# BMS.net
KiCad netlist of a schematic drawn in EAGLE
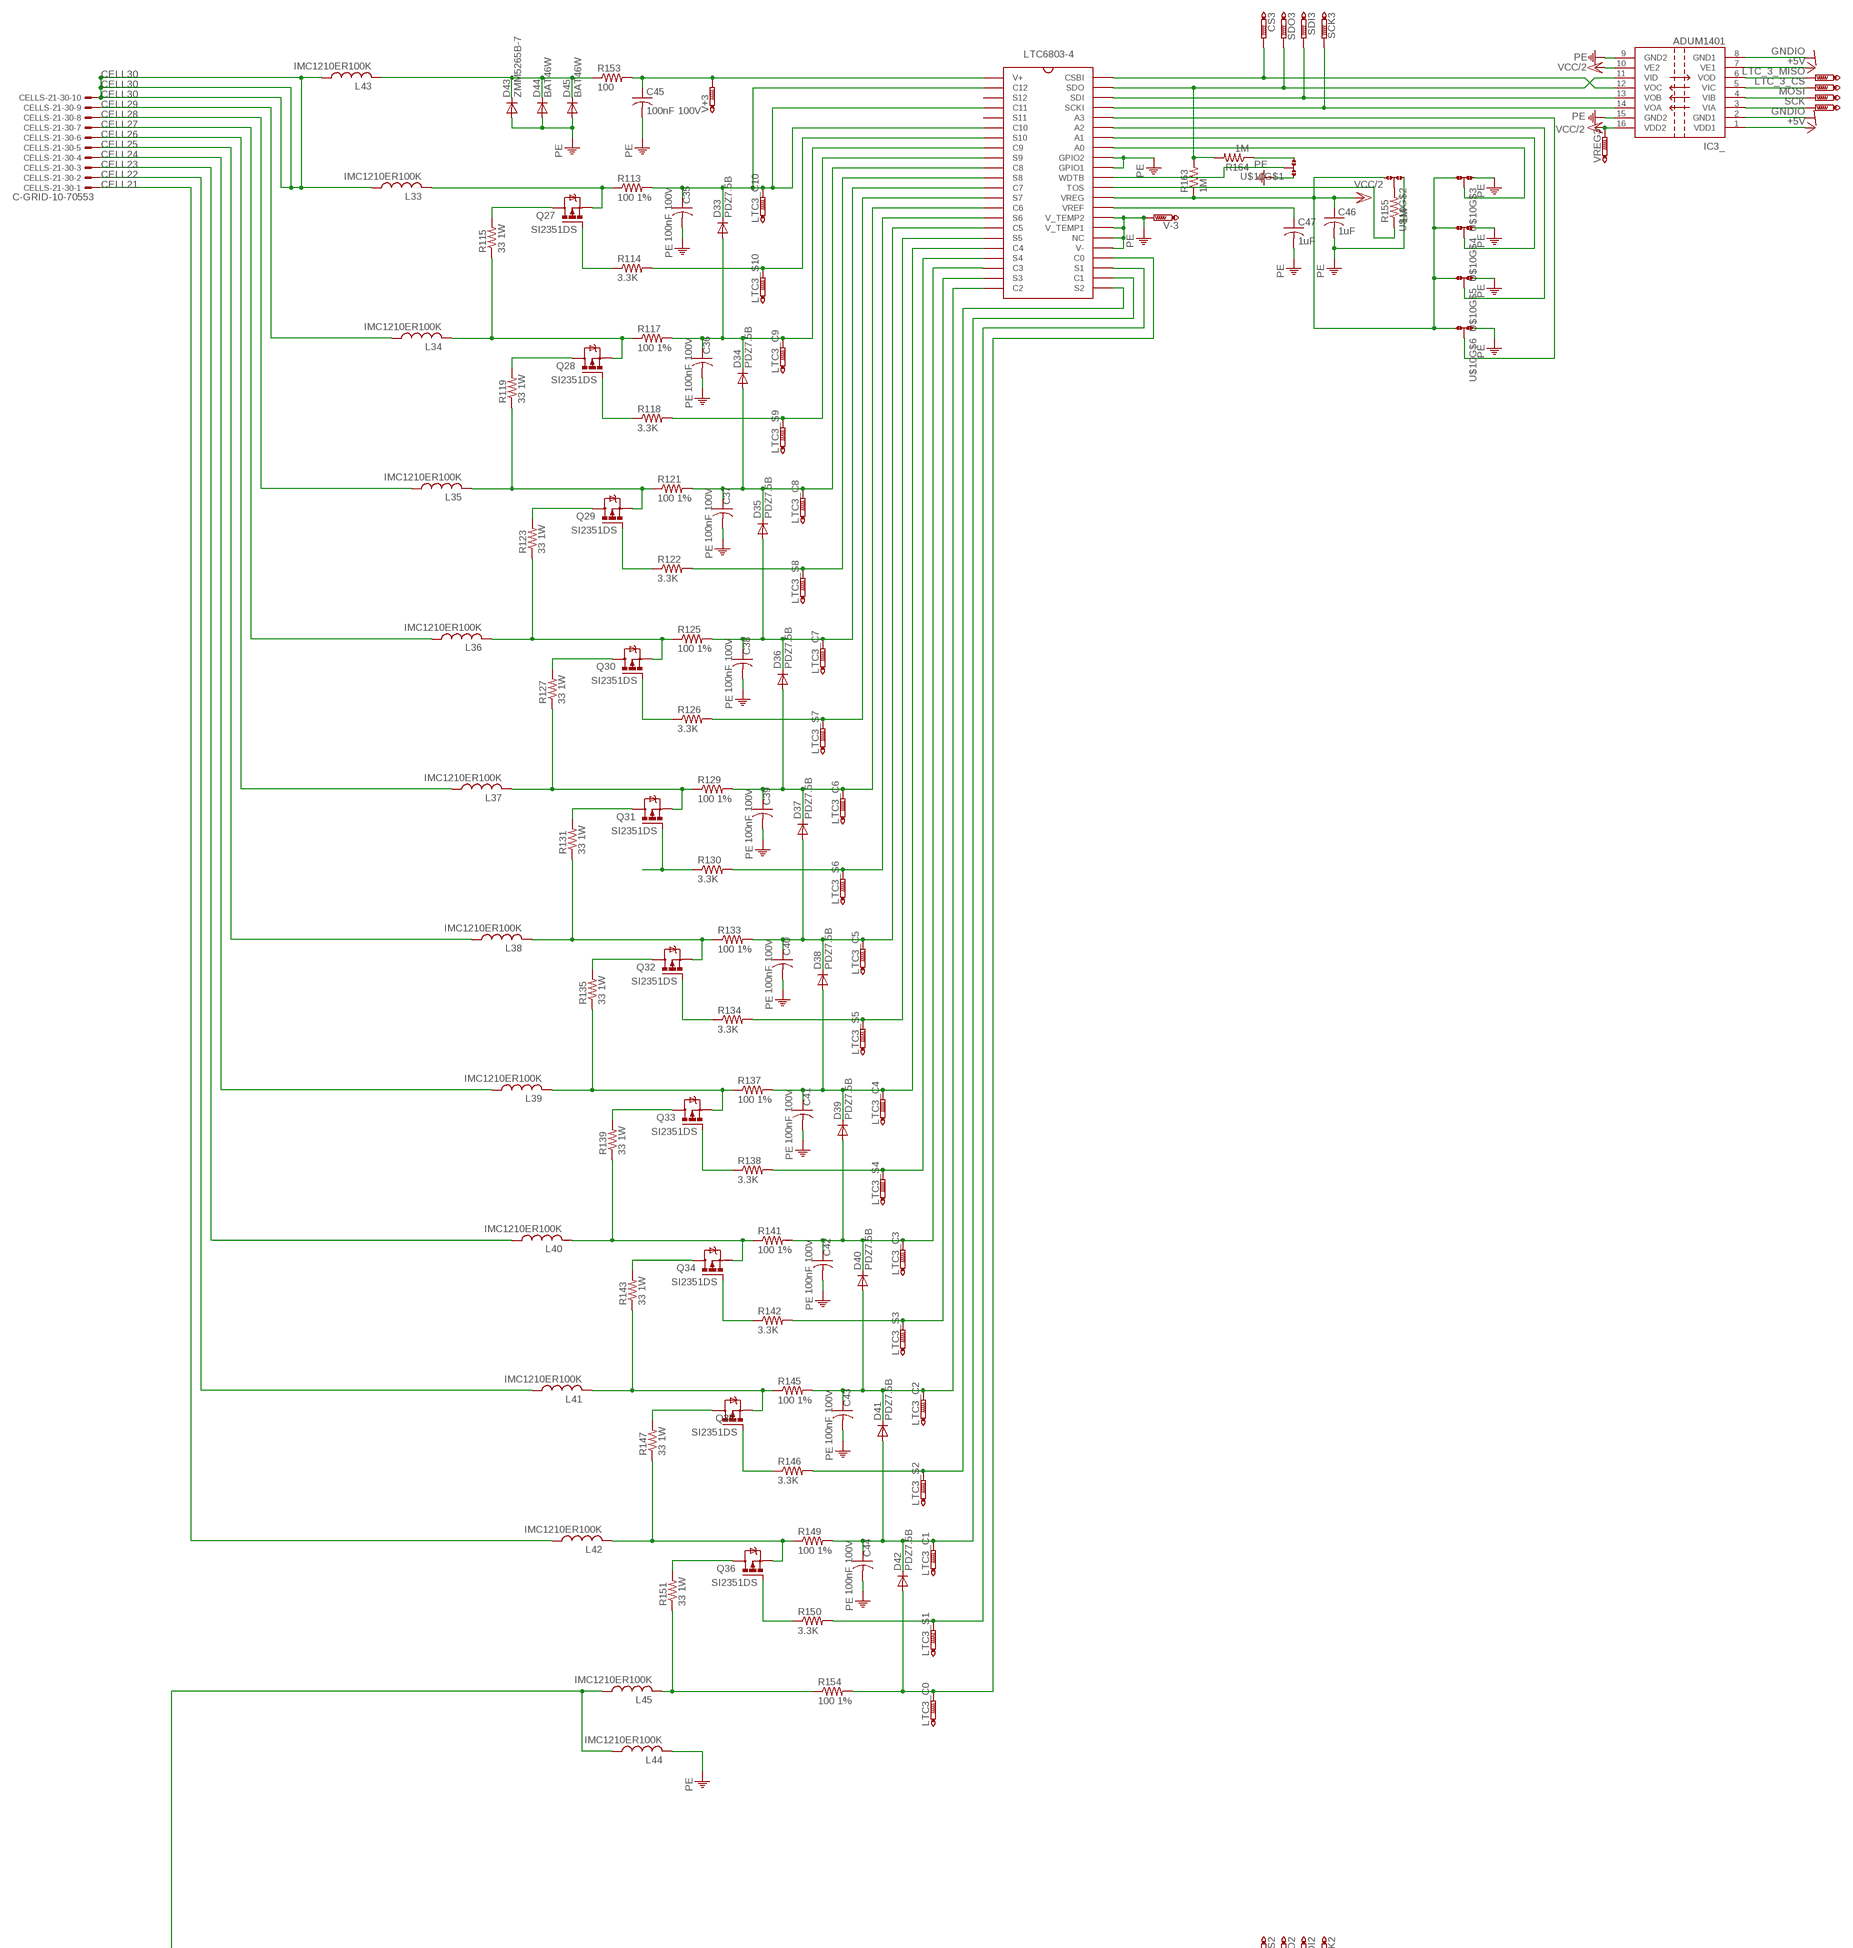
[diagram p0: schematic, sheet 1, part 1 of 3]
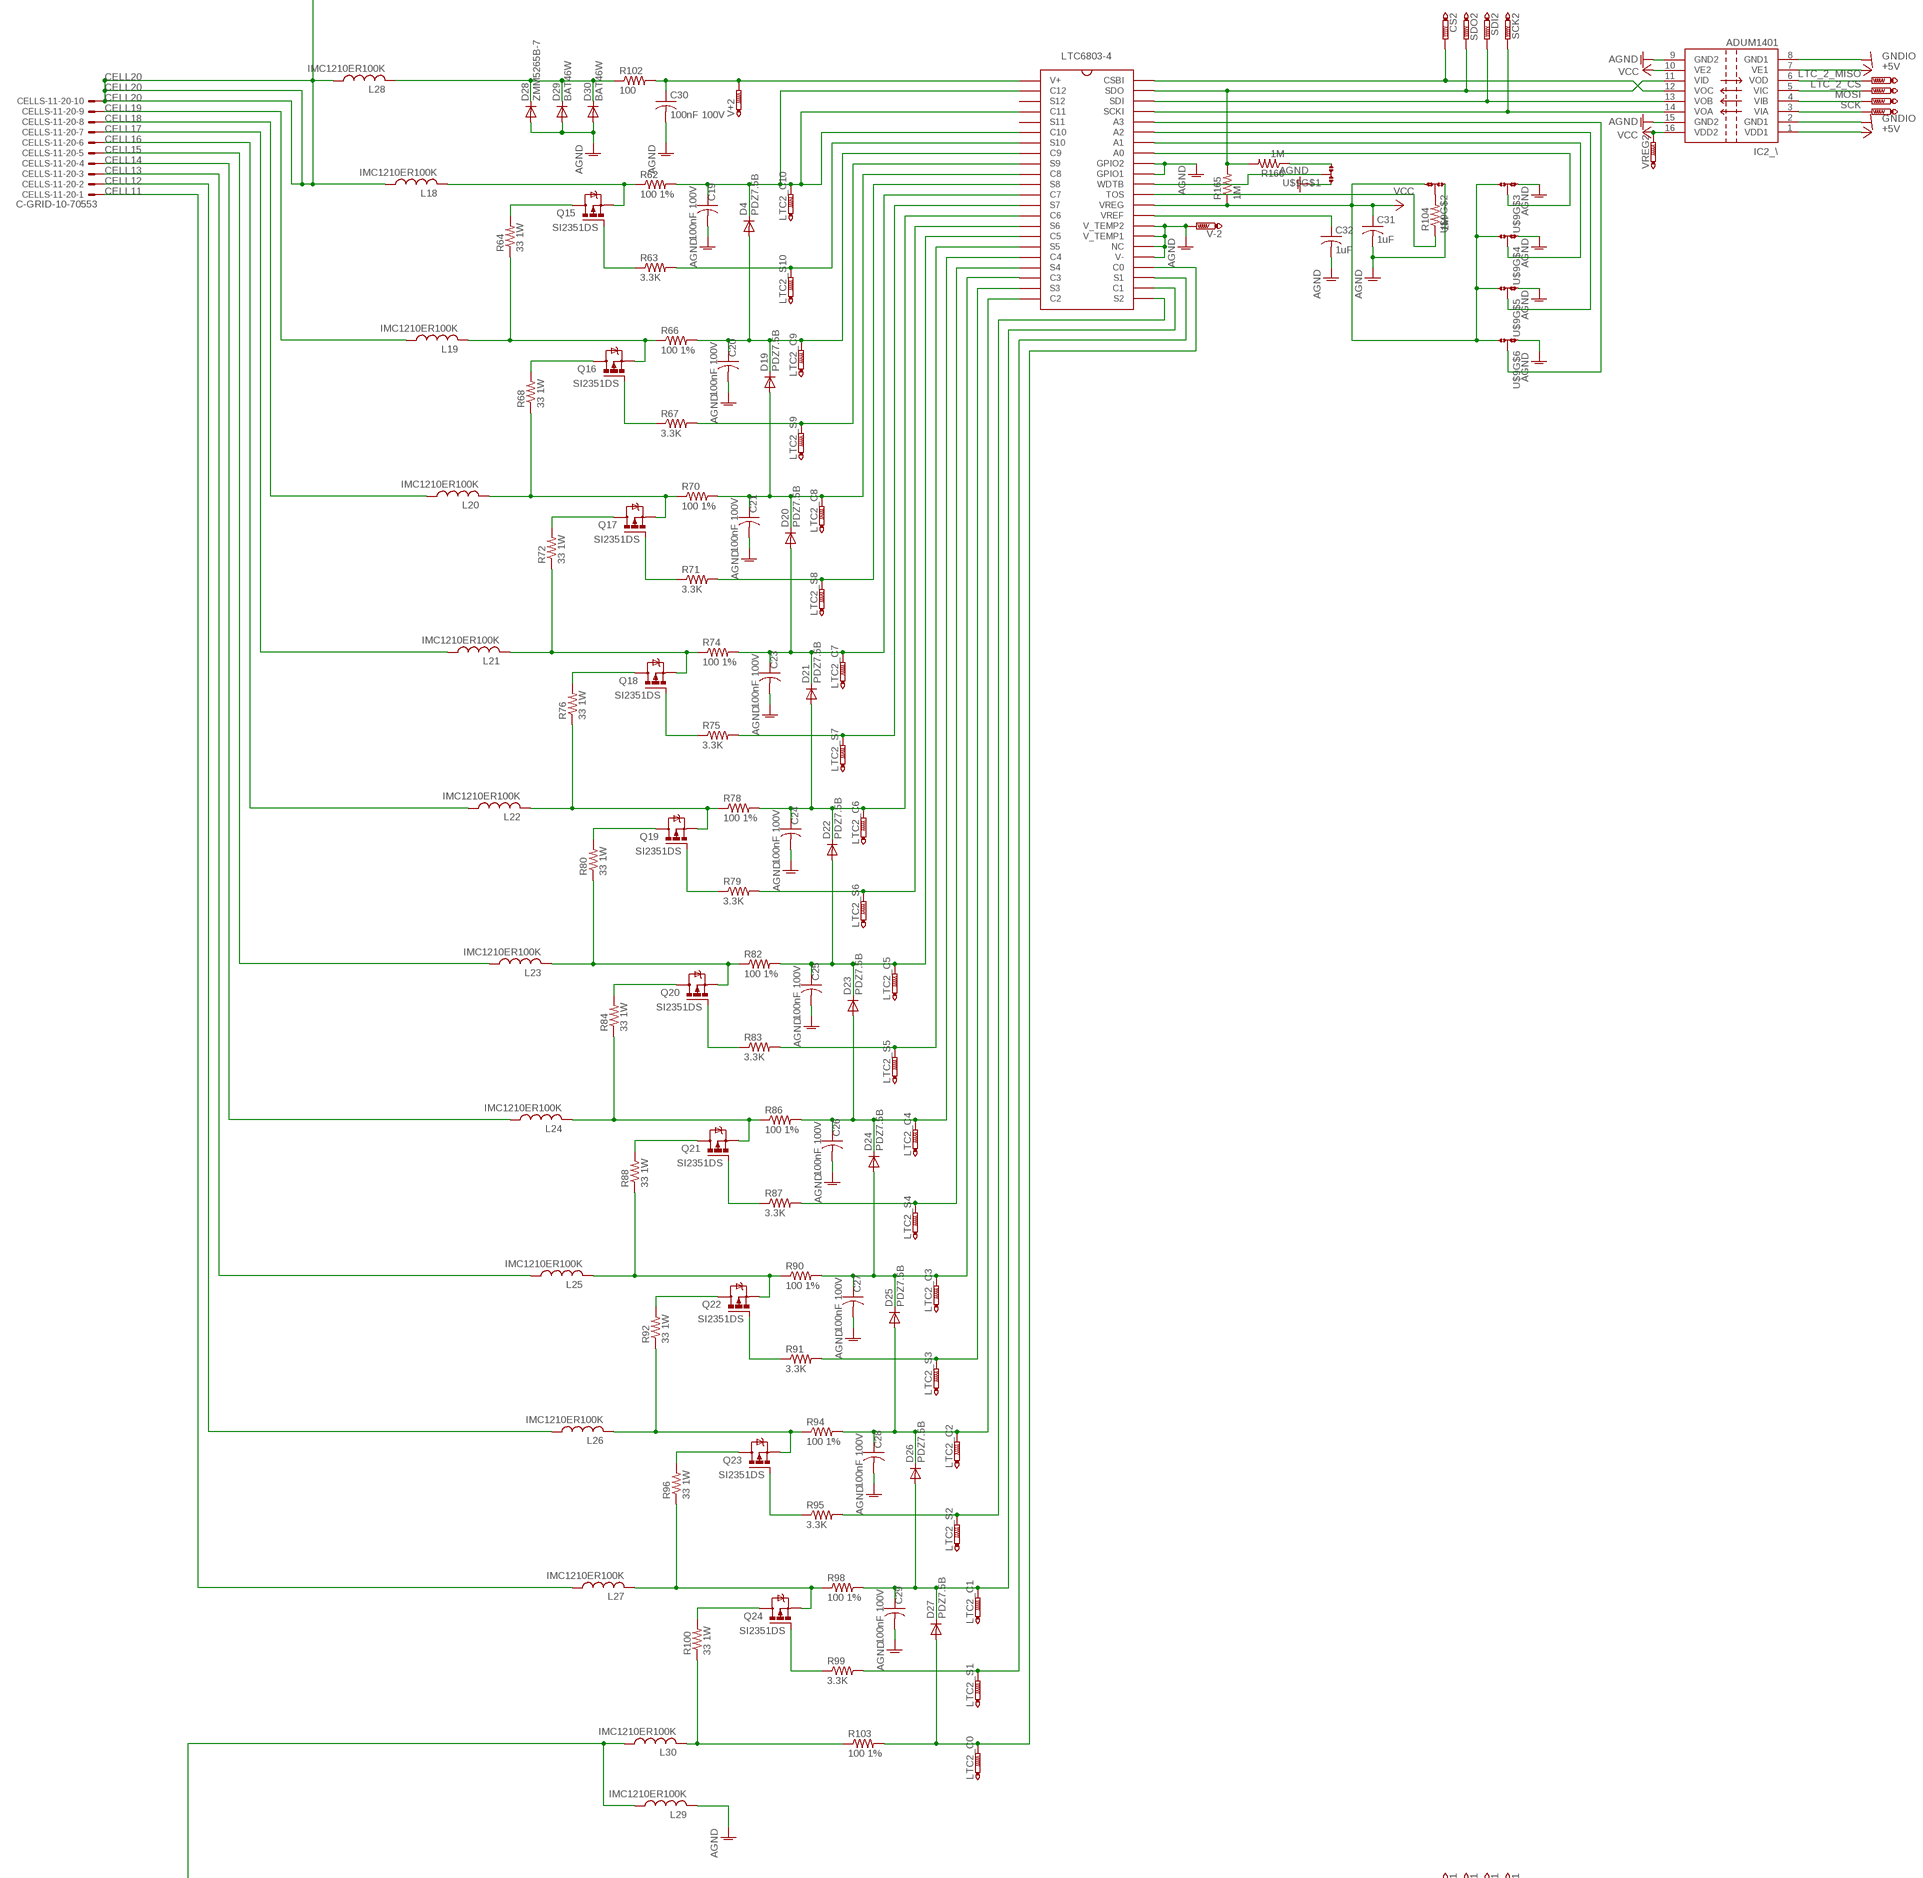
[diagram p1: schematic, sheet 1, part 2 of 3]
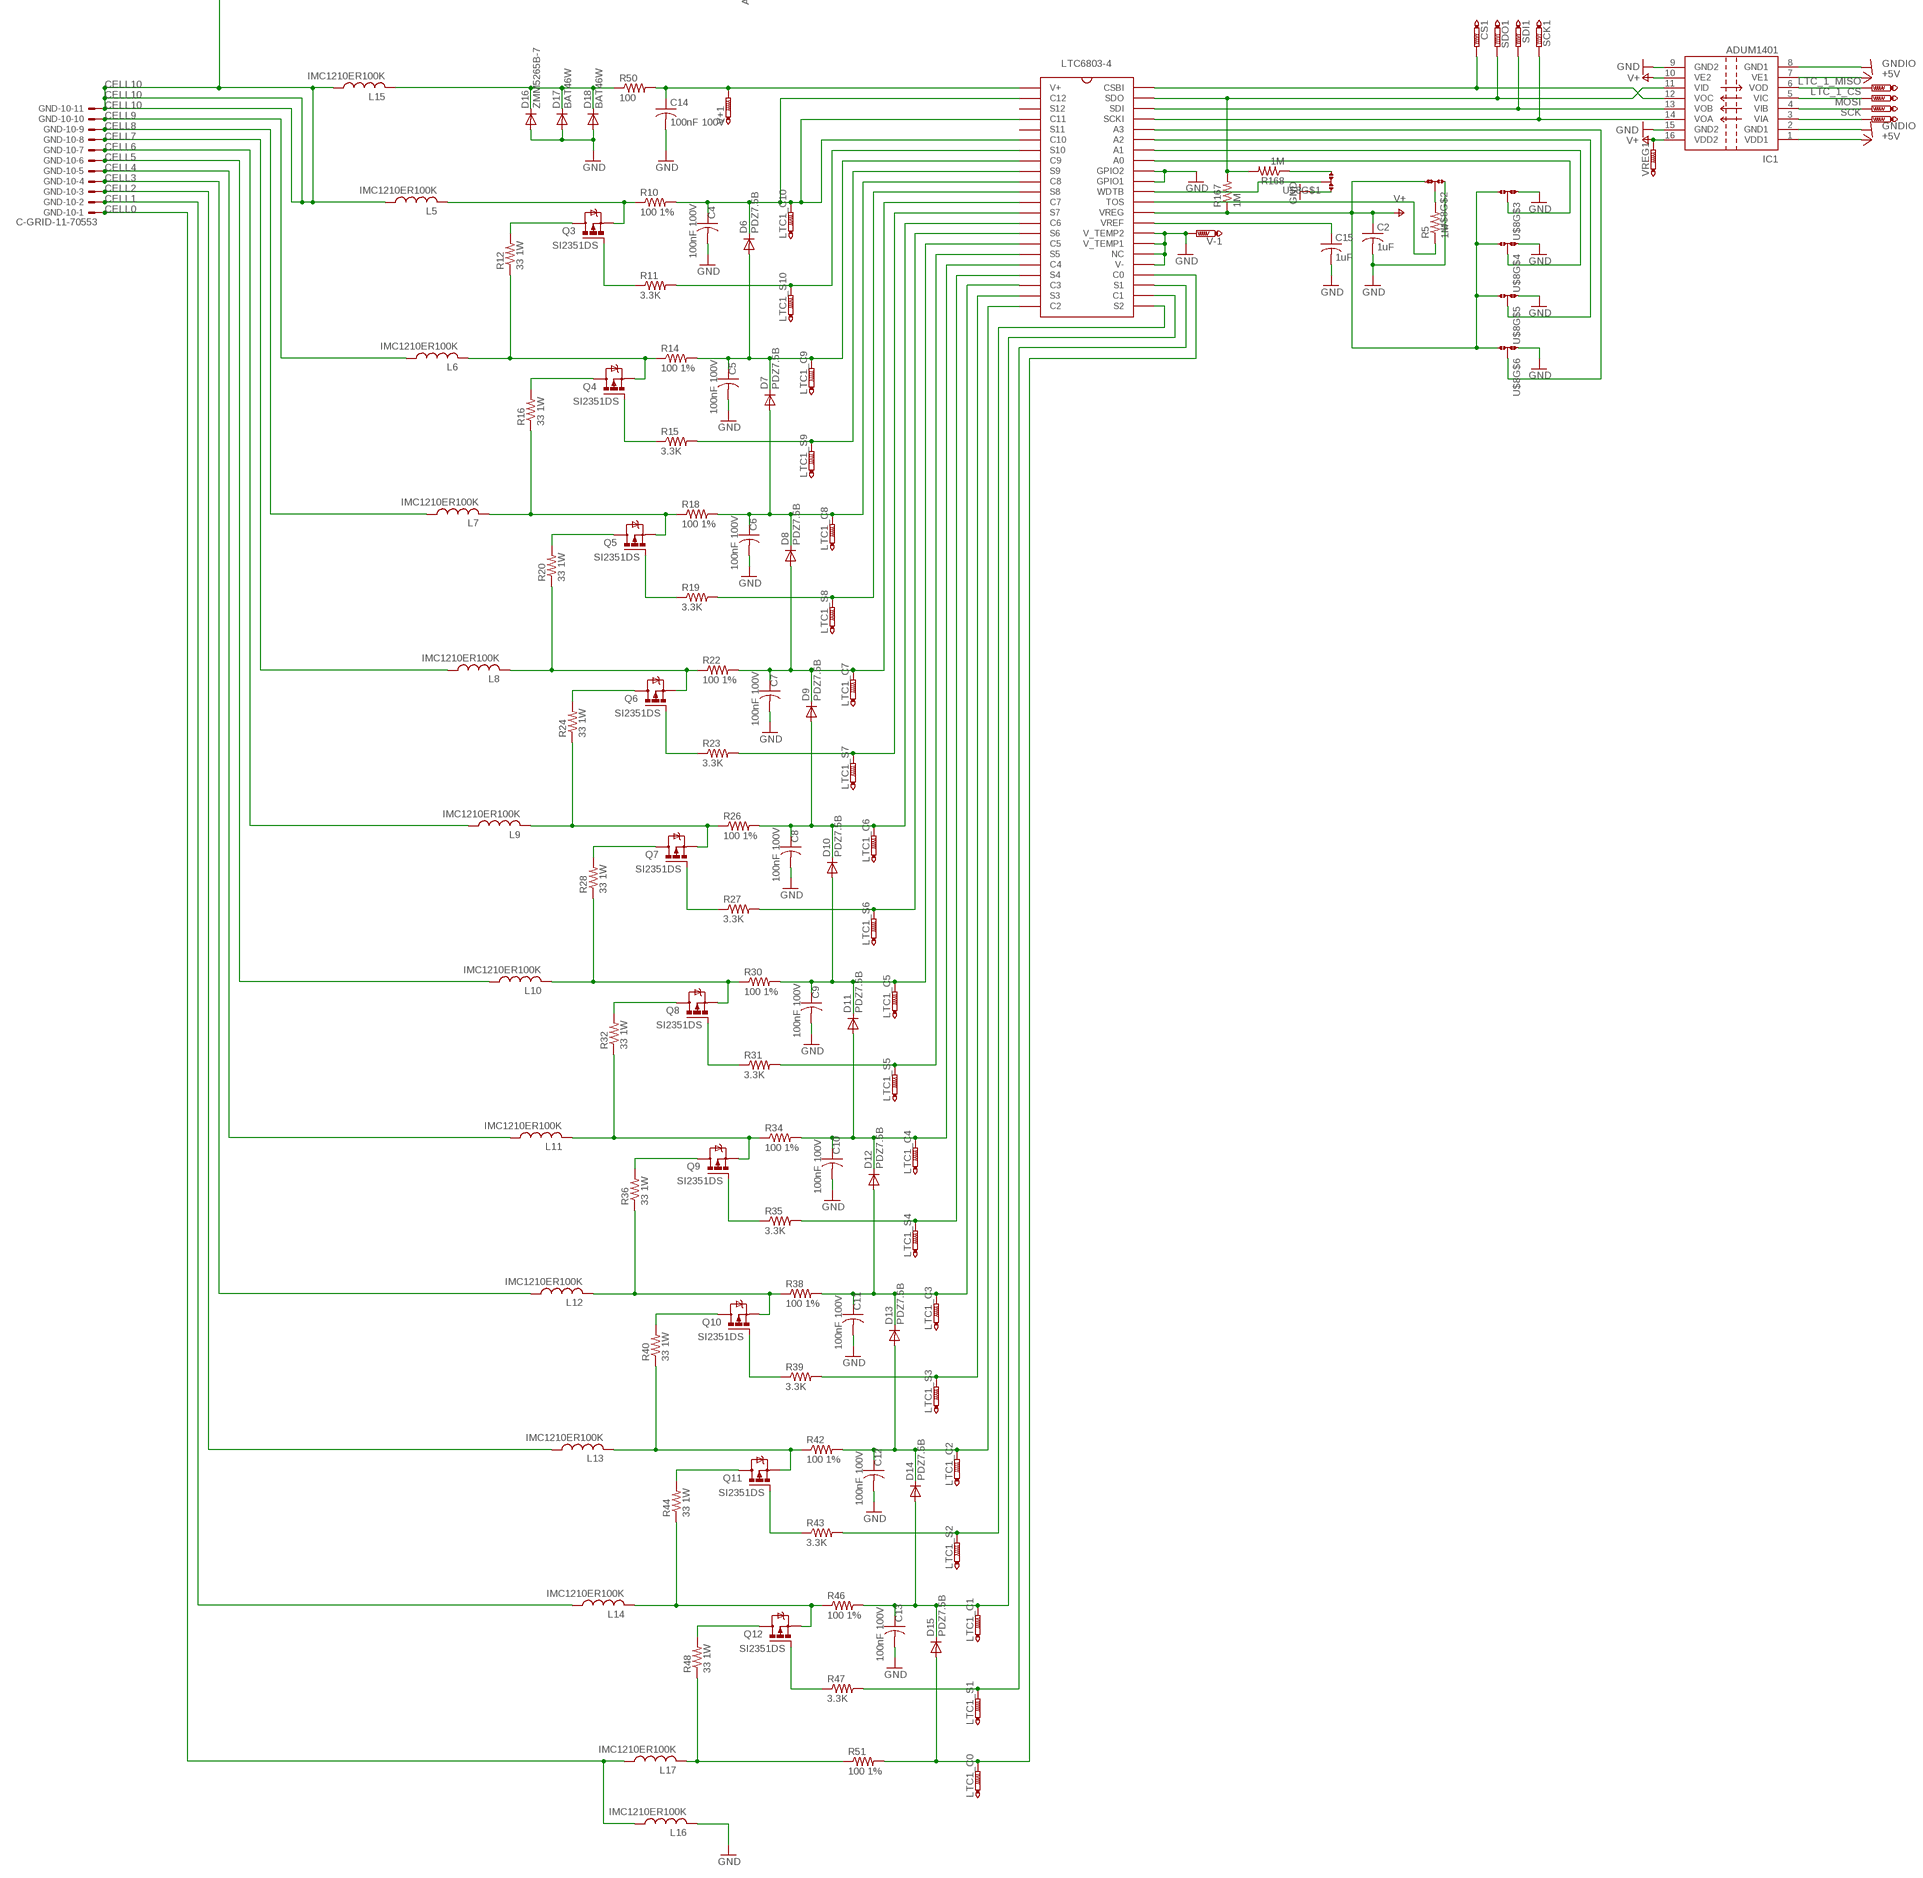
[diagram p2: schematic, sheet 1, part 3 of 3]
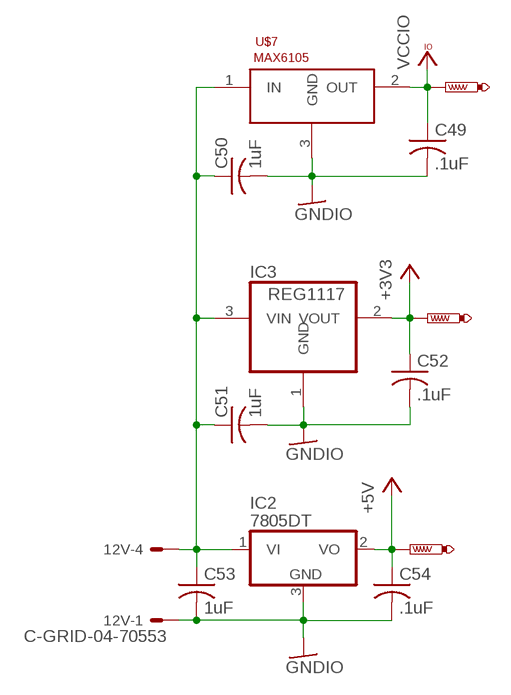
[diagram p3: schematic, sheet 2]
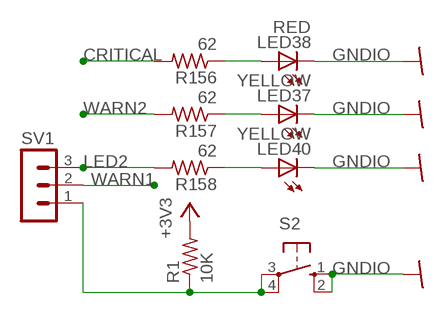
[diagram p4: schematic, sheet 3]
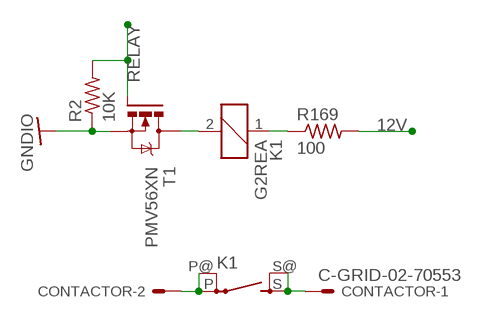
[diagram p5: schematic, sheet 4]
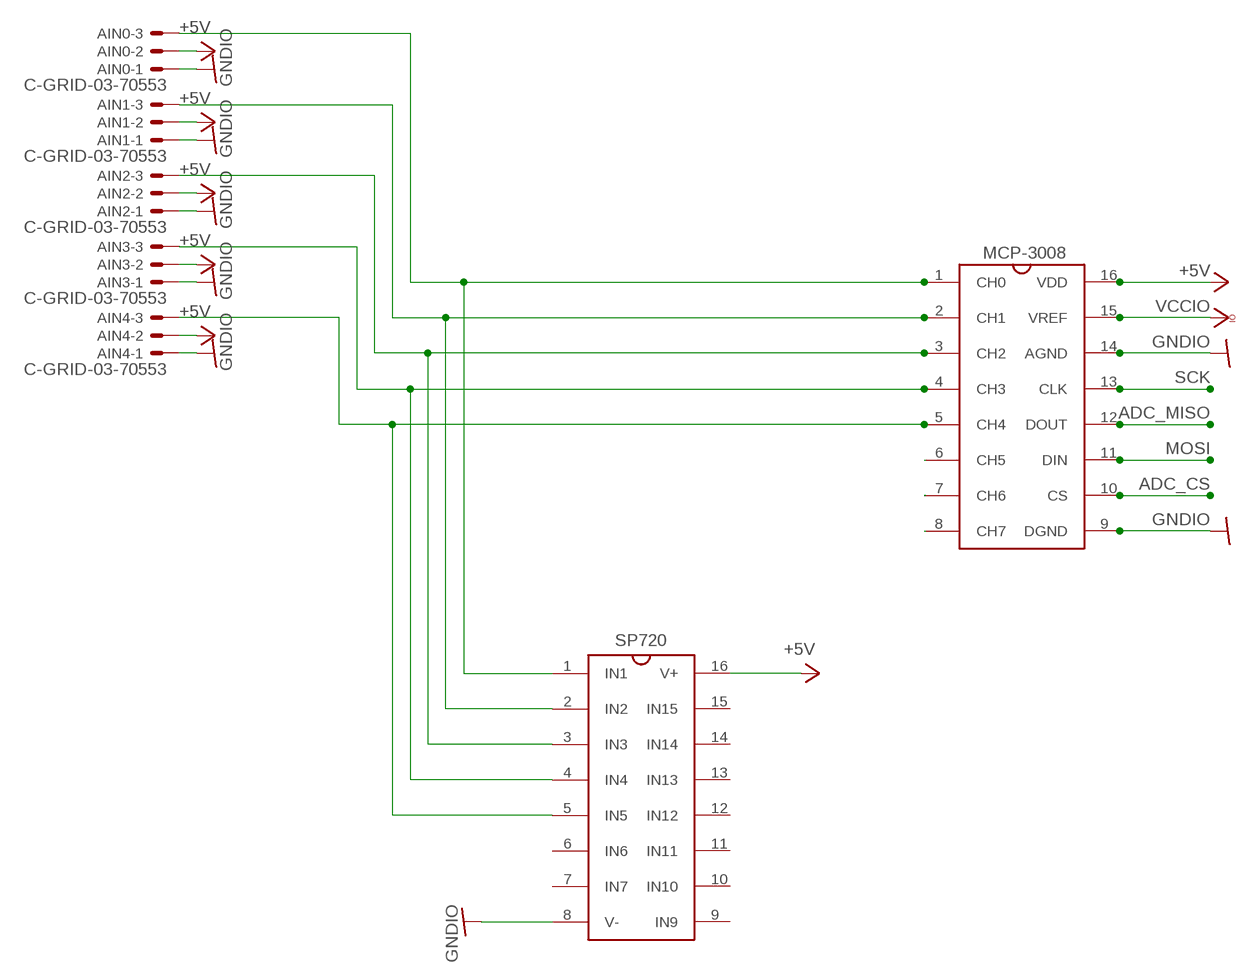
[diagram p6: schematic, sheet 5]
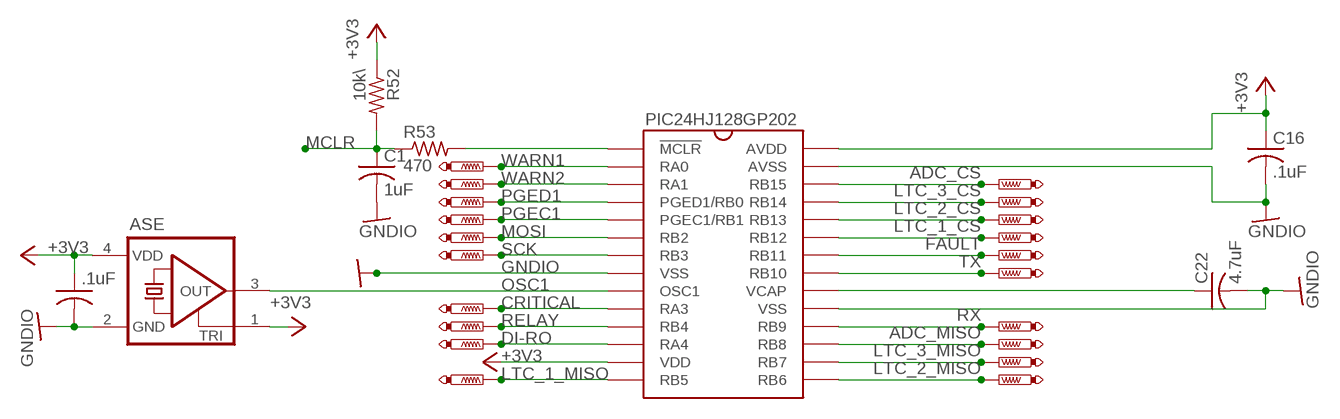
[diagram p7: schematic, sheet 6]
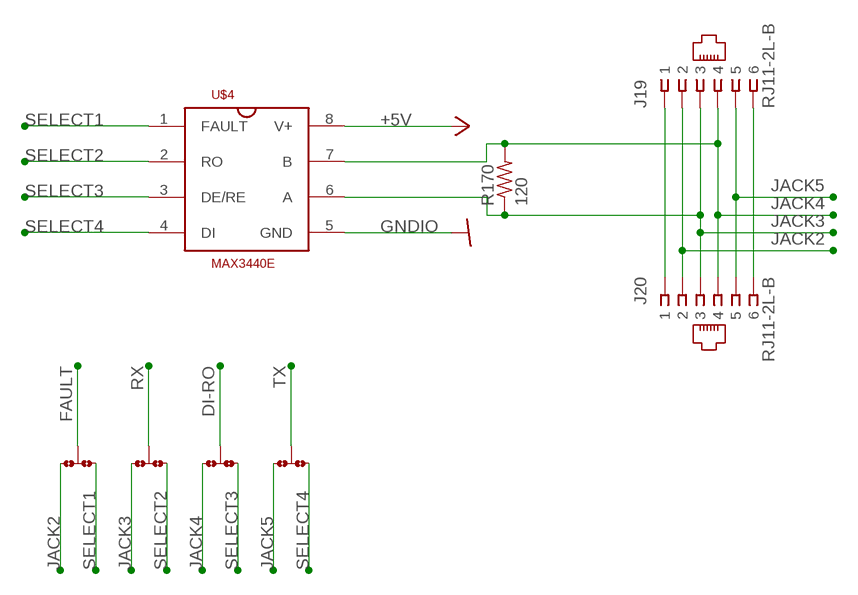
[diagram p8: schematic, sheet 7]
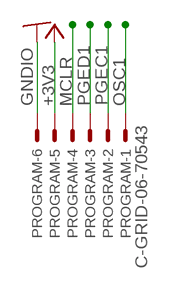
[diagram p9: schematic, sheet 8]

(export (version "E")
  (design (tool "Eeschema 10.0.6"))
  (components
    (comp (ref "CONTACTOR")
      (value "C-GRID-02-70553")
      (footprint "eagle-import:70553-02")
      (libsource (lib "eagle-import") (part "C-GRID-02-70553"))
    )
    (comp (ref "K1")
      (value "G2REA")
      (footprint "eagle-import:G2REA")
      (libsource (lib "eagle-import") (part "G2REA"))
    )
    (comp (ref "R2")
      (value "10K")
      (footprint "eagle-import:R1206")
      (libsource (lib "eagle-import") (part "R-US_R1206"))
    )
    (comp (ref "R169")
      (value "100")
      (footprint "eagle-import:R1206")
      (libsource (lib "eagle-import") (part "R-US_R1206"))
    )
    (comp (ref "T1")
      (value "PMV56XN")
      (footprint "eagle-import:SOT23")
      (fields (field (name "PART_NUM") "PMV56XN,215"))
      (libsource (lib "eagle-import") (part "N-CHANNEL_MOSFETPMV56XN,215"))
    )
    (comp (ref "AIN0")
      (value "C-GRID-03-70553")
      (footprint "eagle-import:70553-03")
      (libsource (lib "eagle-import") (part "C-GRID-03-70553"))
    )
    (comp (ref "AIN1")
      (value "C-GRID-03-70553")
      (footprint "eagle-import:70553-03")
      (libsource (lib "eagle-import") (part "C-GRID-03-70553"))
    )
    (comp (ref "AIN2")
      (value "C-GRID-03-70553")
      (footprint "eagle-import:70553-03")
      (libsource (lib "eagle-import") (part "C-GRID-03-70553"))
    )
    (comp (ref "AIN3")
      (value "C-GRID-03-70553")
      (footprint "eagle-import:70553-03")
      (libsource (lib "eagle-import") (part "C-GRID-03-70553"))
    )
    (comp (ref "AIN4")
      (value "C-GRID-03-70553")
      (footprint "eagle-import:70553-03")
      (libsource (lib "eagle-import") (part "C-GRID-03-70553"))
    )
    (comp (ref "U$1")
      (value "SP720APP")
      (footprint "eagle-import:SO16")
      (libsource (lib "eagle-import") (part "SP720APP"))
    )
    (comp (ref "U$6")
      (value "MCP-3008")
      (footprint "eagle-import:SO16")
      (libsource (lib "eagle-import") (part "MCP-3008"))
    )
    (comp (ref "LED37")
      (value "YELLOW")
      (footprint "eagle-import:CHIPLED_1206")
      (libsource (lib "eagle-import") (part "LEDCHIPLED_1206"))
    )
    (comp (ref "LED38")
      (value "RED")
      (footprint "eagle-import:CHIPLED_1206")
      (libsource (lib "eagle-import") (part "LEDCHIPLED_1206"))
    )
    (comp (ref "LED40")
      (value "YELLOW")
      (footprint "eagle-import:CHIPLED_1206")
      (libsource (lib "eagle-import") (part "LEDCHIPLED_1206"))
    )
    (comp (ref "R1")
      (value "10K")
      (footprint "eagle-import:R1206")
      (libsource (lib "eagle-import") (part "R-US_R1206"))
    )
    (comp (ref "R156")
      (value "62")
      (footprint "eagle-import:R1206")
      (libsource (lib "eagle-import") (part "R-US_R1206"))
    )
    (comp (ref "R157")
      (value "62")
      (footprint "eagle-import:R1206")
      (libsource (lib "eagle-import") (part "R-US_R1206"))
    )
    (comp (ref "R158")
      (value "62")
      (footprint "eagle-import:R1206")
      (libsource (lib "eagle-import") (part "R-US_R1206"))
    )
    (comp (ref "S2")
      (value "10-XX")
      (footprint "eagle-import:B3F-10XX")
      (fields (field (name "MPN") "B3F-1000"))
      (libsource (lib "eagle-import") (part "10-XX"))
    )
    (comp (ref "SV1")
      (value "MA03-1")
      (footprint "eagle-import:MA03-1")
      (libsource (lib "eagle-import") (part "MA03-1"))
    )
    (comp (ref "C1")
      (value "1uF")
      (footprint "eagle-import:C1206")
      (libsource (lib "eagle-import") (part "C-USC1206"))
    )
    (comp (ref "C16")
      (value ".1uF")
      (footprint "eagle-import:C1206")
      (libsource (lib "eagle-import") (part "C-USC1206"))
    )
    (comp (ref "C22")
      (value "4.7uF")
      (footprint "eagle-import:C1206")
      (libsource (lib "eagle-import") (part "C-USC1206"))
    )
    (comp (ref "C48")
      (value ".1uF")
      (footprint "eagle-import:C1206")
      (libsource (lib "eagle-import") (part "C-USC1206"))
    )
    (comp (ref "R52")
      (value "10k\\")
      (footprint "eagle-import:R1206")
      (libsource (lib "eagle-import") (part "R-US_R1206"))
    )
    (comp (ref "R53")
      (value "470")
      (footprint "eagle-import:R1206")
      (libsource (lib "eagle-import") (part "R-US_R1206"))
    )
    (comp (ref "U$2")
      (value "PIC24HJ128GP-202")
      (footprint "eagle-import:SO28W")
      (libsource (lib "eagle-import") (part "PIC24HJ128GP-202"))
    )
    (comp (ref "U$3")
      (value "ASE")
      (footprint "eagle-import:ASE")
      (libsource (lib "eagle-import") (part "ASE"))
    )
    (comp (ref "U$14")
      (value "TESTPAD-20MIL")
      (footprint "eagle-import:20MIL")
      (libsource (lib "eagle-import") (part "TESTPAD-20MIL"))
    )
    (comp (ref "U$15")
      (value "TESTPAD-20MIL")
      (footprint "eagle-import:20MIL")
      (libsource (lib "eagle-import") (part "TESTPAD-20MIL"))
    )
    (comp (ref "U$16")
      (value "TESTPAD-20MIL")
      (footprint "eagle-import:20MIL")
      (libsource (lib "eagle-import") (part "TESTPAD-20MIL"))
    )
    (comp (ref "U$17")
      (value "TESTPAD-20MIL")
      (footprint "eagle-import:20MIL")
      (libsource (lib "eagle-import") (part "TESTPAD-20MIL"))
    )
    (comp (ref "U$18")
      (value "TESTPAD-20MIL")
      (footprint "eagle-import:20MIL")
      (libsource (lib "eagle-import") (part "TESTPAD-20MIL"))
    )
    (comp (ref "U$19")
      (value "TESTPAD-20MIL")
      (footprint "eagle-import:20MIL")
      (libsource (lib "eagle-import") (part "TESTPAD-20MIL"))
    )
    (comp (ref "U$20")
      (value "TESTPAD-20MIL")
      (footprint "eagle-import:20MIL")
      (libsource (lib "eagle-import") (part "TESTPAD-20MIL"))
    )
    (comp (ref "U$21")
      (value "TESTPAD-20MIL")
      (footprint "eagle-import:20MIL")
      (libsource (lib "eagle-import") (part "TESTPAD-20MIL"))
    )
    (comp (ref "U$22")
      (value "TESTPAD-20MIL")
      (footprint "eagle-import:20MIL")
      (libsource (lib "eagle-import") (part "TESTPAD-20MIL"))
    )
    (comp (ref "U$23")
      (value "TESTPAD-20MIL")
      (footprint "eagle-import:20MIL")
      (libsource (lib "eagle-import") (part "TESTPAD-20MIL"))
    )
    (comp (ref "U$24")
      (value "TESTPAD-20MIL")
      (footprint "eagle-import:20MIL")
      (libsource (lib "eagle-import") (part "TESTPAD-20MIL"))
    )
    (comp (ref "U$25")
      (value "TESTPAD-20MIL")
      (footprint "eagle-import:20MIL")
      (libsource (lib "eagle-import") (part "TESTPAD-20MIL"))
    )
    (comp (ref "U$26")
      (value "TESTPAD-20MIL")
      (footprint "eagle-import:20MIL")
      (libsource (lib "eagle-import") (part "TESTPAD-20MIL"))
    )
    (comp (ref "U$27")
      (value "TESTPAD-20MIL")
      (footprint "eagle-import:20MIL")
      (libsource (lib "eagle-import") (part "TESTPAD-20MIL"))
    )
    (comp (ref "U$28")
      (value "TESTPAD-20MIL")
      (footprint "eagle-import:20MIL")
      (libsource (lib "eagle-import") (part "TESTPAD-20MIL"))
    )
    (comp (ref "U$29")
      (value "TESTPAD-20MIL")
      (footprint "eagle-import:20MIL")
      (libsource (lib "eagle-import") (part "TESTPAD-20MIL"))
    )
    (comp (ref "U$30")
      (value "TESTPAD-20MIL")
      (footprint "eagle-import:20MIL")
      (libsource (lib "eagle-import") (part "TESTPAD-20MIL"))
    )
    (comp (ref "U$31")
      (value "TESTPAD-20MIL")
      (footprint "eagle-import:20MIL")
      (libsource (lib "eagle-import") (part "TESTPAD-20MIL"))
    )
    (comp (ref "U$32")
      (value "TESTPAD-20MIL")
      (footprint "eagle-import:20MIL")
      (libsource (lib "eagle-import") (part "TESTPAD-20MIL"))
    )
    (comp (ref "U$33")
      (value "TESTPAD-20MIL")
      (footprint "eagle-import:20MIL")
      (libsource (lib "eagle-import") (part "TESTPAD-20MIL"))
    )
    (comp (ref "J19")
      (value "RJ11-2L-B")
      (footprint "eagle-import:RJ11-NO_SHIELD")
      (fields (field (name "MF") "TYCO ELECTRONICS"))
      (libsource (lib "eagle-import") (part "RJ11-2L-B"))
    )
    (comp (ref "J20")
      (value "RJ11-2L-B")
      (footprint "eagle-import:RJ11-NO_SHIELD")
      (fields (field (name "MF") "TYCO ELECTRONICS"))
      (libsource (lib "eagle-import") (part "RJ11-2L-B"))
    )
    (comp (ref "R170")
      (value "120")
      (footprint "eagle-import:R1206")
      (libsource (lib "eagle-import") (part "R-US_R1206"))
    )
    (comp (ref "U$4")
      (value "MAX3440E")
      (footprint "eagle-import:SO-08")
      (libsource (lib "eagle-import") (part "MAX3440E"))
    )
    (comp (ref "U$5")
      (value "3ROW_4POS")
      (footprint "eagle-import:3ROW_4POS")
      (libsource (lib "eagle-import") (part "3ROW_4POS"))
    )
    (comp (ref "12V")
      (value "C-GRID-04-70553")
      (footprint "eagle-import:70553-04")
      (libsource (lib "eagle-import") (part "C-GRID-04-70553"))
    )
    (comp (ref "C49")
      (value ".1uF")
      (footprint "eagle-import:C1206")
      (libsource (lib "eagle-import") (part "C-USC1206"))
    )
    (comp (ref "C50")
      (value "1uF")
      (footprint "eagle-import:C1206")
      (libsource (lib "eagle-import") (part "C-USC1206"))
    )
    (comp (ref "C51")
      (value "1uF")
      (footprint "eagle-import:C1206")
      (libsource (lib "eagle-import") (part "C-USC1206"))
    )
    (comp (ref "C52")
      (value ".1uF")
      (footprint "eagle-import:C1206")
      (libsource (lib "eagle-import") (part "C-USC1206"))
    )
    (comp (ref "C53")
      (value "1uF")
      (footprint "eagle-import:C1206")
      (libsource (lib "eagle-import") (part "C-USC1206"))
    )
    (comp (ref "C54")
      (value ".1uF")
      (footprint "eagle-import:C1206")
      (libsource (lib "eagle-import") (part "C-USC1206"))
    )
    (comp (ref "IC2")
      (value "7805DT")
      (footprint "eagle-import:TO252")
      (libsource (lib "eagle-import") (part "78DT05"))
    )
    (comp (ref "IC3")
      (value "REG1117")
      (footprint "eagle-import:SOT223")
      (libsource (lib "eagle-import") (part "REG1117"))
    )
    (comp (ref "U$7")
      (value "MAX6105")
      (footprint "eagle-import:SOT23")
      (libsource (lib "eagle-import") (part "MAX6103"))
    )
    (comp (ref "U$11")
      (value "TESTPAD-20MIL")
      (footprint "eagle-import:20MIL")
      (libsource (lib "eagle-import") (part "TESTPAD-20MIL"))
    )
    (comp (ref "U$12")
      (value "TESTPAD-20MIL")
      (footprint "eagle-import:20MIL")
      (libsource (lib "eagle-import") (part "TESTPAD-20MIL"))
    )
    (comp (ref "U$13")
      (value "TESTPAD-20MIL")
      (footprint "eagle-import:20MIL")
      (libsource (lib "eagle-import") (part "TESTPAD-20MIL"))
    )
    (comp (ref "C2")
      (value "1uF")
      (footprint "eagle-import:C1206")
      (libsource (lib "eagle-import") (part "C-USC1206"))
    )
    (comp (ref "C4")
      (value "100nF 100V")
      (footprint "eagle-import:C1206")
      (libsource (lib "eagle-import") (part "C-USC1206"))
    )
    (comp (ref "C5")
      (value "100nF 100V")
      (footprint "eagle-import:C1206")
      (libsource (lib "eagle-import") (part "C-USC1206"))
    )
    (comp (ref "C6")
      (value "100nF 100V")
      (footprint "eagle-import:C1206")
      (libsource (lib "eagle-import") (part "C-USC1206"))
    )
    (comp (ref "C7")
      (value "100nF 100V")
      (footprint "eagle-import:C1206")
      (libsource (lib "eagle-import") (part "C-USC1206"))
    )
    (comp (ref "C8")
      (value "100nF 100V")
      (footprint "eagle-import:C1206")
      (libsource (lib "eagle-import") (part "C-USC1206"))
    )
    (comp (ref "C9")
      (value "100nF 100V")
      (footprint "eagle-import:C1206")
      (libsource (lib "eagle-import") (part "C-USC1206"))
    )
    (comp (ref "C10")
      (value "100nF 100V")
      (footprint "eagle-import:C1206")
      (libsource (lib "eagle-import") (part "C-USC1206"))
    )
    (comp (ref "C11")
      (value "100nF 100V")
      (footprint "eagle-import:C1206")
      (libsource (lib "eagle-import") (part "C-USC1206"))
    )
    (comp (ref "C12")
      (value "100nF 100V")
      (footprint "eagle-import:C1206")
      (libsource (lib "eagle-import") (part "C-USC1206"))
    )
    (comp (ref "C13")
      (value "100nF 100V")
      (footprint "eagle-import:C1206")
      (libsource (lib "eagle-import") (part "C-USC1206"))
    )
    (comp (ref "C14")
      (value "100nF 100V")
      (footprint "eagle-import:C1206")
      (libsource (lib "eagle-import") (part "C-USC1206"))
    )
    (comp (ref "C15")
      (value "1uF")
      (footprint "eagle-import:C1206")
      (libsource (lib "eagle-import") (part "C-USC1206"))
    )
    (comp (ref "C19")
      (value "100nF 100V")
      (footprint "eagle-import:C1206")
      (libsource (lib "eagle-import") (part "C-USC1206"))
    )
    (comp (ref "C20")
      (value "100nF 100V")
      (footprint "eagle-import:C1206")
      (libsource (lib "eagle-import") (part "C-USC1206"))
    )
    (comp (ref "C21")
      (value "100nF 100V")
      (footprint "eagle-import:C1206")
      (libsource (lib "eagle-import") (part "C-USC1206"))
    )
    (comp (ref "C23")
      (value "100nF 100V")
      (footprint "eagle-import:C1206")
      (libsource (lib "eagle-import") (part "C-USC1206"))
    )
    (comp (ref "C24")
      (value "100nF 100V")
      (footprint "eagle-import:C1206")
      (libsource (lib "eagle-import") (part "C-USC1206"))
    )
    (comp (ref "C25")
      (value "100nF 100V")
      (footprint "eagle-import:C1206")
      (libsource (lib "eagle-import") (part "C-USC1206"))
    )
    (comp (ref "C26")
      (value "100nF 100V")
      (footprint "eagle-import:C1206")
      (libsource (lib "eagle-import") (part "C-USC1206"))
    )
    (comp (ref "C27")
      (value "100nF 100V")
      (footprint "eagle-import:C1206")
      (libsource (lib "eagle-import") (part "C-USC1206"))
    )
    (comp (ref "C28")
      (value "100nF 100V")
      (footprint "eagle-import:C1206")
      (libsource (lib "eagle-import") (part "C-USC1206"))
    )
    (comp (ref "C29")
      (value "100nF 100V")
      (footprint "eagle-import:C1206")
      (libsource (lib "eagle-import") (part "C-USC1206"))
    )
    (comp (ref "C30")
      (value "100nF 100V")
      (footprint "eagle-import:C1206")
      (libsource (lib "eagle-import") (part "C-USC1206"))
    )
    (comp (ref "C31")
      (value "1uF")
      (footprint "eagle-import:C1206")
      (libsource (lib "eagle-import") (part "C-USC1206"))
    )
    (comp (ref "C32")
      (value "1uF")
      (footprint "eagle-import:C1206")
      (libsource (lib "eagle-import") (part "C-USC1206"))
    )
    (comp (ref "C35")
      (value "100nF 100V")
      (footprint "eagle-import:C1206")
      (libsource (lib "eagle-import") (part "C-USC1206"))
    )
    (comp (ref "C36")
      (value "100nF 100V")
      (footprint "eagle-import:C1206")
      (libsource (lib "eagle-import") (part "C-USC1206"))
    )
    (comp (ref "C37")
      (value "100nF 100V")
      (footprint "eagle-import:C1206")
      (libsource (lib "eagle-import") (part "C-USC1206"))
    )
    (comp (ref "C38")
      (value "100nF 100V")
      (footprint "eagle-import:C1206")
      (libsource (lib "eagle-import") (part "C-USC1206"))
    )
    (comp (ref "C39")
      (value "100nF 100V")
      (footprint "eagle-import:C1206")
      (libsource (lib "eagle-import") (part "C-USC1206"))
    )
    (comp (ref "C40")
      (value "100nF 100V")
      (footprint "eagle-import:C1206")
      (libsource (lib "eagle-import") (part "C-USC1206"))
    )
    (comp (ref "C41")
      (value "100nF 100V")
      (footprint "eagle-import:C1206")
      (libsource (lib "eagle-import") (part "C-USC1206"))
    )
    (comp (ref "C42")
      (value "100nF 100V")
      (footprint "eagle-import:C1206")
      (libsource (lib "eagle-import") (part "C-USC1206"))
    )
    (comp (ref "C43")
      (value "100nF 100V")
      (footprint "eagle-import:C1206")
      (libsource (lib "eagle-import") (part "C-USC1206"))
    )
    (comp (ref "C44")
      (value "100nF 100V")
      (footprint "eagle-import:C1206")
      (libsource (lib "eagle-import") (part "C-USC1206"))
    )
    (comp (ref "C45")
      (value "100nF 100V")
      (footprint "eagle-import:C1206")
      (libsource (lib "eagle-import") (part "C-USC1206"))
    )
    (comp (ref "C46")
      (value "1uF")
      (footprint "eagle-import:C1206")
      (libsource (lib "eagle-import") (part "C-USC1206"))
    )
    (comp (ref "C47")
      (value "1uF")
      (footprint "eagle-import:C1206")
      (libsource (lib "eagle-import") (part "C-USC1206"))
    )
    (comp (ref "CELLS-11-20")
      (value "C-GRID-10-70553")
      (footprint "eagle-import:70553-10")
      (libsource (lib "eagle-import") (part "C-GRID-10-70553"))
    )
    (comp (ref "CELLS-21-30")
      (value "C-GRID-10-70553")
      (footprint "eagle-import:70553-10")
      (libsource (lib "eagle-import") (part "C-GRID-10-70553"))
    )
    (comp (ref "CS1")
      (value "PTR1PAD1-13")
      (footprint "eagle-import:P1-13")
      (libsource (lib "eagle-import") (part "PTR1PAD1-13"))
    )
    (comp (ref "CS1_O")
      (value "PTR1PAD1-13")
      (footprint "eagle-import:P1-13")
      (libsource (lib "eagle-import") (part "PTR1PAD1-13"))
    )
    (comp (ref "CS2")
      (value "PTR1PAD1-13")
      (footprint "eagle-import:P1-13")
      (libsource (lib "eagle-import") (part "PTR1PAD1-13"))
    )
    (comp (ref "CS2_O")
      (value "PTR1PAD1-13")
      (footprint "eagle-import:P1-13")
      (libsource (lib "eagle-import") (part "PTR1PAD1-13"))
    )
    (comp (ref "CS3")
      (value "PTR1PAD1-13")
      (footprint "eagle-import:P1-13")
      (libsource (lib "eagle-import") (part "PTR1PAD1-13"))
    )
    (comp (ref "CS3_O")
      (value "PTR1PAD1-13")
      (footprint "eagle-import:P1-13")
      (libsource (lib "eagle-import") (part "PTR1PAD1-13"))
    )
    (comp (ref "D4")
      (value "PDZ7.5B")
      (footprint "eagle-import:SOD323-W")
      (libsource (lib "eagle-import") (part "DIODE-SOD323-W"))
    )
    (comp (ref "D6")
      (value "PDZ7.5B")
      (footprint "eagle-import:SOD323-W")
      (libsource (lib "eagle-import") (part "DIODE-SOD323-W"))
    )
    (comp (ref "D7")
      (value "PDZ7.5B")
      (footprint "eagle-import:SOD323-W")
      (libsource (lib "eagle-import") (part "DIODE-SOD323-W"))
    )
    (comp (ref "D8")
      (value "PDZ7.5B")
      (footprint "eagle-import:SOD323-W")
      (libsource (lib "eagle-import") (part "DIODE-SOD323-W"))
    )
    (comp (ref "D9")
      (value "PDZ7.5B")
      (footprint "eagle-import:SOD323-W")
      (libsource (lib "eagle-import") (part "DIODE-SOD323-W"))
    )
    (comp (ref "D10")
      (value "PDZ7.5B")
      (footprint "eagle-import:SOD323-W")
      (libsource (lib "eagle-import") (part "DIODE-SOD323-W"))
    )
    (comp (ref "D11")
      (value "PDZ7.5B")
      (footprint "eagle-import:SOD323-W")
      (libsource (lib "eagle-import") (part "DIODE-SOD323-W"))
    )
    (comp (ref "D12")
      (value "PDZ7.5B")
      (footprint "eagle-import:SOD323-W")
      (libsource (lib "eagle-import") (part "DIODE-SOD323-W"))
    )
    (comp (ref "D13")
      (value "PDZ7.5B")
      (footprint "eagle-import:SOD323-W")
      (libsource (lib "eagle-import") (part "DIODE-SOD323-W"))
    )
    (comp (ref "D14")
      (value "PDZ7.5B")
      (footprint "eagle-import:SOD323-W")
      (libsource (lib "eagle-import") (part "DIODE-SOD323-W"))
    )
    (comp (ref "D15")
      (value "PDZ7.5B")
      (footprint "eagle-import:SOD323-W")
      (libsource (lib "eagle-import") (part "DIODE-SOD323-W"))
    )
    (comp (ref "D16")
      (value "ZMM5265B-7")
      (footprint "eagle-import:MINIMELF")
      (libsource (lib "eagle-import") (part "DIODE-MINIMELF"))
    )
    (comp (ref "D17")
      (value "BAT46W")
      (footprint "eagle-import:SOD123")
      (libsource (lib "eagle-import") (part "DIODE-SOD123"))
    )
    (comp (ref "D18")
      (value "BAT46W")
      (footprint "eagle-import:SOD123")
      (libsource (lib "eagle-import") (part "DIODE-SOD123"))
    )
    (comp (ref "D19")
      (value "PDZ7.5B")
      (footprint "eagle-import:SOD323-W")
      (libsource (lib "eagle-import") (part "DIODE-SOD323-W"))
    )
    (comp (ref "D20")
      (value "PDZ7.5B")
      (footprint "eagle-import:SOD323-W")
      (libsource (lib "eagle-import") (part "DIODE-SOD323-W"))
    )
    (comp (ref "D21")
      (value "PDZ7.5B")
      (footprint "eagle-import:SOD323-W")
      (libsource (lib "eagle-import") (part "DIODE-SOD323-W"))
    )
    (comp (ref "D22")
      (value "PDZ7.5B")
      (footprint "eagle-import:SOD323-W")
      (libsource (lib "eagle-import") (part "DIODE-SOD323-W"))
    )
    (comp (ref "D23")
      (value "PDZ7.5B")
      (footprint "eagle-import:SOD323-W")
      (libsource (lib "eagle-import") (part "DIODE-SOD323-W"))
    )
    (comp (ref "D24")
      (value "PDZ7.5B")
      (footprint "eagle-import:SOD323-W")
      (libsource (lib "eagle-import") (part "DIODE-SOD323-W"))
    )
    (comp (ref "D25")
      (value "PDZ7.5B")
      (footprint "eagle-import:SOD323-W")
      (libsource (lib "eagle-import") (part "DIODE-SOD323-W"))
    )
    (comp (ref "D26")
      (value "PDZ7.5B")
      (footprint "eagle-import:SOD323-W")
      (libsource (lib "eagle-import") (part "DIODE-SOD323-W"))
    )
    (comp (ref "D27")
      (value "PDZ7.5B")
      (footprint "eagle-import:SOD323-W")
      (libsource (lib "eagle-import") (part "DIODE-SOD323-W"))
    )
    (comp (ref "D28")
      (value "ZMM5265B-7")
      (footprint "eagle-import:MINIMELF")
      (libsource (lib "eagle-import") (part "DIODE-MINIMELF"))
    )
    (comp (ref "D29")
      (value "BAT46W")
      (footprint "eagle-import:SOD123")
      (libsource (lib "eagle-import") (part "DIODE-SOD123"))
    )
    (comp (ref "D30")
      (value "BAT46W")
      (footprint "eagle-import:SOD123")
      (libsource (lib "eagle-import") (part "DIODE-SOD123"))
    )
    (comp (ref "D33")
      (value "PDZ7.5B")
      (footprint "eagle-import:SOD323-W")
      (libsource (lib "eagle-import") (part "DIODE-SOD323-W"))
    )
    (comp (ref "D34")
      (value "PDZ7.5B")
      (footprint "eagle-import:SOD323-W")
      (libsource (lib "eagle-import") (part "DIODE-SOD323-W"))
    )
    (comp (ref "D35")
      (value "PDZ7.5B")
      (footprint "eagle-import:SOD323-W")
      (libsource (lib "eagle-import") (part "DIODE-SOD323-W"))
    )
    (comp (ref "D36")
      (value "PDZ7.5B")
      (footprint "eagle-import:SOD323-W")
      (libsource (lib "eagle-import") (part "DIODE-SOD323-W"))
    )
    (comp (ref "D37")
      (value "PDZ7.5B")
      (footprint "eagle-import:SOD323-W")
      (libsource (lib "eagle-import") (part "DIODE-SOD323-W"))
    )
    (comp (ref "D38")
      (value "PDZ7.5B")
      (footprint "eagle-import:SOD323-W")
      (libsource (lib "eagle-import") (part "DIODE-SOD323-W"))
    )
    (comp (ref "D39")
      (value "PDZ7.5B")
      (footprint "eagle-import:SOD323-W")
      (libsource (lib "eagle-import") (part "DIODE-SOD323-W"))
    )
    (comp (ref "D40")
      (value "PDZ7.5B")
      (footprint "eagle-import:SOD323-W")
      (libsource (lib "eagle-import") (part "DIODE-SOD323-W"))
    )
    (comp (ref "D41")
      (value "PDZ7.5B")
      (footprint "eagle-import:SOD323-W")
      (libsource (lib "eagle-import") (part "DIODE-SOD323-W"))
    )
    (comp (ref "D42")
      (value "PDZ7.5B")
      (footprint "eagle-import:SOD323-W")
      (libsource (lib "eagle-import") (part "DIODE-SOD323-W"))
    )
    (comp (ref "D43")
      (value "ZMM5265B-7")
      (footprint "eagle-import:MINIMELF")
      (libsource (lib "eagle-import") (part "DIODE-MINIMELF"))
    )
    (comp (ref "D44")
      (value "BAT46W")
      (footprint "eagle-import:SOD123")
      (libsource (lib "eagle-import") (part "DIODE-SOD123"))
    )
    (comp (ref "D45")
      (value "BAT46W")
      (footprint "eagle-import:SOD123")
      (libsource (lib "eagle-import") (part "DIODE-SOD123"))
    )
    (comp (ref "GND-10")
      (value "C-GRID-11-70553")
      (footprint "eagle-import:70553-11")
      (libsource (lib "eagle-import") (part "C-GRID-11-70553"))
    )
    (comp (ref "IC1")
      (value "ADUM1401")
      (footprint "eagle-import:SO16W")
      (libsource (lib "eagle-import") (part "ADUM1401"))
    )
    (comp (ref "IC2_\\")
      (value "ADUM1401")
      (footprint "eagle-import:SO16W")
      (libsource (lib "eagle-import") (part "ADUM1401"))
    )
    (comp (ref "IC3_")
      (value "ADUM1401")
      (footprint "eagle-import:SO16W")
      (libsource (lib "eagle-import") (part "ADUM1401"))
    )
    (comp (ref "L5")
      (value "IMC1210ER100K")
      (footprint "eagle-import:L3225M")
      (libsource (lib "eagle-import") (part "L-USL3225M"))
    )
    (comp (ref "L6")
      (value "IMC1210ER100K")
      (footprint "eagle-import:L3225M")
      (libsource (lib "eagle-import") (part "L-USL3225M"))
    )
    (comp (ref "L7")
      (value "IMC1210ER100K")
      (footprint "eagle-import:L3225M")
      (libsource (lib "eagle-import") (part "L-USL3225M"))
    )
    (comp (ref "L8")
      (value "IMC1210ER100K")
      (footprint "eagle-import:L3225M")
      (libsource (lib "eagle-import") (part "L-USL3225M"))
    )
    (comp (ref "L9")
      (value "IMC1210ER100K")
      (footprint "eagle-import:L3225M")
      (libsource (lib "eagle-import") (part "L-USL3225M"))
    )
    (comp (ref "L10")
      (value "IMC1210ER100K")
      (footprint "eagle-import:L3225M")
      (libsource (lib "eagle-import") (part "L-USL3225M"))
    )
    (comp (ref "L11")
      (value "IMC1210ER100K")
      (footprint "eagle-import:L3225M")
      (libsource (lib "eagle-import") (part "L-USL3225M"))
    )
    (comp (ref "L12")
      (value "IMC1210ER100K")
      (footprint "eagle-import:L3225M")
      (libsource (lib "eagle-import") (part "L-USL3225M"))
    )
    (comp (ref "L13")
      (value "IMC1210ER100K")
      (footprint "eagle-import:L3225M")
      (libsource (lib "eagle-import") (part "L-USL3225M"))
    )
    (comp (ref "L14")
      (value "IMC1210ER100K")
      (footprint "eagle-import:L3225M")
      (libsource (lib "eagle-import") (part "L-USL3225M"))
    )
    (comp (ref "L15")
      (value "IMC1210ER100K")
      (footprint "eagle-import:L3225M")
      (libsource (lib "eagle-import") (part "L-USL3225M"))
    )
    (comp (ref "L16")
      (value "IMC1210ER100K")
      (footprint "eagle-import:L3225M")
      (libsource (lib "eagle-import") (part "L-USL3225M"))
    )
    (comp (ref "L17")
      (value "IMC1210ER100K")
      (footprint "eagle-import:L3225M")
      (libsource (lib "eagle-import") (part "L-USL3225M"))
    )
    (comp (ref "L18")
      (value "IMC1210ER100K")
      (footprint "eagle-import:L3225M")
      (libsource (lib "eagle-import") (part "L-USL3225M"))
    )
    (comp (ref "L19")
      (value "IMC1210ER100K")
      (footprint "eagle-import:L3225M")
      (libsource (lib "eagle-import") (part "L-USL3225M"))
    )
    (comp (ref "L20")
      (value "IMC1210ER100K")
      (footprint "eagle-import:L3225M")
      (libsource (lib "eagle-import") (part "L-USL3225M"))
    )
    (comp (ref "L21")
      (value "IMC1210ER100K")
      (footprint "eagle-import:L3225M")
      (libsource (lib "eagle-import") (part "L-USL3225M"))
    )
    (comp (ref "L22")
      (value "IMC1210ER100K")
      (footprint "eagle-import:L3225M")
      (libsource (lib "eagle-import") (part "L-USL3225M"))
    )
    (comp (ref "L23")
      (value "IMC1210ER100K")
      (footprint "eagle-import:L3225M")
      (libsource (lib "eagle-import") (part "L-USL3225M"))
    )
    (comp (ref "L24")
      (value "IMC1210ER100K")
      (footprint "eagle-import:L3225M")
      (libsource (lib "eagle-import") (part "L-USL3225M"))
    )
    (comp (ref "L25")
      (value "IMC1210ER100K")
      (footprint "eagle-import:L3225M")
      (libsource (lib "eagle-import") (part "L-USL3225M"))
    )
    (comp (ref "L26")
      (value "IMC1210ER100K")
      (footprint "eagle-import:L3225M")
      (libsource (lib "eagle-import") (part "L-USL3225M"))
    )
    (comp (ref "L27")
      (value "IMC1210ER100K")
      (footprint "eagle-import:L3225M")
      (libsource (lib "eagle-import") (part "L-USL3225M"))
    )
    (comp (ref "L28")
      (value "IMC1210ER100K")
      (footprint "eagle-import:L3225M")
      (libsource (lib "eagle-import") (part "L-USL3225M"))
    )
    (comp (ref "L29")
      (value "IMC1210ER100K")
      (footprint "eagle-import:L3225M")
      (libsource (lib "eagle-import") (part "L-USL3225M"))
    )
    (comp (ref "L30")
      (value "IMC1210ER100K")
      (footprint "eagle-import:L3225M")
      (libsource (lib "eagle-import") (part "L-USL3225M"))
    )
    (comp (ref "L33")
      (value "IMC1210ER100K")
      (footprint "eagle-import:L3225M")
      (libsource (lib "eagle-import") (part "L-USL3225M"))
    )
    (comp (ref "L34")
      (value "IMC1210ER100K")
      (footprint "eagle-import:L3225M")
      (libsource (lib "eagle-import") (part "L-USL3225M"))
    )
    (comp (ref "L35")
      (value "IMC1210ER100K")
      (footprint "eagle-import:L3225M")
      (libsource (lib "eagle-import") (part "L-USL3225M"))
    )
    (comp (ref "L36")
      (value "IMC1210ER100K")
      (footprint "eagle-import:L3225M")
      (libsource (lib "eagle-import") (part "L-USL3225M"))
    )
    (comp (ref "L37")
      (value "IMC1210ER100K")
      (footprint "eagle-import:L3225M")
      (libsource (lib "eagle-import") (part "L-USL3225M"))
    )
    (comp (ref "L38")
      (value "IMC1210ER100K")
      (footprint "eagle-import:L3225M")
      (libsource (lib "eagle-import") (part "L-USL3225M"))
    )
    (comp (ref "L39")
      (value "IMC1210ER100K")
      (footprint "eagle-import:L3225M")
      (libsource (lib "eagle-import") (part "L-USL3225M"))
    )
    (comp (ref "L40")
      (value "IMC1210ER100K")
      (footprint "eagle-import:L3225M")
      (libsource (lib "eagle-import") (part "L-USL3225M"))
    )
    (comp (ref "L41")
      (value "IMC1210ER100K")
      (footprint "eagle-import:L3225M")
      (libsource (lib "eagle-import") (part "L-USL3225M"))
    )
    (comp (ref "L42")
      (value "IMC1210ER100K")
      (footprint "eagle-import:L3225M")
      (libsource (lib "eagle-import") (part "L-USL3225M"))
    )
    (comp (ref "L43")
      (value "IMC1210ER100K")
      (footprint "eagle-import:L3225M")
      (libsource (lib "eagle-import") (part "L-USL3225M"))
    )
    (comp (ref "L44")
      (value "IMC1210ER100K")
      (footprint "eagle-import:L3225M")
      (libsource (lib "eagle-import") (part "L-USL3225M"))
    )
    (comp (ref "L45")
      (value "IMC1210ER100K")
      (footprint "eagle-import:L3225M")
      (libsource (lib "eagle-import") (part "L-USL3225M"))
    )
    (comp (ref "LTC1")
      (value "LTC6803-4")
      (footprint "eagle-import:SSOP44")
      (libsource (lib "eagle-import") (part "LTC6803-4"))
    )
    (comp (ref "LTC1_C0")
      (value "TESTPAD-20MIL")
      (footprint "eagle-import:20MIL")
      (libsource (lib "eagle-import") (part "TESTPAD-20MIL"))
    )
    (comp (ref "LTC1_C1")
      (value "TESTPAD-20MIL")
      (footprint "eagle-import:20MIL")
      (libsource (lib "eagle-import") (part "TESTPAD-20MIL"))
    )
    (comp (ref "LTC1_C2")
      (value "TESTPAD-20MIL")
      (footprint "eagle-import:20MIL")
      (libsource (lib "eagle-import") (part "TESTPAD-20MIL"))
    )
    (comp (ref "LTC1_C3")
      (value "TESTPAD-20MIL")
      (footprint "eagle-import:20MIL")
      (libsource (lib "eagle-import") (part "TESTPAD-20MIL"))
    )
    (comp (ref "LTC1_C4")
      (value "TESTPAD-20MIL")
      (footprint "eagle-import:20MIL")
      (libsource (lib "eagle-import") (part "TESTPAD-20MIL"))
    )
    (comp (ref "LTC1_C5")
      (value "TESTPAD-20MIL")
      (footprint "eagle-import:20MIL")
      (libsource (lib "eagle-import") (part "TESTPAD-20MIL"))
    )
    (comp (ref "LTC1_C6")
      (value "TESTPAD-20MIL")
      (footprint "eagle-import:20MIL")
      (libsource (lib "eagle-import") (part "TESTPAD-20MIL"))
    )
    (comp (ref "LTC1_C7")
      (value "TESTPAD-20MIL")
      (footprint "eagle-import:20MIL")
      (libsource (lib "eagle-import") (part "TESTPAD-20MIL"))
    )
    (comp (ref "LTC1_C8")
      (value "TESTPAD-20MIL")
      (footprint "eagle-import:20MIL")
      (libsource (lib "eagle-import") (part "TESTPAD-20MIL"))
    )
    (comp (ref "LTC1_C9")
      (value "TESTPAD-20MIL")
      (footprint "eagle-import:20MIL")
      (libsource (lib "eagle-import") (part "TESTPAD-20MIL"))
    )
    (comp (ref "LTC1_C10")
      (value "TESTPAD-20MIL")
      (footprint "eagle-import:20MIL")
      (libsource (lib "eagle-import") (part "TESTPAD-20MIL"))
    )
    (comp (ref "LTC1_S1")
      (value "TESTPAD-20MIL")
      (footprint "eagle-import:20MIL")
      (libsource (lib "eagle-import") (part "TESTPAD-20MIL"))
    )
    (comp (ref "LTC1_S2")
      (value "TESTPAD-20MIL")
      (footprint "eagle-import:20MIL")
      (libsource (lib "eagle-import") (part "TESTPAD-20MIL"))
    )
    (comp (ref "LTC1_S3")
      (value "TESTPAD-20MIL")
      (footprint "eagle-import:20MIL")
      (libsource (lib "eagle-import") (part "TESTPAD-20MIL"))
    )
    (comp (ref "LTC1_S4")
      (value "TESTPAD-20MIL")
      (footprint "eagle-import:20MIL")
      (libsource (lib "eagle-import") (part "TESTPAD-20MIL"))
    )
    (comp (ref "LTC1_S5")
      (value "TESTPAD-20MIL")
      (footprint "eagle-import:20MIL")
      (libsource (lib "eagle-import") (part "TESTPAD-20MIL"))
    )
    (comp (ref "LTC1_S6")
      (value "TESTPAD-20MIL")
      (footprint "eagle-import:20MIL")
      (libsource (lib "eagle-import") (part "TESTPAD-20MIL"))
    )
    (comp (ref "LTC1_S7")
      (value "TESTPAD-20MIL")
      (footprint "eagle-import:20MIL")
      (libsource (lib "eagle-import") (part "TESTPAD-20MIL"))
    )
    (comp (ref "LTC1_S8")
      (value "TESTPAD-20MIL")
      (footprint "eagle-import:20MIL")
      (libsource (lib "eagle-import") (part "TESTPAD-20MIL"))
    )
    (comp (ref "LTC1_S9")
      (value "TESTPAD-20MIL")
      (footprint "eagle-import:20MIL")
      (libsource (lib "eagle-import") (part "TESTPAD-20MIL"))
    )
    (comp (ref "LTC1_S10")
      (value "TESTPAD-20MIL")
      (footprint "eagle-import:20MIL")
      (libsource (lib "eagle-import") (part "TESTPAD-20MIL"))
    )
    (comp (ref "LTC2")
      (value "LTC6803-4")
      (footprint "eagle-import:SSOP44")
      (libsource (lib "eagle-import") (part "LTC6803-4"))
    )
    (comp (ref "LTC2_C0")
      (value "TESTPAD-20MIL")
      (footprint "eagle-import:20MIL")
      (libsource (lib "eagle-import") (part "TESTPAD-20MIL"))
    )
    (comp (ref "LTC2_C1")
      (value "TESTPAD-20MIL")
      (footprint "eagle-import:20MIL")
      (libsource (lib "eagle-import") (part "TESTPAD-20MIL"))
    )
    (comp (ref "LTC2_C2")
      (value "TESTPAD-20MIL")
      (footprint "eagle-import:20MIL")
      (libsource (lib "eagle-import") (part "TESTPAD-20MIL"))
    )
    (comp (ref "LTC2_C3")
      (value "TESTPAD-20MIL")
      (footprint "eagle-import:20MIL")
      (libsource (lib "eagle-import") (part "TESTPAD-20MIL"))
    )
    (comp (ref "LTC2_C4")
      (value "TESTPAD-20MIL")
      (footprint "eagle-import:20MIL")
      (libsource (lib "eagle-import") (part "TESTPAD-20MIL"))
    )
    (comp (ref "LTC2_C5")
      (value "TESTPAD-20MIL")
      (footprint "eagle-import:20MIL")
      (libsource (lib "eagle-import") (part "TESTPAD-20MIL"))
    )
    (comp (ref "LTC2_C6")
      (value "TESTPAD-20MIL")
      (footprint "eagle-import:20MIL")
      (libsource (lib "eagle-import") (part "TESTPAD-20MIL"))
    )
    (comp (ref "LTC2_C7")
      (value "TESTPAD-20MIL")
      (footprint "eagle-import:20MIL")
      (libsource (lib "eagle-import") (part "TESTPAD-20MIL"))
    )
    (comp (ref "LTC2_C8")
      (value "TESTPAD-20MIL")
      (footprint "eagle-import:20MIL")
      (libsource (lib "eagle-import") (part "TESTPAD-20MIL"))
    )
    (comp (ref "LTC2_C9")
      (value "TESTPAD-20MIL")
      (footprint "eagle-import:20MIL")
      (libsource (lib "eagle-import") (part "TESTPAD-20MIL"))
    )
    (comp (ref "LTC2_C10")
      (value "TESTPAD-20MIL")
      (footprint "eagle-import:20MIL")
      (libsource (lib "eagle-import") (part "TESTPAD-20MIL"))
    )
    (comp (ref "LTC2_S1")
      (value "TESTPAD-20MIL")
      (footprint "eagle-import:20MIL")
      (libsource (lib "eagle-import") (part "TESTPAD-20MIL"))
    )
    (comp (ref "LTC2_S2")
      (value "TESTPAD-20MIL")
      (footprint "eagle-import:20MIL")
      (libsource (lib "eagle-import") (part "TESTPAD-20MIL"))
    )
    (comp (ref "LTC2_S3")
      (value "TESTPAD-20MIL")
      (footprint "eagle-import:20MIL")
      (libsource (lib "eagle-import") (part "TESTPAD-20MIL"))
    )
    (comp (ref "LTC2_S4")
      (value "TESTPAD-20MIL")
      (footprint "eagle-import:20MIL")
      (libsource (lib "eagle-import") (part "TESTPAD-20MIL"))
    )
    (comp (ref "LTC2_S5")
      (value "TESTPAD-20MIL")
      (footprint "eagle-import:20MIL")
      (libsource (lib "eagle-import") (part "TESTPAD-20MIL"))
    )
    (comp (ref "LTC2_S6")
      (value "TESTPAD-20MIL")
      (footprint "eagle-import:20MIL")
      (libsource (lib "eagle-import") (part "TESTPAD-20MIL"))
    )
    (comp (ref "LTC2_S7")
      (value "TESTPAD-20MIL")
      (footprint "eagle-import:20MIL")
      (libsource (lib "eagle-import") (part "TESTPAD-20MIL"))
    )
    (comp (ref "LTC2_S8")
      (value "TESTPAD-20MIL")
      (footprint "eagle-import:20MIL")
      (libsource (lib "eagle-import") (part "TESTPAD-20MIL"))
    )
    (comp (ref "LTC2_S9")
      (value "TESTPAD-20MIL")
      (footprint "eagle-import:20MIL")
      (libsource (lib "eagle-import") (part "TESTPAD-20MIL"))
    )
    (comp (ref "LTC2_S10")
      (value "TESTPAD-20MIL")
      (footprint "eagle-import:20MIL")
      (libsource (lib "eagle-import") (part "TESTPAD-20MIL"))
    )
    (comp (ref "LTC3")
      (value "LTC6803-4")
      (footprint "eagle-import:SSOP44")
      (libsource (lib "eagle-import") (part "LTC6803-4"))
    )
    (comp (ref "LTC3_C0")
      (value "TESTPAD-20MIL")
      (footprint "eagle-import:20MIL")
      (libsource (lib "eagle-import") (part "TESTPAD-20MIL"))
    )
    (comp (ref "LTC3_C1")
      (value "TESTPAD-20MIL")
      (footprint "eagle-import:20MIL")
      (libsource (lib "eagle-import") (part "TESTPAD-20MIL"))
    )
    (comp (ref "LTC3_C2")
      (value "TESTPAD-20MIL")
      (footprint "eagle-import:20MIL")
      (libsource (lib "eagle-import") (part "TESTPAD-20MIL"))
    )
    (comp (ref "LTC3_C3")
      (value "TESTPAD-20MIL")
      (footprint "eagle-import:20MIL")
      (libsource (lib "eagle-import") (part "TESTPAD-20MIL"))
    )
    (comp (ref "LTC3_C4")
      (value "TESTPAD-20MIL")
      (footprint "eagle-import:20MIL")
      (libsource (lib "eagle-import") (part "TESTPAD-20MIL"))
    )
    (comp (ref "LTC3_C5")
      (value "TESTPAD-20MIL")
      (footprint "eagle-import:20MIL")
      (libsource (lib "eagle-import") (part "TESTPAD-20MIL"))
    )
    (comp (ref "LTC3_C6")
      (value "TESTPAD-20MIL")
      (footprint "eagle-import:20MIL")
      (libsource (lib "eagle-import") (part "TESTPAD-20MIL"))
    )
    (comp (ref "LTC3_C7")
      (value "TESTPAD-20MIL")
      (footprint "eagle-import:20MIL")
      (libsource (lib "eagle-import") (part "TESTPAD-20MIL"))
    )
    (comp (ref "LTC3_C8")
      (value "TESTPAD-20MIL")
      (footprint "eagle-import:20MIL")
      (libsource (lib "eagle-import") (part "TESTPAD-20MIL"))
    )
    (comp (ref "LTC3_C9")
      (value "TESTPAD-20MIL")
      (footprint "eagle-import:20MIL")
      (libsource (lib "eagle-import") (part "TESTPAD-20MIL"))
    )
    (comp (ref "LTC3_C10")
      (value "TESTPAD-20MIL")
      (footprint "eagle-import:20MIL")
      (libsource (lib "eagle-import") (part "TESTPAD-20MIL"))
    )
    (comp (ref "LTC3_S1")
      (value "TESTPAD-20MIL")
      (footprint "eagle-import:20MIL")
      (libsource (lib "eagle-import") (part "TESTPAD-20MIL"))
    )
    (comp (ref "LTC3_S2")
      (value "TESTPAD-20MIL")
      (footprint "eagle-import:20MIL")
      (libsource (lib "eagle-import") (part "TESTPAD-20MIL"))
    )
    (comp (ref "LTC3_S3")
      (value "TESTPAD-20MIL")
      (footprint "eagle-import:20MIL")
      (libsource (lib "eagle-import") (part "TESTPAD-20MIL"))
    )
    (comp (ref "LTC3_S4")
      (value "TESTPAD-20MIL")
      (footprint "eagle-import:20MIL")
      (libsource (lib "eagle-import") (part "TESTPAD-20MIL"))
    )
    (comp (ref "LTC3_S5")
      (value "TESTPAD-20MIL")
      (footprint "eagle-import:20MIL")
      (libsource (lib "eagle-import") (part "TESTPAD-20MIL"))
    )
    (comp (ref "LTC3_S6")
      (value "TESTPAD-20MIL")
      (footprint "eagle-import:20MIL")
      (libsource (lib "eagle-import") (part "TESTPAD-20MIL"))
    )
    (comp (ref "LTC3_S7")
      (value "TESTPAD-20MIL")
      (footprint "eagle-import:20MIL")
      (libsource (lib "eagle-import") (part "TESTPAD-20MIL"))
    )
    (comp (ref "LTC3_S8")
      (value "TESTPAD-20MIL")
      (footprint "eagle-import:20MIL")
      (libsource (lib "eagle-import") (part "TESTPAD-20MIL"))
    )
    (comp (ref "LTC3_S9")
      (value "TESTPAD-20MIL")
      (footprint "eagle-import:20MIL")
      (libsource (lib "eagle-import") (part "TESTPAD-20MIL"))
    )
    (comp (ref "LTC3_S10")
      (value "TESTPAD-20MIL")
      (footprint "eagle-import:20MIL")
      (libsource (lib "eagle-import") (part "TESTPAD-20MIL"))
    )
    (comp (ref "MISO1_O")
      (value "PTR1PAD1-13")
      (footprint "eagle-import:P1-13")
      (libsource (lib "eagle-import") (part "PTR1PAD1-13"))
    )
    (comp (ref "MISO2_O")
      (value "PTR1PAD1-13")
      (footprint "eagle-import:P1-13")
      (libsource (lib "eagle-import") (part "PTR1PAD1-13"))
    )
    (comp (ref "MISO3_O")
      (value "PTR1PAD1-13")
      (footprint "eagle-import:P1-13")
      (libsource (lib "eagle-import") (part "PTR1PAD1-13"))
    )
    (comp (ref "MOSI1_O")
      (value "PTR1PAD1-13")
      (footprint "eagle-import:P1-13")
      (libsource (lib "eagle-import") (part "PTR1PAD1-13"))
    )
    (comp (ref "MOSI2_O")
      (value "PTR1PAD1-13")
      (footprint "eagle-import:P1-13")
      (libsource (lib "eagle-import") (part "PTR1PAD1-13"))
    )
    (comp (ref "MOSI3_O")
      (value "PTR1PAD1-13")
      (footprint "eagle-import:P1-13")
      (libsource (lib "eagle-import") (part "PTR1PAD1-13"))
    )
    (comp (ref "Q3")
      (value "SI2351DS")
      (footprint "eagle-import:MICRO3")
      (libsource (lib "eagle-import") (part "IRLML5203"))
    )
    (comp (ref "Q4")
      (value "SI2351DS")
      (footprint "eagle-import:MICRO3")
      (libsource (lib "eagle-import") (part "IRLML5203"))
    )
    (comp (ref "Q5")
      (value "SI2351DS")
      (footprint "eagle-import:MICRO3")
      (libsource (lib "eagle-import") (part "IRLML5203"))
    )
    (comp (ref "Q6")
      (value "SI2351DS")
      (footprint "eagle-import:MICRO3")
      (libsource (lib "eagle-import") (part "IRLML5203"))
    )
    (comp (ref "Q7")
      (value "SI2351DS")
      (footprint "eagle-import:MICRO3")
      (libsource (lib "eagle-import") (part "IRLML5203"))
    )
    (comp (ref "Q8")
      (value "SI2351DS")
      (footprint "eagle-import:MICRO3")
      (libsource (lib "eagle-import") (part "IRLML5203"))
    )
    (comp (ref "Q9")
      (value "SI2351DS")
      (footprint "eagle-import:MICRO3")
      (libsource (lib "eagle-import") (part "IRLML5203"))
    )
    (comp (ref "Q10")
      (value "SI2351DS")
      (footprint "eagle-import:MICRO3")
      (libsource (lib "eagle-import") (part "IRLML5203"))
    )
    (comp (ref "Q11")
      (value "SI2351DS")
      (footprint "eagle-import:MICRO3")
      (libsource (lib "eagle-import") (part "IRLML5203"))
    )
    (comp (ref "Q12")
      (value "SI2351DS")
      (footprint "eagle-import:MICRO3")
      (libsource (lib "eagle-import") (part "IRLML5203"))
    )
    (comp (ref "Q15")
      (value "SI2351DS")
      (footprint "eagle-import:MICRO3")
      (libsource (lib "eagle-import") (part "IRLML5203"))
    )
    (comp (ref "Q16")
      (value "SI2351DS")
      (footprint "eagle-import:MICRO3")
      (libsource (lib "eagle-import") (part "IRLML5203"))
    )
    (comp (ref "Q17")
      (value "SI2351DS")
      (footprint "eagle-import:MICRO3")
      (libsource (lib "eagle-import") (part "IRLML5203"))
    )
    (comp (ref "Q18")
      (value "SI2351DS")
      (footprint "eagle-import:MICRO3")
      (libsource (lib "eagle-import") (part "IRLML5203"))
    )
    (comp (ref "Q19")
      (value "SI2351DS")
      (footprint "eagle-import:MICRO3")
      (libsource (lib "eagle-import") (part "IRLML5203"))
    )
    (comp (ref "Q20")
      (value "SI2351DS")
      (footprint "eagle-import:MICRO3")
      (libsource (lib "eagle-import") (part "IRLML5203"))
    )
    (comp (ref "Q21")
      (value "SI2351DS")
      (footprint "eagle-import:MICRO3")
      (libsource (lib "eagle-import") (part "IRLML5203"))
    )
    (comp (ref "Q22")
      (value "SI2351DS")
      (footprint "eagle-import:MICRO3")
      (libsource (lib "eagle-import") (part "IRLML5203"))
    )
    (comp (ref "Q23")
      (value "SI2351DS")
      (footprint "eagle-import:MICRO3")
      (libsource (lib "eagle-import") (part "IRLML5203"))
    )
    (comp (ref "Q24")
      (value "SI2351DS")
      (footprint "eagle-import:MICRO3")
      (libsource (lib "eagle-import") (part "IRLML5203"))
    )
    (comp (ref "Q27")
      (value "SI2351DS")
      (footprint "eagle-import:MICRO3")
      (libsource (lib "eagle-import") (part "IRLML5203"))
    )
    (comp (ref "Q28")
      (value "SI2351DS")
      (footprint "eagle-import:MICRO3")
      (libsource (lib "eagle-import") (part "IRLML5203"))
    )
    (comp (ref "Q29")
      (value "SI2351DS")
      (footprint "eagle-import:MICRO3")
      (libsource (lib "eagle-import") (part "IRLML5203"))
    )
    (comp (ref "Q30")
      (value "SI2351DS")
      (footprint "eagle-import:MICRO3")
      (libsource (lib "eagle-import") (part "IRLML5203"))
    )
    (comp (ref "Q31")
      (value "SI2351DS")
      (footprint "eagle-import:MICRO3")
      (libsource (lib "eagle-import") (part "IRLML5203"))
    )
    (comp (ref "Q32")
      (value "SI2351DS")
      (footprint "eagle-import:MICRO3")
      (libsource (lib "eagle-import") (part "IRLML5203"))
    )
    (comp (ref "Q33")
      (value "SI2351DS")
      (footprint "eagle-import:MICRO3")
      (libsource (lib "eagle-import") (part "IRLML5203"))
    )
    (comp (ref "Q34")
      (value "SI2351DS")
      (footprint "eagle-import:MICRO3")
      (libsource (lib "eagle-import") (part "IRLML5203"))
    )
    (comp (ref "Q35")
      (value "SI2351DS")
      (footprint "eagle-import:MICRO3")
      (libsource (lib "eagle-import") (part "IRLML5203"))
    )
    (comp (ref "Q36")
      (value "SI2351DS")
      (footprint "eagle-import:MICRO3")
      (libsource (lib "eagle-import") (part "IRLML5203"))
    )
    (comp (ref "R5")
      (value "1M")
      (footprint "eagle-import:R1206")
      (libsource (lib "eagle-import") (part "R-US_R1206"))
    )
    (comp (ref "R10")
      (value "100 1%")
      (footprint "eagle-import:R1206")
      (libsource (lib "eagle-import") (part "R-US_R1206"))
    )
    (comp (ref "R11")
      (value "3.3K")
      (footprint "eagle-import:R1206")
      (libsource (lib "eagle-import") (part "R-US_R1206"))
    )
    (comp (ref "R12")
      (value "33 1W")
      (footprint "eagle-import:R2512")
      (libsource (lib "eagle-import") (part "R-US_R2512"))
    )
    (comp (ref "R14")
      (value "100 1%")
      (footprint "eagle-import:R1206")
      (libsource (lib "eagle-import") (part "R-US_R1206"))
    )
    (comp (ref "R15")
      (value "3.3K")
      (footprint "eagle-import:R1206")
      (libsource (lib "eagle-import") (part "R-US_R1206"))
    )
    (comp (ref "R16")
      (value "33 1W")
      (footprint "eagle-import:R2512")
      (libsource (lib "eagle-import") (part "R-US_R2512"))
    )
    (comp (ref "R18")
      (value "100 1%")
      (footprint "eagle-import:R1206")
      (libsource (lib "eagle-import") (part "R-US_R1206"))
    )
    (comp (ref "R19")
      (value "3.3K")
      (footprint "eagle-import:R1206")
      (libsource (lib "eagle-import") (part "R-US_R1206"))
    )
    (comp (ref "R20")
      (value "33 1W")
      (footprint "eagle-import:R2512")
      (libsource (lib "eagle-import") (part "R-US_R2512"))
    )
    (comp (ref "R22")
      (value "100 1%")
      (footprint "eagle-import:R1206")
      (libsource (lib "eagle-import") (part "R-US_R1206"))
    )
    (comp (ref "R23")
      (value "3.3K")
      (footprint "eagle-import:R1206")
      (libsource (lib "eagle-import") (part "R-US_R1206"))
    )
    (comp (ref "R24")
      (value "33 1W")
      (footprint "eagle-import:R2512")
      (libsource (lib "eagle-import") (part "R-US_R2512"))
    )
    (comp (ref "R26")
      (value "100 1%")
      (footprint "eagle-import:R1206")
      (libsource (lib "eagle-import") (part "R-US_R1206"))
    )
    (comp (ref "R27")
      (value "3.3K")
      (footprint "eagle-import:R1206")
      (libsource (lib "eagle-import") (part "R-US_R1206"))
    )
    (comp (ref "R28")
      (value "33 1W")
      (footprint "eagle-import:R2512")
      (libsource (lib "eagle-import") (part "R-US_R2512"))
    )
    (comp (ref "R30")
      (value "100 1%")
      (footprint "eagle-import:R1206")
      (libsource (lib "eagle-import") (part "R-US_R1206"))
    )
    (comp (ref "R31")
      (value "3.3K")
      (footprint "eagle-import:R1206")
      (libsource (lib "eagle-import") (part "R-US_R1206"))
    )
    (comp (ref "R32")
      (value "33 1W")
      (footprint "eagle-import:R2512")
      (libsource (lib "eagle-import") (part "R-US_R2512"))
    )
    (comp (ref "R34")
      (value "100 1%")
      (footprint "eagle-import:R1206")
      (libsource (lib "eagle-import") (part "R-US_R1206"))
    )
    (comp (ref "R35")
      (value "3.3K")
      (footprint "eagle-import:R1206")
      (libsource (lib "eagle-import") (part "R-US_R1206"))
    )
    (comp (ref "R36")
      (value "33 1W")
      (footprint "eagle-import:R2512")
      (libsource (lib "eagle-import") (part "R-US_R2512"))
    )
    (comp (ref "R38")
      (value "100 1%")
      (footprint "eagle-import:R1206")
      (libsource (lib "eagle-import") (part "R-US_R1206"))
    )
    (comp (ref "R39")
      (value "3.3K")
      (footprint "eagle-import:R1206")
      (libsource (lib "eagle-import") (part "R-US_R1206"))
    )
    (comp (ref "R40")
      (value "33 1W")
      (footprint "eagle-import:R2512")
      (libsource (lib "eagle-import") (part "R-US_R2512"))
    )
    (comp (ref "R42")
      (value "100 1%")
      (footprint "eagle-import:R1206")
      (libsource (lib "eagle-import") (part "R-US_R1206"))
    )
    (comp (ref "R43")
      (value "3.3K")
      (footprint "eagle-import:R1206")
      (libsource (lib "eagle-import") (part "R-US_R1206"))
    )
    (comp (ref "R44")
      (value "33 1W")
      (footprint "eagle-import:R2512")
      (libsource (lib "eagle-import") (part "R-US_R2512"))
    )
    (comp (ref "R46")
      (value "100 1%")
      (footprint "eagle-import:R1206")
      (libsource (lib "eagle-import") (part "R-US_R1206"))
    )
    (comp (ref "R47")
      (value "3.3K")
      (footprint "eagle-import:R1206")
      (libsource (lib "eagle-import") (part "R-US_R1206"))
    )
    (comp (ref "R48")
      (value "33 1W")
      (footprint "eagle-import:R2512")
      (libsource (lib "eagle-import") (part "R-US_R2512"))
    )
    (comp (ref "R50")
      (value "100")
      (footprint "eagle-import:R1206")
      (libsource (lib "eagle-import") (part "R-US_R1206"))
    )
    (comp (ref "R51")
      (value "100 1%")
      (footprint "eagle-import:R1206")
      (libsource (lib "eagle-import") (part "R-US_R1206"))
    )
    (comp (ref "R62")
      (value "100 1%")
      (footprint "eagle-import:R1206")
      (libsource (lib "eagle-import") (part "R-US_R1206"))
    )
    (comp (ref "R63")
      (value "3.3K")
      (footprint "eagle-import:R1206")
      (libsource (lib "eagle-import") (part "R-US_R1206"))
    )
    (comp (ref "R64")
      (value "33 1W")
      (footprint "eagle-import:R2512")
      (libsource (lib "eagle-import") (part "R-US_R2512"))
    )
    (comp (ref "R66")
      (value "100 1%")
      (footprint "eagle-import:R1206")
      (libsource (lib "eagle-import") (part "R-US_R1206"))
    )
    (comp (ref "R67")
      (value "3.3K")
      (footprint "eagle-import:R1206")
      (libsource (lib "eagle-import") (part "R-US_R1206"))
    )
    (comp (ref "R68")
      (value "33 1W")
      (footprint "eagle-import:R2512")
      (libsource (lib "eagle-import") (part "R-US_R2512"))
    )
    (comp (ref "R70")
      (value "100 1%")
      (footprint "eagle-import:R1206")
      (libsource (lib "eagle-import") (part "R-US_R1206"))
    )
    (comp (ref "R71")
      (value "3.3K")
      (footprint "eagle-import:R1206")
      (libsource (lib "eagle-import") (part "R-US_R1206"))
    )
    (comp (ref "R72")
      (value "33 1W")
      (footprint "eagle-import:R2512")
      (libsource (lib "eagle-import") (part "R-US_R2512"))
    )
    (comp (ref "R74")
      (value "100 1%")
      (footprint "eagle-import:R1206")
      (libsource (lib "eagle-import") (part "R-US_R1206"))
    )
    (comp (ref "R75")
      (value "3.3K")
      (footprint "eagle-import:R1206")
      (libsource (lib "eagle-import") (part "R-US_R1206"))
    )
    (comp (ref "R76")
      (value "33 1W")
      (footprint "eagle-import:R2512")
      (libsource (lib "eagle-import") (part "R-US_R2512"))
    )
    (comp (ref "R78")
      (value "100 1%")
      (footprint "eagle-import:R1206")
      (libsource (lib "eagle-import") (part "R-US_R1206"))
    )
    (comp (ref "R79")
      (value "3.3K")
      (footprint "eagle-import:R1206")
      (libsource (lib "eagle-import") (part "R-US_R1206"))
    )
    (comp (ref "R80")
      (value "33 1W")
      (footprint "eagle-import:R2512")
      (libsource (lib "eagle-import") (part "R-US_R2512"))
    )
    (comp (ref "R82")
      (value "100 1%")
      (footprint "eagle-import:R1206")
      (libsource (lib "eagle-import") (part "R-US_R1206"))
    )
    (comp (ref "R83")
      (value "3.3K")
      (footprint "eagle-import:R1206")
      (libsource (lib "eagle-import") (part "R-US_R1206"))
    )
    (comp (ref "R84")
      (value "33 1W")
      (footprint "eagle-import:R2512")
      (libsource (lib "eagle-import") (part "R-US_R2512"))
    )
    (comp (ref "R86")
      (value "100 1%")
      (footprint "eagle-import:R1206")
      (libsource (lib "eagle-import") (part "R-US_R1206"))
    )
    (comp (ref "R87")
      (value "3.3K")
      (footprint "eagle-import:R1206")
      (libsource (lib "eagle-import") (part "R-US_R1206"))
    )
    (comp (ref "R88")
      (value "33 1W")
      (footprint "eagle-import:R2512")
      (libsource (lib "eagle-import") (part "R-US_R2512"))
    )
    (comp (ref "R90")
      (value "100 1%")
      (footprint "eagle-import:R1206")
      (libsource (lib "eagle-import") (part "R-US_R1206"))
    )
    (comp (ref "R91")
      (value "3.3K")
      (footprint "eagle-import:R1206")
      (libsource (lib "eagle-import") (part "R-US_R1206"))
    )
    (comp (ref "R92")
      (value "33 1W")
      (footprint "eagle-import:R2512")
      (libsource (lib "eagle-import") (part "R-US_R2512"))
    )
    (comp (ref "R94")
      (value "100 1%")
      (footprint "eagle-import:R1206")
      (libsource (lib "eagle-import") (part "R-US_R1206"))
    )
    (comp (ref "R95")
      (value "3.3K")
      (footprint "eagle-import:R1206")
      (libsource (lib "eagle-import") (part "R-US_R1206"))
    )
    (comp (ref "R96")
      (value "33 1W")
      (footprint "eagle-import:R2512")
      (libsource (lib "eagle-import") (part "R-US_R2512"))
    )
    (comp (ref "R98")
      (value "100 1%")
      (footprint "eagle-import:R1206")
      (libsource (lib "eagle-import") (part "R-US_R1206"))
    )
    (comp (ref "R99")
      (value "3.3K")
      (footprint "eagle-import:R1206")
      (libsource (lib "eagle-import") (part "R-US_R1206"))
    )
    (comp (ref "R100")
      (value "33 1W")
      (footprint "eagle-import:R2512")
      (libsource (lib "eagle-import") (part "R-US_R2512"))
    )
    (comp (ref "R102")
      (value "100")
      (footprint "eagle-import:R1206")
      (libsource (lib "eagle-import") (part "R-US_R1206"))
    )
    (comp (ref "R103")
      (value "100 1%")
      (footprint "eagle-import:R1206")
      (libsource (lib "eagle-import") (part "R-US_R1206"))
    )
    (comp (ref "R104")
      (value "1M")
      (footprint "eagle-import:R1206")
      (libsource (lib "eagle-import") (part "R-US_R1206"))
    )
    (comp (ref "R113")
      (value "100 1%")
      (footprint "eagle-import:R1206")
      (libsource (lib "eagle-import") (part "R-US_R1206"))
    )
    (comp (ref "R114")
      (value "3.3K")
      (footprint "eagle-import:R1206")
      (libsource (lib "eagle-import") (part "R-US_R1206"))
    )
    (comp (ref "R115")
      (value "33 1W")
      (footprint "eagle-import:R2512")
      (libsource (lib "eagle-import") (part "R-US_R2512"))
    )
    (comp (ref "R117")
      (value "100 1%")
      (footprint "eagle-import:R1206")
      (libsource (lib "eagle-import") (part "R-US_R1206"))
    )
    (comp (ref "R118")
      (value "3.3K")
      (footprint "eagle-import:R1206")
      (libsource (lib "eagle-import") (part "R-US_R1206"))
    )
    (comp (ref "R119")
      (value "33 1W")
      (footprint "eagle-import:R2512")
      (libsource (lib "eagle-import") (part "R-US_R2512"))
    )
    (comp (ref "R121")
      (value "100 1%")
      (footprint "eagle-import:R1206")
      (libsource (lib "eagle-import") (part "R-US_R1206"))
    )
    (comp (ref "R122")
      (value "3.3K")
      (footprint "eagle-import:R1206")
      (libsource (lib "eagle-import") (part "R-US_R1206"))
    )
    (comp (ref "R123")
      (value "33 1W")
      (footprint "eagle-import:R2512")
      (libsource (lib "eagle-import") (part "R-US_R2512"))
    )
    (comp (ref "R125")
      (value "100 1%")
      (footprint "eagle-import:R1206")
      (libsource (lib "eagle-import") (part "R-US_R1206"))
    )
    (comp (ref "R126")
      (value "3.3K")
      (footprint "eagle-import:R1206")
      (libsource (lib "eagle-import") (part "R-US_R1206"))
    )
    (comp (ref "R127")
      (value "33 1W")
      (footprint "eagle-import:R2512")
      (libsource (lib "eagle-import") (part "R-US_R2512"))
    )
    (comp (ref "R129")
      (value "100 1%")
      (footprint "eagle-import:R1206")
      (libsource (lib "eagle-import") (part "R-US_R1206"))
    )
    (comp (ref "R130")
      (value "3.3K")
      (footprint "eagle-import:R1206")
      (libsource (lib "eagle-import") (part "R-US_R1206"))
    )
    (comp (ref "R131")
      (value "33 1W")
      (footprint "eagle-import:R2512")
      (libsource (lib "eagle-import") (part "R-US_R2512"))
    )
    (comp (ref "R133")
      (value "100 1%")
      (footprint "eagle-import:R1206")
      (libsource (lib "eagle-import") (part "R-US_R1206"))
    )
    (comp (ref "R134")
      (value "3.3K")
      (footprint "eagle-import:R1206")
      (libsource (lib "eagle-import") (part "R-US_R1206"))
    )
    (comp (ref "R135")
      (value "33 1W")
      (footprint "eagle-import:R2512")
      (libsource (lib "eagle-import") (part "R-US_R2512"))
    )
    (comp (ref "R137")
      (value "100 1%")
      (footprint "eagle-import:R1206")
      (libsource (lib "eagle-import") (part "R-US_R1206"))
    )
    (comp (ref "R138")
      (value "3.3K")
      (footprint "eagle-import:R1206")
      (libsource (lib "eagle-import") (part "R-US_R1206"))
    )
    (comp (ref "R139")
      (value "33 1W")
      (footprint "eagle-import:R2512")
      (libsource (lib "eagle-import") (part "R-US_R2512"))
    )
    (comp (ref "R141")
      (value "100 1%")
      (footprint "eagle-import:R1206")
      (libsource (lib "eagle-import") (part "R-US_R1206"))
    )
    (comp (ref "R142")
      (value "3.3K")
      (footprint "eagle-import:R1206")
      (libsource (lib "eagle-import") (part "R-US_R1206"))
    )
    (comp (ref "R143")
      (value "33 1W")
      (footprint "eagle-import:R2512")
      (libsource (lib "eagle-import") (part "R-US_R2512"))
    )
    (comp (ref "R145")
      (value "100 1%")
      (footprint "eagle-import:R1206")
      (libsource (lib "eagle-import") (part "R-US_R1206"))
    )
    (comp (ref "R146")
      (value "3.3K")
      (footprint "eagle-import:R1206")
      (libsource (lib "eagle-import") (part "R-US_R1206"))
    )
    (comp (ref "R147")
      (value "33 1W")
      (footprint "eagle-import:R2512")
      (libsource (lib "eagle-import") (part "R-US_R2512"))
    )
    (comp (ref "R149")
      (value "100 1%")
      (footprint "eagle-import:R1206")
      (libsource (lib "eagle-import") (part "R-US_R1206"))
    )
    (comp (ref "R150")
      (value "3.3K")
      (footprint "eagle-import:R1206")
      (libsource (lib "eagle-import") (part "R-US_R1206"))
    )
    (comp (ref "R151")
      (value "33 1W")
      (footprint "eagle-import:R2512")
      (libsource (lib "eagle-import") (part "R-US_R2512"))
    )
    (comp (ref "R153")
      (value "100")
      (footprint "eagle-import:R1206")
      (libsource (lib "eagle-import") (part "R-US_R1206"))
    )
    (comp (ref "R154")
      (value "100 1%")
      (footprint "eagle-import:R1206")
      (libsource (lib "eagle-import") (part "R-US_R1206"))
    )
    (comp (ref "R155")
      (value "1M")
      (footprint "eagle-import:R1206")
      (libsource (lib "eagle-import") (part "R-US_R1206"))
    )
    (comp (ref "R163")
      (value "1M")
      (footprint "eagle-import:R1206")
      (libsource (lib "eagle-import") (part "resistor_R-US_R1206"))
    )
    (comp (ref "R164")
      (value "1M")
      (footprint "eagle-import:R1206")
      (libsource (lib "eagle-import") (part "resistor_R-US_R1206"))
    )
    (comp (ref "R165")
      (value "1M")
      (footprint "eagle-import:R1206")
      (libsource (lib "eagle-import") (part "resistor_R-US_R1206"))
    )
    (comp (ref "R166")
      (value "1M")
      (footprint "eagle-import:R1206")
      (libsource (lib "eagle-import") (part "resistor_R-US_R1206"))
    )
    (comp (ref "R167")
      (value "1M")
      (footprint "eagle-import:R1206")
      (libsource (lib "eagle-import") (part "resistor_R-US_R1206"))
    )
    (comp (ref "R168")
      (value "1M")
      (footprint "eagle-import:R1206")
      (libsource (lib "eagle-import") (part "resistor_R-US_R1206"))
    )
    (comp (ref "SCK1")
      (value "PTR1PAD1-13")
      (footprint "eagle-import:P1-13")
      (libsource (lib "eagle-import") (part "PTR1PAD1-13"))
    )
    (comp (ref "SCK1_O")
      (value "PTR1PAD1-13")
      (footprint "eagle-import:P1-13")
      (libsource (lib "eagle-import") (part "PTR1PAD1-13"))
    )
    (comp (ref "SCK2")
      (value "PTR1PAD1-13")
      (footprint "eagle-import:P1-13")
      (libsource (lib "eagle-import") (part "PTR1PAD1-13"))
    )
    (comp (ref "SCK2_O")
      (value "PTR1PAD1-13")
      (footprint "eagle-import:P1-13")
      (libsource (lib "eagle-import") (part "PTR1PAD1-13"))
    )
    (comp (ref "SCK3")
      (value "PTR1PAD1-13")
      (footprint "eagle-import:P1-13")
      (libsource (lib "eagle-import") (part "PTR1PAD1-13"))
    )
    (comp (ref "SCK3_O")
      (value "PTR1PAD1-13")
      (footprint "eagle-import:P1-13")
      (libsource (lib "eagle-import") (part "PTR1PAD1-13"))
    )
    (comp (ref "SDI1")
      (value "PTR1PAD1-13")
      (footprint "eagle-import:P1-13")
      (libsource (lib "eagle-import") (part "PTR1PAD1-13"))
    )
    (comp (ref "SDI2")
      (value "PTR1PAD1-13")
      (footprint "eagle-import:P1-13")
      (libsource (lib "eagle-import") (part "PTR1PAD1-13"))
    )
    (comp (ref "SDI3")
      (value "PTR1PAD1-13")
      (footprint "eagle-import:P1-13")
      (libsource (lib "eagle-import") (part "PTR1PAD1-13"))
    )
    (comp (ref "SDO1")
      (value "PTR1PAD1-13")
      (footprint "eagle-import:P1-13")
      (libsource (lib "eagle-import") (part "PTR1PAD1-13"))
    )
    (comp (ref "SDO2")
      (value "PTR1PAD1-13")
      (footprint "eagle-import:P1-13")
      (libsource (lib "eagle-import") (part "PTR1PAD1-13"))
    )
    (comp (ref "SDO3")
      (value "PTR1PAD1-13")
      (footprint "eagle-import:P1-13")
      (libsource (lib "eagle-import") (part "PTR1PAD1-13"))
    )
    (comp (ref "U$8")
      (value "3ROW_6POS")
      (footprint "eagle-import:3ROW_6POS")
      (libsource (lib "eagle-import") (part "3ROW_6POS"))
    )
    (comp (ref "U$9")
      (value "3ROW_6POS")
      (footprint "eagle-import:3ROW_6POS")
      (libsource (lib "eagle-import") (part "3ROW_6POS"))
    )
    (comp (ref "U$10")
      (value "3ROW_6POS")
      (footprint "eagle-import:3ROW_6POS")
      (libsource (lib "eagle-import") (part "3ROW_6POS"))
    )
    (comp (ref "V+1")
      (value "PTR1PAD1-13")
      (footprint "eagle-import:P1-13")
      (libsource (lib "eagle-import") (part "PTR1PAD1-13"))
    )
    (comp (ref "V+2")
      (value "PTR1PAD1-13")
      (footprint "eagle-import:P1-13")
      (libsource (lib "eagle-import") (part "PTR1PAD1-13"))
    )
    (comp (ref "V+3")
      (value "PTR1PAD1-13")
      (footprint "eagle-import:P1-13")
      (libsource (lib "eagle-import") (part "PTR1PAD1-13"))
    )
    (comp (ref "V-1")
      (value "PTR1PAD1-13")
      (footprint "eagle-import:P1-13")
      (libsource (lib "eagle-import") (part "PTR1PAD1-13"))
    )
    (comp (ref "V-2")
      (value "PTR1PAD1-13")
      (footprint "eagle-import:P1-13")
      (libsource (lib "eagle-import") (part "PTR1PAD1-13"))
    )
    (comp (ref "V-3")
      (value "PTR1PAD1-13")
      (footprint "eagle-import:P1-13")
      (libsource (lib "eagle-import") (part "PTR1PAD1-13"))
    )
    (comp (ref "VREG1")
      (value "TESTPAD-20MIL")
      (footprint "eagle-import:20MIL")
      (libsource (lib "eagle-import") (part "TESTPAD-20MIL"))
    )
    (comp (ref "VREG2")
      (value "TESTPAD-20MIL")
      (footprint "eagle-import:20MIL")
      (libsource (lib "eagle-import") (part "TESTPAD-20MIL"))
    )
    (comp (ref "VREG3")
      (value "TESTPAD-20MIL")
      (footprint "eagle-import:20MIL")
      (libsource (lib "eagle-import") (part "TESTPAD-20MIL"))
    )
    (comp (ref "PROGRAM")
      (value "C-GRID-06-70543")
      (footprint "eagle-import:70543-06")
      (libsource (lib "eagle-import") (part "C-GRID-06-70543"))
    )
  )
  (nets
    (net (code "1") (name "+3V3") (class "Default")
      (node (ref "C16") (pin "1") (pinfunction "1_1") (pintype "passive"))
      (node (ref "C48") (pin "1") (pinfunction "1_1") (pintype "passive"))
      (node (ref "C52") (pin "1") (pinfunction "1_1") (pintype "passive"))
      (node (ref "IC3") (pin "2") (pinfunction "VOUT_2") (pintype "output"))
      (node (ref "PROGRAM") (pin "5") (pinfunction "S_5") (pintype "passive"))
      (node (ref "R1") (pin "2") (pinfunction "2_2") (pintype "passive"))
      (node (ref "R52") (pin "1") (pinfunction "1_1") (pintype "passive"))
      (node (ref "U$12") (pin "P$1") (pinfunction "TP_P$1") (pintype "input"))
      (node (ref "U$2") (pin "13") (pinfunction "VDD_13") (pintype "bidirectional"))
      (node (ref "U$2") (pin "28") (pinfunction "AVDD_28") (pintype "bidirectional"))
      (node (ref "U$3") (pin "1") (pinfunction "TRI_1") (pintype "input"))
      (node (ref "U$3") (pin "4") (pinfunction "VDD_4") (pintype "power_in"))
    )
    (net (code "2") (name "+5V") (class "Default")
      (node (ref "AIN0") (pin "2") (pinfunction "S_2") (pintype "passive"))
      (node (ref "AIN1") (pin "2") (pinfunction "S_2") (pintype "passive"))
      (node (ref "AIN2") (pin "2") (pinfunction "S_2") (pintype "passive"))
      (node (ref "AIN3") (pin "2") (pinfunction "S_2") (pintype "passive"))
      (node (ref "AIN4") (pin "2") (pinfunction "S_2") (pintype "passive"))
      (node (ref "C54") (pin "1") (pinfunction "1_1") (pintype "passive"))
      (node (ref "IC1") (pin "1") (pinfunction "VDD1_1") (pintype "power_in"))
      (node (ref "IC1") (pin "7") (pinfunction "VE1_7") (pintype "passive"))
      (node (ref "IC2") (pin "2") (pinfunction "VO_2") (pintype "passive"))
      (node (ref "IC2_\\") (pin "1") (pinfunction "VDD1_1") (pintype "power_in"))
      (node (ref "IC2_\\") (pin "7") (pinfunction "VE1_7") (pintype "passive"))
      (node (ref "IC3_") (pin "1") (pinfunction "VDD1_1") (pintype "power_in"))
      (node (ref "IC3_") (pin "7") (pinfunction "VE1_7") (pintype "passive"))
      (node (ref "U$1") (pin "16") (pinfunction "V+_16") (pintype "bidirectional"))
      (node (ref "U$13") (pin "P$1") (pinfunction "TP_P$1") (pintype "input"))
      (node (ref "U$4") (pin "8") (pinfunction "V+_8") (pintype "bidirectional"))
      (node (ref "U$6") (pin "16") (pinfunction "VDD_16") (pintype "bidirectional"))
    )
    (net (code "3") (name "12V") (class "Default")
      (node (ref "12V") (pin "4") (pinfunction "S_4") (pintype "passive"))
      (node (ref "C50") (pin "1") (pinfunction "1_1") (pintype "passive"))
      (node (ref "C51") (pin "1") (pinfunction "1_1") (pintype "passive"))
      (node (ref "C53") (pin "1") (pinfunction "1_1") (pintype "passive"))
      (node (ref "IC2") (pin "1") (pinfunction "VI_1") (pintype "input"))
      (node (ref "IC3") (pin "3") (pinfunction "VIN_3") (pintype "input"))
      (node (ref "R169") (pin "2") (pinfunction "2_2") (pintype "passive"))
      (node (ref "U$7") (pin "1") (pinfunction "IN_1") (pintype "bidirectional"))
    )
    (net (code "4") (name "ADC_CS") (class "Default")
      (node (ref "U$2") (pin "26") (pinfunction "RB15_26") (pintype "bidirectional"))
      (node (ref "U$33") (pin "P$1") (pinfunction "TP_P$1") (pintype "input"))
      (node (ref "U$6") (pin "10") (pinfunction "CS_10") (pintype "bidirectional"))
    )
    (net (code "5") (name "ADC_MISO") (class "Default")
      (node (ref "U$2") (pin "17") (pinfunction "RB8_17") (pintype "bidirectional"))
      (node (ref "U$26") (pin "P$1") (pinfunction "TP_P$1") (pintype "input"))
      (node (ref "U$6") (pin "12") (pinfunction "DOUT_12") (pintype "bidirectional"))
    )
    (net (code "6") (name "AGND") (class "Default")
      (node (ref "C19") (pin "2") (pinfunction "2_2") (pintype "passive"))
      (node (ref "C20") (pin "2") (pinfunction "2_2") (pintype "passive"))
      (node (ref "C21") (pin "2") (pinfunction "2_2") (pintype "passive"))
      (node (ref "C23") (pin "2") (pinfunction "2_2") (pintype "passive"))
      (node (ref "C24") (pin "2") (pinfunction "2_2") (pintype "passive"))
      (node (ref "C25") (pin "2") (pinfunction "2_2") (pintype "passive"))
      (node (ref "C26") (pin "2") (pinfunction "2_2") (pintype "passive"))
      (node (ref "C27") (pin "2") (pinfunction "2_2") (pintype "passive"))
      (node (ref "C28") (pin "2") (pinfunction "2_2") (pintype "passive"))
      (node (ref "C29") (pin "2") (pinfunction "2_2") (pintype "passive"))
      (node (ref "C30") (pin "2") (pinfunction "2_2") (pintype "passive"))
      (node (ref "C31") (pin "2") (pinfunction "2_2") (pintype "passive"))
      (node (ref "C32") (pin "2") (pinfunction "2_2") (pintype "passive"))
      (node (ref "D28") (pin "A") (pinfunction "A_A") (pintype "passive"))
      (node (ref "D29") (pin "A") (pinfunction "A_A") (pintype "passive"))
      (node (ref "D30") (pin "A") (pinfunction "A_A") (pintype "passive"))
      (node (ref "IC2_\\") (pin "15") (pinfunction "GND2_15") (pintype "power_in"))
      (node (ref "IC2_\\") (pin "9") (pinfunction "GND2_9") (pintype "power_in"))
      (node (ref "L29") (pin "2") (pinfunction "2_2") (pintype "passive"))
      (node (ref "LTC2") (pin "P$27") (pinfunction "V-_P$27") (pintype "bidirectional"))
      (node (ref "LTC2") (pin "P$28") (pinfunction "NC_P$28") (pintype "bidirectional"))
      (node (ref "LTC2") (pin "P$29") (pinfunction "V_TEMP1_P$29") (pintype "bidirectional"))
      (node (ref "LTC2") (pin "P$30") (pinfunction "V_TEMP2_P$30") (pintype "bidirectional"))
      (node (ref "LTC2") (pin "P$35") (pinfunction "GPIO1_P$35") (pintype "bidirectional"))
      (node (ref "LTC2") (pin "P$36") (pinfunction "GPIO2_P$36") (pintype "bidirectional"))
      (node (ref "U$9") (pin "1") (pinfunction "1_1") (pintype "passive"))
      (node (ref "U$9") (pin "10") (pinfunction "1_10") (pintype "passive"))
      (node (ref "U$9") (pin "13") (pinfunction "1_13") (pintype "passive"))
      (node (ref "U$9") (pin "16") (pinfunction "1_16") (pintype "passive"))
      (node (ref "U$9") (pin "4") (pinfunction "1_4") (pintype "passive"))
      (node (ref "U$9") (pin "7") (pinfunction "1_7") (pintype "passive"))
      (node (ref "V-2") (pin "TP") (pinfunction "TP_TP") (pintype "input"))
    )
    (net (code "7") (name "CELL0") (class "Default")
      (node (ref "GND-10") (pin "1") (pinfunction "S_1") (pintype "passive"))
      (node (ref "L16") (pin "1") (pinfunction "1_1") (pintype "passive"))
      (node (ref "L17") (pin "1") (pinfunction "1_1") (pintype "passive"))
    )
    (net (code "8") (name "CELL1") (class "Default")
      (node (ref "GND-10") (pin "2") (pinfunction "S_2") (pintype "passive"))
      (node (ref "L14") (pin "1") (pinfunction "1_1") (pintype "passive"))
    )
    (net (code "9") (name "CELL2") (class "Default")
      (node (ref "GND-10") (pin "3") (pinfunction "S_3") (pintype "passive"))
      (node (ref "L13") (pin "1") (pinfunction "1_1") (pintype "passive"))
    )
    (net (code "10") (name "CELL3") (class "Default")
      (node (ref "GND-10") (pin "4") (pinfunction "S_4") (pintype "passive"))
      (node (ref "L12") (pin "1") (pinfunction "1_1") (pintype "passive"))
    )
    (net (code "11") (name "CELL4") (class "Default")
      (node (ref "GND-10") (pin "5") (pinfunction "S_5") (pintype "passive"))
      (node (ref "L11") (pin "1") (pinfunction "1_1") (pintype "passive"))
    )
    (net (code "12") (name "CELL5") (class "Default")
      (node (ref "GND-10") (pin "6") (pinfunction "S_6") (pintype "passive"))
      (node (ref "L10") (pin "1") (pinfunction "1_1") (pintype "passive"))
    )
    (net (code "13") (name "CELL6") (class "Default")
      (node (ref "GND-10") (pin "7") (pinfunction "S_7") (pintype "passive"))
      (node (ref "L9") (pin "1") (pinfunction "1_1") (pintype "passive"))
    )
    (net (code "14") (name "CELL7") (class "Default")
      (node (ref "GND-10") (pin "8") (pinfunction "S_8") (pintype "passive"))
      (node (ref "L8") (pin "1") (pinfunction "1_1") (pintype "passive"))
    )
    (net (code "15") (name "CELL8") (class "Default")
      (node (ref "GND-10") (pin "9") (pinfunction "S_9") (pintype "passive"))
      (node (ref "L7") (pin "1") (pinfunction "1_1") (pintype "passive"))
    )
    (net (code "16") (name "CELL9") (class "Default")
      (node (ref "GND-10") (pin "10") (pinfunction "S_10") (pintype "passive"))
      (node (ref "L6") (pin "1") (pinfunction "1_1") (pintype "passive"))
    )
    (net (code "17") (name "CELL10") (class "Default")
      (node (ref "GND-10") (pin "11") (pinfunction "S_11") (pintype "passive"))
      (node (ref "L15") (pin "1") (pinfunction "1_1") (pintype "passive"))
      (node (ref "L29") (pin "1") (pinfunction "1_1") (pintype "passive"))
      (node (ref "L30") (pin "1") (pinfunction "1_1") (pintype "passive"))
      (node (ref "L5") (pin "1") (pinfunction "1_1") (pintype "passive"))
    )
    (net (code "18") (name "CELL11") (class "Default")
      (node (ref "CELLS-11-20") (pin "1") (pinfunction "S_1") (pintype "passive"))
      (node (ref "L27") (pin "1") (pinfunction "1_1") (pintype "passive"))
    )
    (net (code "19") (name "CELL12") (class "Default")
      (node (ref "CELLS-11-20") (pin "2") (pinfunction "S_2") (pintype "passive"))
      (node (ref "L26") (pin "1") (pinfunction "1_1") (pintype "passive"))
    )
    (net (code "20") (name "CELL13") (class "Default")
      (node (ref "CELLS-11-20") (pin "3") (pinfunction "S_3") (pintype "passive"))
      (node (ref "L25") (pin "1") (pinfunction "1_1") (pintype "passive"))
    )
    (net (code "21") (name "CELL14") (class "Default")
      (node (ref "CELLS-11-20") (pin "4") (pinfunction "S_4") (pintype "passive"))
      (node (ref "L24") (pin "1") (pinfunction "1_1") (pintype "passive"))
    )
    (net (code "22") (name "CELL15") (class "Default")
      (node (ref "CELLS-11-20") (pin "5") (pinfunction "S_5") (pintype "passive"))
      (node (ref "L23") (pin "1") (pinfunction "1_1") (pintype "passive"))
    )
    (net (code "23") (name "CELL16") (class "Default")
      (node (ref "CELLS-11-20") (pin "6") (pinfunction "S_6") (pintype "passive"))
      (node (ref "L22") (pin "1") (pinfunction "1_1") (pintype "passive"))
    )
    (net (code "24") (name "CELL17") (class "Default")
      (node (ref "CELLS-11-20") (pin "7") (pinfunction "S_7") (pintype "passive"))
      (node (ref "L21") (pin "1") (pinfunction "1_1") (pintype "passive"))
    )
    (net (code "25") (name "CELL18") (class "Default")
      (node (ref "CELLS-11-20") (pin "8") (pinfunction "S_8") (pintype "passive"))
      (node (ref "L20") (pin "1") (pinfunction "1_1") (pintype "passive"))
    )
    (net (code "26") (name "CELL19") (class "Default")
      (node (ref "CELLS-11-20") (pin "9") (pinfunction "S_9") (pintype "passive"))
      (node (ref "L19") (pin "1") (pinfunction "1_1") (pintype "passive"))
    )
    (net (code "27") (name "CELL20") (class "Default")
      (node (ref "CELLS-11-20") (pin "10") (pinfunction "S_10") (pintype "passive"))
      (node (ref "L18") (pin "1") (pinfunction "1_1") (pintype "passive"))
      (node (ref "L28") (pin "1") (pinfunction "1_1") (pintype "passive"))
      (node (ref "L44") (pin "1") (pinfunction "1_1") (pintype "passive"))
      (node (ref "L45") (pin "1") (pinfunction "1_1") (pintype "passive"))
    )
    (net (code "28") (name "CELL21") (class "Default")
      (node (ref "CELLS-21-30") (pin "1") (pinfunction "S_1") (pintype "passive"))
      (node (ref "L42") (pin "1") (pinfunction "1_1") (pintype "passive"))
    )
    (net (code "29") (name "CELL22") (class "Default")
      (node (ref "CELLS-21-30") (pin "2") (pinfunction "S_2") (pintype "passive"))
      (node (ref "L41") (pin "1") (pinfunction "1_1") (pintype "passive"))
    )
    (net (code "30") (name "CELL23") (class "Default")
      (node (ref "CELLS-21-30") (pin "3") (pinfunction "S_3") (pintype "passive"))
      (node (ref "L40") (pin "1") (pinfunction "1_1") (pintype "passive"))
    )
    (net (code "31") (name "CELL24") (class "Default")
      (node (ref "CELLS-21-30") (pin "4") (pinfunction "S_4") (pintype "passive"))
      (node (ref "L39") (pin "1") (pinfunction "1_1") (pintype "passive"))
    )
    (net (code "32") (name "CELL25") (class "Default")
      (node (ref "CELLS-21-30") (pin "5") (pinfunction "S_5") (pintype "passive"))
      (node (ref "L38") (pin "1") (pinfunction "1_1") (pintype "passive"))
    )
    (net (code "33") (name "CELL26") (class "Default")
      (node (ref "CELLS-21-30") (pin "6") (pinfunction "S_6") (pintype "passive"))
      (node (ref "L37") (pin "1") (pinfunction "1_1") (pintype "passive"))
    )
    (net (code "34") (name "CELL27") (class "Default")
      (node (ref "CELLS-21-30") (pin "7") (pinfunction "S_7") (pintype "passive"))
      (node (ref "L36") (pin "1") (pinfunction "1_1") (pintype "passive"))
    )
    (net (code "35") (name "CELL28") (class "Default")
      (node (ref "CELLS-21-30") (pin "8") (pinfunction "S_8") (pintype "passive"))
      (node (ref "L35") (pin "1") (pinfunction "1_1") (pintype "passive"))
    )
    (net (code "36") (name "CELL29") (class "Default")
      (node (ref "CELLS-21-30") (pin "9") (pinfunction "S_9") (pintype "passive"))
      (node (ref "L34") (pin "1") (pinfunction "1_1") (pintype "passive"))
    )
    (net (code "37") (name "CELL30") (class "Default")
      (node (ref "CELLS-21-30") (pin "10") (pinfunction "S_10") (pintype "passive"))
      (node (ref "L33") (pin "1") (pinfunction "1_1") (pintype "passive"))
      (node (ref "L43") (pin "1") (pinfunction "1_1") (pintype "passive"))
    )
    (net (code "38") (name "CRITICAL") (class "Default")
      (node (ref "R156") (pin "2") (pinfunction "2_2") (pintype "passive"))
      (node (ref "U$2") (pin "10") (pinfunction "RA3_10") (pintype "bidirectional"))
      (node (ref "U$20") (pin "P$1") (pinfunction "TP_P$1") (pintype "input"))
    )
    (net (code "39") (name "DI-RO") (class "Default")
      (node (ref "U$2") (pin "12") (pinfunction "RA4_12") (pintype "bidirectional"))
      (node (ref "U$22") (pin "P$1") (pinfunction "TP_P$1") (pintype "input"))
      (node (ref "U$5") (pin "8") (pinfunction "2_8") (pintype "passive"))
    )
    (net (code "40") (name "FAULT") (class "Default")
      (node (ref "U$2") (pin "22") (pinfunction "RB11_22") (pintype "bidirectional"))
      (node (ref "U$29") (pin "P$1") (pinfunction "TP_P$1") (pintype "input"))
      (node (ref "U$5") (pin "2") (pinfunction "2_2") (pintype "passive"))
    )
    (net (code "41") (name "GND") (class "Default")
      (node (ref "C10") (pin "2") (pinfunction "2_2") (pintype "passive"))
      (node (ref "C11") (pin "2") (pinfunction "2_2") (pintype "passive"))
      (node (ref "C12") (pin "2") (pinfunction "2_2") (pintype "passive"))
      (node (ref "C13") (pin "2") (pinfunction "2_2") (pintype "passive"))
      (node (ref "C14") (pin "2") (pinfunction "2_2") (pintype "passive"))
      (node (ref "C15") (pin "2") (pinfunction "2_2") (pintype "passive"))
      (node (ref "C2") (pin "2") (pinfunction "2_2") (pintype "passive"))
      (node (ref "C4") (pin "2") (pinfunction "2_2") (pintype "passive"))
      (node (ref "C5") (pin "2") (pinfunction "2_2") (pintype "passive"))
      (node (ref "C6") (pin "2") (pinfunction "2_2") (pintype "passive"))
      (node (ref "C7") (pin "2") (pinfunction "2_2") (pintype "passive"))
      (node (ref "C8") (pin "2") (pinfunction "2_2") (pintype "passive"))
      (node (ref "C9") (pin "2") (pinfunction "2_2") (pintype "passive"))
      (node (ref "D16") (pin "A") (pinfunction "A_A") (pintype "passive"))
      (node (ref "D17") (pin "A") (pinfunction "A_A") (pintype "passive"))
      (node (ref "D18") (pin "A") (pinfunction "A_A") (pintype "passive"))
      (node (ref "IC1") (pin "15") (pinfunction "GND2_15") (pintype "power_in"))
      (node (ref "IC1") (pin "9") (pinfunction "GND2_9") (pintype "power_in"))
      (node (ref "L16") (pin "2") (pinfunction "2_2") (pintype "passive"))
      (node (ref "LTC1") (pin "P$27") (pinfunction "V-_P$27") (pintype "bidirectional"))
      (node (ref "LTC1") (pin "P$28") (pinfunction "NC_P$28") (pintype "bidirectional"))
      (node (ref "LTC1") (pin "P$29") (pinfunction "V_TEMP1_P$29") (pintype "bidirectional"))
      (node (ref "LTC1") (pin "P$30") (pinfunction "V_TEMP2_P$30") (pintype "bidirectional"))
      (node (ref "LTC1") (pin "P$35") (pinfunction "GPIO1_P$35") (pintype "bidirectional"))
      (node (ref "LTC1") (pin "P$36") (pinfunction "GPIO2_P$36") (pintype "bidirectional"))
      (node (ref "U$8") (pin "1") (pinfunction "1_1") (pintype "passive"))
      (node (ref "U$8") (pin "10") (pinfunction "1_10") (pintype "passive"))
      (node (ref "U$8") (pin "13") (pinfunction "1_13") (pintype "passive"))
      (node (ref "U$8") (pin "16") (pinfunction "1_16") (pintype "passive"))
      (node (ref "U$8") (pin "4") (pinfunction "1_4") (pintype "passive"))
      (node (ref "U$8") (pin "7") (pinfunction "1_7") (pintype "passive"))
      (node (ref "V-1") (pin "TP") (pinfunction "TP_TP") (pintype "input"))
    )
    (net (code "42") (name "GNDIO") (class "Default")
      (node (ref "12V") (pin "1") (pinfunction "S_1") (pintype "passive"))
      (node (ref "AIN0") (pin "1") (pinfunction "S_1") (pintype "passive"))
      (node (ref "AIN1") (pin "1") (pinfunction "S_1") (pintype "passive"))
      (node (ref "AIN2") (pin "1") (pinfunction "S_1") (pintype "passive"))
      (node (ref "AIN3") (pin "1") (pinfunction "S_1") (pintype "passive"))
      (node (ref "AIN4") (pin "1") (pinfunction "S_1") (pintype "passive"))
      (node (ref "C1") (pin "2") (pinfunction "2_2") (pintype "passive"))
      (node (ref "C16") (pin "2") (pinfunction "2_2") (pintype "passive"))
      (node (ref "C22") (pin "2") (pinfunction "2_2") (pintype "passive"))
      (node (ref "C48") (pin "2") (pinfunction "2_2") (pintype "passive"))
      (node (ref "C49") (pin "2") (pinfunction "2_2") (pintype "passive"))
      (node (ref "C50") (pin "2") (pinfunction "2_2") (pintype "passive"))
      (node (ref "C51") (pin "2") (pinfunction "2_2") (pintype "passive"))
      (node (ref "C52") (pin "2") (pinfunction "2_2") (pintype "passive"))
      (node (ref "C53") (pin "2") (pinfunction "2_2") (pintype "passive"))
      (node (ref "C54") (pin "2") (pinfunction "2_2") (pintype "passive"))
      (node (ref "IC1") (pin "2") (pinfunction "GND1_2") (pintype "power_in"))
      (node (ref "IC1") (pin "8") (pinfunction "GND1_8") (pintype "power_in"))
      (node (ref "IC2") (pin "3") (pinfunction "GND_3") (pintype "passive"))
      (node (ref "IC2_\\") (pin "2") (pinfunction "GND1_2") (pintype "power_in"))
      (node (ref "IC2_\\") (pin "8") (pinfunction "GND1_8") (pintype "power_in"))
      (node (ref "IC3") (pin "1") (pinfunction "GND_1") (pintype "power_in"))
      (node (ref "IC3_") (pin "2") (pinfunction "GND1_2") (pintype "power_in"))
      (node (ref "IC3_") (pin "8") (pinfunction "GND1_8") (pintype "power_in"))
      (node (ref "LED37") (pin "C") (pinfunction "C_C") (pintype "passive"))
      (node (ref "LED38") (pin "C") (pinfunction "C_C") (pintype "passive"))
      (node (ref "LED40") (pin "C") (pinfunction "C_C") (pintype "passive"))
      (node (ref "PROGRAM") (pin "6") (pinfunction "S_6") (pintype "passive"))
      (node (ref "R2") (pin "1") (pinfunction "1_1") (pintype "passive"))
      (node (ref "S2") (pin "1") (pinfunction "S_1") (pintype "passive"))
      (node (ref "S2") (pin "2") (pinfunction "S1_2") (pintype "passive"))
      (node (ref "T1") (pin "2") (pinfunction "S_2") (pintype "passive"))
      (node (ref "U$1") (pin "8") (pinfunction "V-_8") (pintype "bidirectional"))
      (node (ref "U$2") (pin "19") (pinfunction "VSS_19") (pintype "bidirectional"))
      (node (ref "U$2") (pin "27") (pinfunction "AVSS_27") (pintype "bidirectional"))
      (node (ref "U$2") (pin "8") (pinfunction "VSS_8") (pintype "bidirectional"))
      (node (ref "U$3") (pin "2") (pinfunction "GND_2") (pintype "power_in"))
      (node (ref "U$4") (pin "5") (pinfunction "GND_5") (pintype "bidirectional"))
      (node (ref "U$6") (pin "14") (pinfunction "AGND_14") (pintype "bidirectional"))
      (node (ref "U$6") (pin "9") (pinfunction "DGND_9") (pintype "bidirectional"))
      (node (ref "U$7") (pin "3") (pinfunction "GND_3") (pintype "bidirectional"))
    )
    (net (code "43") (name "JACK2") (class "Default")
      (node (ref "J19") (pin "2") (pinfunction "2_2") (pintype "passive"))
      (node (ref "J20") (pin "2") (pinfunction "2_2") (pintype "passive"))
      (node (ref "U$5") (pin "1") (pinfunction "1_1") (pintype "passive"))
    )
    (net (code "44") (name "JACK3") (class "Default")
      (node (ref "J19") (pin "3") (pinfunction "3_3") (pintype "passive"))
      (node (ref "J20") (pin "3") (pinfunction "3_3") (pintype "passive"))
      (node (ref "R170") (pin "1") (pinfunction "1_1") (pintype "passive"))
      (node (ref "U$4") (pin "6") (pinfunction "A_6") (pintype "bidirectional"))
      (node (ref "U$5") (pin "4") (pinfunction "1_4") (pintype "passive"))
    )
    (net (code "45") (name "JACK4") (class "Default")
      (node (ref "J19") (pin "4") (pinfunction "4_4") (pintype "passive"))
      (node (ref "J20") (pin "4") (pinfunction "4_4") (pintype "passive"))
      (node (ref "R170") (pin "2") (pinfunction "2_2") (pintype "passive"))
      (node (ref "U$4") (pin "7") (pinfunction "B_7") (pintype "bidirectional"))
      (node (ref "U$5") (pin "7") (pinfunction "1_7") (pintype "passive"))
    )
    (net (code "46") (name "JACK5") (class "Default")
      (node (ref "J19") (pin "5") (pinfunction "5_5") (pintype "passive"))
      (node (ref "J20") (pin "5") (pinfunction "5_5") (pintype "passive"))
      (node (ref "U$5") (pin "10") (pinfunction "1_10") (pintype "passive"))
    )
    (net (code "47") (name "LED2") (class "Default")
      (node (ref "R158") (pin "2") (pinfunction "2_2") (pintype "passive"))
      (node (ref "SV1") (pin "3") (pinfunction "3_3") (pintype "passive"))
    )
    (net (code "48") (name "LTC_1_CS") (class "Default")
      (node (ref "CS1_O") (pin "TP") (pinfunction "TP_TP") (pintype "input"))
      (node (ref "IC1") (pin "5") (pinfunction "VIC_5") (pintype "input"))
      (node (ref "U$2") (pin "23") (pinfunction "RB12_23") (pintype "bidirectional"))
      (node (ref "U$30") (pin "P$1") (pinfunction "TP_P$1") (pintype "input"))
    )
    (net (code "49") (name "LTC_1_MISO") (class "Default")
      (node (ref "IC1") (pin "6") (pinfunction "VOD_6") (pintype "output"))
      (node (ref "MISO1_O") (pin "TP") (pinfunction "TP_TP") (pintype "input"))
      (node (ref "U$2") (pin "14") (pinfunction "RB5_14") (pintype "bidirectional"))
      (node (ref "U$23") (pin "P$1") (pinfunction "TP_P$1") (pintype "input"))
    )
    (net (code "50") (name "LTC_2_CS") (class "Default")
      (node (ref "CS2_O") (pin "TP") (pinfunction "TP_TP") (pintype "input"))
      (node (ref "IC2_\\") (pin "5") (pinfunction "VIC_5") (pintype "input"))
      (node (ref "U$2") (pin "24") (pinfunction "RB13_24") (pintype "bidirectional"))
      (node (ref "U$31") (pin "P$1") (pinfunction "TP_P$1") (pintype "input"))
    )
    (net (code "51") (name "LTC_2_MISO") (class "Default")
      (node (ref "IC2_\\") (pin "6") (pinfunction "VOD_6") (pintype "output"))
      (node (ref "MISO2_O") (pin "TP") (pinfunction "TP_TP") (pintype "input"))
      (node (ref "U$2") (pin "15") (pinfunction "RB6_15") (pintype "bidirectional"))
      (node (ref "U$24") (pin "P$1") (pinfunction "TP_P$1") (pintype "input"))
    )
    (net (code "52") (name "LTC_3_CS") (class "Default")
      (node (ref "CS3_O") (pin "TP") (pinfunction "TP_TP") (pintype "input"))
      (node (ref "IC3_") (pin "5") (pinfunction "VIC_5") (pintype "input"))
      (node (ref "U$2") (pin "25") (pinfunction "RB14_25") (pintype "bidirectional"))
      (node (ref "U$32") (pin "P$1") (pinfunction "TP_P$1") (pintype "input"))
    )
    (net (code "53") (name "LTC_3_MISO") (class "Default")
      (node (ref "IC3_") (pin "6") (pinfunction "VOD_6") (pintype "output"))
      (node (ref "MISO3_O") (pin "TP") (pinfunction "TP_TP") (pintype "input"))
      (node (ref "U$2") (pin "16") (pinfunction "RB7_16") (pintype "bidirectional"))
      (node (ref "U$25") (pin "P$1") (pinfunction "TP_P$1") (pintype "input"))
    )
    (net (code "54") (name "MCLR") (class "Default")
      (node (ref "C1") (pin "1") (pinfunction "1_1") (pintype "passive"))
      (node (ref "PROGRAM") (pin "4") (pinfunction "S_4") (pintype "passive"))
      (node (ref "R52") (pin "2") (pinfunction "2_2") (pintype "passive"))
      (node (ref "R53") (pin "1") (pinfunction "1_1") (pintype "passive"))
    )
    (net (code "55") (name "MOSI") (class "Default")
      (node (ref "IC1") (pin "4") (pinfunction "VIB_4") (pintype "input"))
      (node (ref "IC2_\\") (pin "4") (pinfunction "VIB_4") (pintype "input"))
      (node (ref "IC3_") (pin "4") (pinfunction "VIB_4") (pintype "input"))
      (node (ref "MOSI1_O") (pin "TP") (pinfunction "TP_TP") (pintype "input"))
      (node (ref "MOSI2_O") (pin "TP") (pinfunction "TP_TP") (pintype "input"))
      (node (ref "MOSI3_O") (pin "TP") (pinfunction "TP_TP") (pintype "input"))
      (node (ref "U$18") (pin "P$1") (pinfunction "TP_P$1") (pintype "input"))
      (node (ref "U$2") (pin "6") (pinfunction "RB2_6") (pintype "bidirectional"))
      (node (ref "U$6") (pin "11") (pinfunction "DIN_11") (pintype "bidirectional"))
    )
    (net (code "56") (name "Net-(AIN0C-S)") (class "Default")
      (node (ref "AIN0") (pin "3") (pinfunction "S_3") (pintype "passive"))
      (node (ref "U$1") (pin "1") (pinfunction "IN1_1") (pintype "bidirectional"))
      (node (ref "U$6") (pin "1") (pinfunction "CH0_1") (pintype "bidirectional"))
    )
    (net (code "57") (name "Net-(AIN1C-S)") (class "Default")
      (node (ref "AIN1") (pin "3") (pinfunction "S_3") (pintype "passive"))
      (node (ref "U$1") (pin "2") (pinfunction "IN2_2") (pintype "bidirectional"))
      (node (ref "U$6") (pin "2") (pinfunction "CH1_2") (pintype "bidirectional"))
    )
    (net (code "58") (name "Net-(AIN2C-S)") (class "Default")
      (node (ref "AIN2") (pin "3") (pinfunction "S_3") (pintype "passive"))
      (node (ref "U$1") (pin "3") (pinfunction "IN3_3") (pintype "bidirectional"))
      (node (ref "U$6") (pin "3") (pinfunction "CH2_3") (pintype "bidirectional"))
    )
    (net (code "59") (name "Net-(AIN3C-S)") (class "Default")
      (node (ref "AIN3") (pin "3") (pinfunction "S_3") (pintype "passive"))
      (node (ref "U$1") (pin "4") (pinfunction "IN4_4") (pintype "bidirectional"))
      (node (ref "U$6") (pin "4") (pinfunction "CH3_4") (pintype "bidirectional"))
    )
    (net (code "60") (name "Net-(AIN4C-S)") (class "Default")
      (node (ref "AIN4") (pin "3") (pinfunction "S_3") (pintype "passive"))
      (node (ref "U$1") (pin "5") (pinfunction "IN5_5") (pintype "bidirectional"))
      (node (ref "U$6") (pin "5") (pinfunction "CH4_5") (pintype "bidirectional"))
    )
    (net (code "61") (name "Net-(CONTACTORA-S)") (class "Default")
      (node (ref "CONTACTOR") (pin "1") (pinfunction "S_1") (pintype "passive"))
      (node (ref "K1") (pin "S") (pinfunction "S_S") (pintype "passive"))
      (node (ref "K1") (pin "S@") (pinfunction "S_S@") (pintype "passive"))
    )
    (net (code "62") (name "Net-(CONTACTORB-S)") (class "Default")
      (node (ref "CONTACTOR") (pin "2") (pinfunction "S_2") (pintype "passive"))
      (node (ref "K1") (pin "P") (pinfunction "P_P") (pintype "passive"))
      (node (ref "K1") (pin "P@") (pinfunction "P_P@") (pintype "passive"))
    )
    (net (code "63") (name "Net-(D16-PadC)") (class "Default")
      (node (ref "D16") (pin "C") (pinfunction "C_C") (pintype "passive"))
      (node (ref "D17") (pin "C") (pinfunction "C_C") (pintype "passive"))
      (node (ref "D18") (pin "C") (pinfunction "C_C") (pintype "passive"))
      (node (ref "L15") (pin "2") (pinfunction "2_2") (pintype "passive"))
      (node (ref "R50") (pin "1") (pinfunction "1_1") (pintype "passive"))
    )
    (net (code "64") (name "Net-(D28-PadC)") (class "Default")
      (node (ref "D28") (pin "C") (pinfunction "C_C") (pintype "passive"))
      (node (ref "D29") (pin "C") (pinfunction "C_C") (pintype "passive"))
      (node (ref "D30") (pin "C") (pinfunction "C_C") (pintype "passive"))
      (node (ref "L28") (pin "2") (pinfunction "2_2") (pintype "passive"))
      (node (ref "R102") (pin "1") (pinfunction "1_1") (pintype "passive"))
    )
    (net (code "65") (name "Net-(D43-PadC)") (class "Default")
      (node (ref "D43") (pin "C") (pinfunction "C_C") (pintype "passive"))
      (node (ref "D44") (pin "C") (pinfunction "C_C") (pintype "passive"))
      (node (ref "D45") (pin "C") (pinfunction "C_C") (pintype "passive"))
      (node (ref "L43") (pin "2") (pinfunction "2_2") (pintype "passive"))
      (node (ref "R153") (pin "1") (pinfunction "1_1") (pintype "passive"))
    )
    (net (code "66") (name "Net-(IC1-VID)") (class "Default")
      (node (ref "IC1") (pin "11") (pinfunction "VID_11") (pintype "input"))
      (node (ref "LTC1") (pin "P$43") (pinfunction "SDO_P$43") (pintype "bidirectional"))
      (node (ref "R167") (pin "2") (pinfunction "2_2") (pintype "passive"))
      (node (ref "R168") (pin "2") (pinfunction "2_2") (pintype "passive"))
      (node (ref "SDO1") (pin "TP") (pinfunction "TP_TP") (pintype "input"))
    )
    (net (code "67") (name "Net-(IC1-VOA)") (class "Default")
      (node (ref "IC1") (pin "14") (pinfunction "VOA_14") (pintype "output"))
      (node (ref "LTC1") (pin "P$41") (pinfunction "SCKI_P$41") (pintype "bidirectional"))
      (node (ref "SCK1") (pin "TP") (pinfunction "TP_TP") (pintype "input"))
    )
    (net (code "68") (name "Net-(IC1-VOB)") (class "Default")
      (node (ref "IC1") (pin "13") (pinfunction "VOB_13") (pintype "output"))
      (node (ref "LTC1") (pin "P$42") (pinfunction "SDI_P$42") (pintype "bidirectional"))
      (node (ref "SDI1") (pin "TP") (pinfunction "TP_TP") (pintype "input"))
    )
    (net (code "69") (name "Net-(IC1-VOC)") (class "Default")
      (node (ref "CS1") (pin "TP") (pinfunction "TP_TP") (pintype "input"))
      (node (ref "IC1") (pin "12") (pinfunction "VOC_12") (pintype "output"))
      (node (ref "LTC1") (pin "P$44") (pinfunction "CSBI_P$44") (pintype "bidirectional"))
    )
    (net (code "70") (name "Net-(IC2_\\-VID)") (class "Default")
      (node (ref "IC2_\\") (pin "11") (pinfunction "VID_11") (pintype "input"))
      (node (ref "LTC2") (pin "P$43") (pinfunction "SDO_P$43") (pintype "bidirectional"))
      (node (ref "R165") (pin "2") (pinfunction "2_2") (pintype "passive"))
      (node (ref "R166") (pin "2") (pinfunction "2_2") (pintype "passive"))
      (node (ref "SDO2") (pin "TP") (pinfunction "TP_TP") (pintype "input"))
    )
    (net (code "71") (name "Net-(IC2_\\-VOA)") (class "Default")
      (node (ref "IC2_\\") (pin "14") (pinfunction "VOA_14") (pintype "output"))
      (node (ref "LTC2") (pin "P$41") (pinfunction "SCKI_P$41") (pintype "bidirectional"))
      (node (ref "SCK2") (pin "TP") (pinfunction "TP_TP") (pintype "input"))
    )
    (net (code "72") (name "Net-(IC2_\\-VOB)") (class "Default")
      (node (ref "IC2_\\") (pin "13") (pinfunction "VOB_13") (pintype "output"))
      (node (ref "LTC2") (pin "P$42") (pinfunction "SDI_P$42") (pintype "bidirectional"))
      (node (ref "SDI2") (pin "TP") (pinfunction "TP_TP") (pintype "input"))
    )
    (net (code "73") (name "Net-(IC2_\\-VOC)") (class "Default")
      (node (ref "CS2") (pin "TP") (pinfunction "TP_TP") (pintype "input"))
      (node (ref "IC2_\\") (pin "12") (pinfunction "VOC_12") (pintype "output"))
      (node (ref "LTC2") (pin "P$44") (pinfunction "CSBI_P$44") (pintype "bidirectional"))
    )
    (net (code "74") (name "Net-(IC3_-VID)") (class "Default")
      (node (ref "IC3_") (pin "11") (pinfunction "VID_11") (pintype "input"))
      (node (ref "LTC3") (pin "P$43") (pinfunction "SDO_P$43") (pintype "bidirectional"))
      (node (ref "R163") (pin "2") (pinfunction "2_2") (pintype "passive"))
      (node (ref "R164") (pin "2") (pinfunction "2_2") (pintype "passive"))
      (node (ref "SDO3") (pin "TP") (pinfunction "TP_TP") (pintype "input"))
    )
    (net (code "75") (name "Net-(IC3_-VOA)") (class "Default")
      (node (ref "IC3_") (pin "14") (pinfunction "VOA_14") (pintype "output"))
      (node (ref "LTC3") (pin "P$41") (pinfunction "SCKI_P$41") (pintype "bidirectional"))
      (node (ref "SCK3") (pin "TP") (pinfunction "TP_TP") (pintype "input"))
    )
    (net (code "76") (name "Net-(IC3_-VOB)") (class "Default")
      (node (ref "IC3_") (pin "13") (pinfunction "VOB_13") (pintype "output"))
      (node (ref "LTC3") (pin "P$42") (pinfunction "SDI_P$42") (pintype "bidirectional"))
      (node (ref "SDI3") (pin "TP") (pinfunction "TP_TP") (pintype "input"))
    )
    (net (code "77") (name "Net-(IC3_-VOC)") (class "Default")
      (node (ref "CS3") (pin "TP") (pinfunction "TP_TP") (pintype "input"))
      (node (ref "IC3_") (pin "12") (pinfunction "VOC_12") (pintype "output"))
      (node (ref "LTC3") (pin "P$44") (pinfunction "CSBI_P$44") (pintype "bidirectional"))
    )
    (net (code "78") (name "Net-(J19-Pad1)") (class "Default")
      (node (ref "J19") (pin "1") (pinfunction "1_1") (pintype "passive"))
      (node (ref "J20") (pin "1") (pinfunction "1_1") (pintype "passive"))
    )
    (net (code "79") (name "Net-(J19-Pad6)") (class "Default")
      (node (ref "J19") (pin "6") (pinfunction "6_6") (pintype "passive"))
      (node (ref "J20") (pin "6") (pinfunction "6_6") (pintype "passive"))
    )
    (net (code "80") (name "Net-(K1-Pad1)") (class "Default")
      (node (ref "K1") (pin "1") (pinfunction "1_1") (pintype "passive"))
      (node (ref "R169") (pin "1") (pinfunction "1_1") (pintype "passive"))
    )
    (net (code "81") (name "Net-(L17-Pad2)") (class "Default")
      (node (ref "L17") (pin "2") (pinfunction "2_2") (pintype "passive"))
      (node (ref "R48") (pin "1") (pinfunction "1_1") (pintype "passive"))
      (node (ref "R51") (pin "1") (pinfunction "1_1") (pintype "passive"))
    )
    (net (code "82") (name "Net-(L30-Pad2)") (class "Default")
      (node (ref "L30") (pin "2") (pinfunction "2_2") (pintype "passive"))
      (node (ref "R100") (pin "1") (pinfunction "1_1") (pintype "passive"))
      (node (ref "R103") (pin "1") (pinfunction "1_1") (pintype "passive"))
    )
    (net (code "83") (name "Net-(L45-Pad2)") (class "Default")
      (node (ref "L45") (pin "2") (pinfunction "2_2") (pintype "passive"))
      (node (ref "R151") (pin "1") (pinfunction "1_1") (pintype "passive"))
      (node (ref "R154") (pin "1") (pinfunction "1_1") (pintype "passive"))
    )
    (net (code "84") (name "Net-(LED37-PadA)") (class "Default")
      (node (ref "LED37") (pin "A") (pinfunction "A_A") (pintype "passive"))
      (node (ref "R157") (pin "1") (pinfunction "1_1") (pintype "passive"))
    )
    (net (code "85") (name "Net-(LED38-PadA)") (class "Default")
      (node (ref "LED38") (pin "A") (pinfunction "A_A") (pintype "passive"))
      (node (ref "R156") (pin "1") (pinfunction "1_1") (pintype "passive"))
    )
    (net (code "86") (name "Net-(LED40-PadA)") (class "Default")
      (node (ref "LED40") (pin "A") (pinfunction "A_A") (pintype "passive"))
      (node (ref "R158") (pin "1") (pinfunction "1_1") (pintype "passive"))
    )
    (net (code "87") (name "Net-(LTC1-A0)") (class "Default")
      (node (ref "LTC1") (pin "P$37") (pinfunction "A0_P$37") (pintype "bidirectional"))
      (node (ref "U$8") (pin "8") (pinfunction "2_8") (pintype "passive"))
    )
    (net (code "88") (name "Net-(LTC1-A1)") (class "Default")
      (node (ref "LTC1") (pin "P$38") (pinfunction "A1_P$38") (pintype "bidirectional"))
      (node (ref "U$8") (pin "11") (pinfunction "2_11") (pintype "passive"))
    )
    (net (code "89") (name "Net-(LTC1-A2)") (class "Default")
      (node (ref "LTC1") (pin "P$39") (pinfunction "A2_P$39") (pintype "bidirectional"))
      (node (ref "U$8") (pin "14") (pinfunction "2_14") (pintype "passive"))
    )
    (net (code "90") (name "Net-(LTC1-A3)") (class "Default")
      (node (ref "LTC1") (pin "P$40") (pinfunction "A3_P$40") (pintype "bidirectional"))
      (node (ref "U$8") (pin "17") (pinfunction "2_17") (pintype "passive"))
    )
    (net (code "91") (name "Net-(LTC1-C0)") (class "Default")
      (node (ref "D15") (pin "A") (pinfunction "A_A") (pintype "passive"))
      (node (ref "LTC1") (pin "P$26") (pinfunction "C0_P$26") (pintype "bidirectional"))
      (node (ref "LTC1_C0") (pin "P$1") (pinfunction "TP_P$1") (pintype "input"))
      (node (ref "R51") (pin "2") (pinfunction "2_2") (pintype "passive"))
    )
    (net (code "92") (name "Net-(LTC1-C1)") (class "Default")
      (node (ref "C13") (pin "1") (pinfunction "1_1") (pintype "passive"))
      (node (ref "D14") (pin "A") (pinfunction "A_A") (pintype "passive"))
      (node (ref "D15") (pin "C") (pinfunction "C_C") (pintype "passive"))
      (node (ref "LTC1") (pin "P$24") (pinfunction "C1_P$24") (pintype "bidirectional"))
      (node (ref "LTC1_C1") (pin "P$1") (pinfunction "TP_P$1") (pintype "input"))
      (node (ref "R46") (pin "2") (pinfunction "2_2") (pintype "passive"))
    )
    (net (code "93") (name "Net-(LTC1-C2)") (class "Default")
      (node (ref "C12") (pin "1") (pinfunction "1_1") (pintype "passive"))
      (node (ref "D13") (pin "A") (pinfunction "A_A") (pintype "passive"))
      (node (ref "D14") (pin "C") (pinfunction "C_C") (pintype "passive"))
      (node (ref "LTC1") (pin "P$22") (pinfunction "C2_P$22") (pintype "bidirectional"))
      (node (ref "LTC1_C2") (pin "P$1") (pinfunction "TP_P$1") (pintype "input"))
      (node (ref "R42") (pin "2") (pinfunction "2_2") (pintype "passive"))
    )
    (net (code "94") (name "Net-(LTC1-C3)") (class "Default")
      (node (ref "C11") (pin "1") (pinfunction "1_1") (pintype "passive"))
      (node (ref "D12") (pin "A") (pinfunction "A_A") (pintype "passive"))
      (node (ref "D13") (pin "C") (pinfunction "C_C") (pintype "passive"))
      (node (ref "LTC1") (pin "P$20") (pinfunction "C3_P$20") (pintype "bidirectional"))
      (node (ref "LTC1_C3") (pin "P$1") (pinfunction "TP_P$1") (pintype "input"))
      (node (ref "R38") (pin "2") (pinfunction "2_2") (pintype "passive"))
    )
    (net (code "95") (name "Net-(LTC1-C4)") (class "Default")
      (node (ref "C10") (pin "1") (pinfunction "1_1") (pintype "passive"))
      (node (ref "D11") (pin "A") (pinfunction "A_A") (pintype "passive"))
      (node (ref "D12") (pin "C") (pinfunction "C_C") (pintype "passive"))
      (node (ref "LTC1") (pin "P$18") (pinfunction "C4_P$18") (pintype "bidirectional"))
      (node (ref "LTC1_C4") (pin "P$1") (pinfunction "TP_P$1") (pintype "input"))
      (node (ref "R34") (pin "2") (pinfunction "2_2") (pintype "passive"))
    )
    (net (code "96") (name "Net-(LTC1-C5)") (class "Default")
      (node (ref "C9") (pin "1") (pinfunction "1_1") (pintype "passive"))
      (node (ref "D10") (pin "A") (pinfunction "A_A") (pintype "passive"))
      (node (ref "D11") (pin "C") (pinfunction "C_C") (pintype "passive"))
      (node (ref "LTC1") (pin "P$16") (pinfunction "C5_P$16") (pintype "bidirectional"))
      (node (ref "LTC1_C5") (pin "P$1") (pinfunction "TP_P$1") (pintype "input"))
      (node (ref "R30") (pin "2") (pinfunction "2_2") (pintype "passive"))
    )
    (net (code "97") (name "Net-(LTC1-C6)") (class "Default")
      (node (ref "C8") (pin "1") (pinfunction "1_1") (pintype "passive"))
      (node (ref "D10") (pin "C") (pinfunction "C_C") (pintype "passive"))
      (node (ref "D9") (pin "A") (pinfunction "A_A") (pintype "passive"))
      (node (ref "LTC1") (pin "P$14") (pinfunction "C6_P$14") (pintype "bidirectional"))
      (node (ref "LTC1_C6") (pin "P$1") (pinfunction "TP_P$1") (pintype "input"))
      (node (ref "R26") (pin "2") (pinfunction "2_2") (pintype "passive"))
    )
    (net (code "98") (name "Net-(LTC1-C7)") (class "Default")
      (node (ref "C7") (pin "1") (pinfunction "1_1") (pintype "passive"))
      (node (ref "D8") (pin "A") (pinfunction "A_A") (pintype "passive"))
      (node (ref "D9") (pin "C") (pinfunction "C_C") (pintype "passive"))
      (node (ref "LTC1") (pin "P$12") (pinfunction "C7_P$12") (pintype "bidirectional"))
      (node (ref "LTC1_C7") (pin "P$1") (pinfunction "TP_P$1") (pintype "input"))
      (node (ref "R22") (pin "2") (pinfunction "2_2") (pintype "passive"))
    )
    (net (code "99") (name "Net-(LTC1-C8)") (class "Default")
      (node (ref "C6") (pin "1") (pinfunction "1_1") (pintype "passive"))
      (node (ref "D7") (pin "A") (pinfunction "A_A") (pintype "passive"))
      (node (ref "D8") (pin "C") (pinfunction "C_C") (pintype "passive"))
      (node (ref "LTC1") (pin "P$10") (pinfunction "C8_P$10") (pintype "bidirectional"))
      (node (ref "LTC1_C8") (pin "P$1") (pinfunction "TP_P$1") (pintype "input"))
      (node (ref "R18") (pin "2") (pinfunction "2_2") (pintype "passive"))
    )
    (net (code "100") (name "Net-(LTC1-C9)") (class "Default")
      (node (ref "C5") (pin "1") (pinfunction "1_1") (pintype "passive"))
      (node (ref "D6") (pin "A") (pinfunction "A_A") (pintype "passive"))
      (node (ref "D7") (pin "C") (pinfunction "C_C") (pintype "passive"))
      (node (ref "LTC1") (pin "P$8") (pinfunction "C9_P$8") (pintype "bidirectional"))
      (node (ref "LTC1_C9") (pin "P$1") (pinfunction "TP_P$1") (pintype "input"))
      (node (ref "R14") (pin "2") (pinfunction "2_2") (pintype "passive"))
    )
    (net (code "101") (name "Net-(LTC1-C10)") (class "Default")
      (node (ref "C4") (pin "1") (pinfunction "1_1") (pintype "passive"))
      (node (ref "D6") (pin "C") (pinfunction "C_C") (pintype "passive"))
      (node (ref "LTC1") (pin "P$2") (pinfunction "C12_P$2") (pintype "bidirectional"))
      (node (ref "LTC1") (pin "P$4") (pinfunction "C11_P$4") (pintype "bidirectional"))
      (node (ref "LTC1") (pin "P$6") (pinfunction "C10_P$6") (pintype "bidirectional"))
      (node (ref "LTC1_C10") (pin "P$1") (pinfunction "TP_P$1") (pintype "input"))
      (node (ref "R10") (pin "2") (pinfunction "2_2") (pintype "passive"))
    )
    (net (code "102") (name "Net-(LTC1-S1)") (class "Default")
      (node (ref "LTC1") (pin "P$25") (pinfunction "S1_P$25") (pintype "bidirectional"))
      (node (ref "LTC1_S1") (pin "P$1") (pinfunction "TP_P$1") (pintype "input"))
      (node (ref "R47") (pin "2") (pinfunction "2_2") (pintype "passive"))
    )
    (net (code "103") (name "Net-(LTC1-S2)") (class "Default")
      (node (ref "LTC1") (pin "P$23") (pinfunction "S2_P$23") (pintype "bidirectional"))
      (node (ref "LTC1_S2") (pin "P$1") (pinfunction "TP_P$1") (pintype "input"))
      (node (ref "R43") (pin "2") (pinfunction "2_2") (pintype "passive"))
    )
    (net (code "104") (name "Net-(LTC1-S3)") (class "Default")
      (node (ref "LTC1") (pin "P$21") (pinfunction "S3_P$21") (pintype "bidirectional"))
      (node (ref "LTC1_S3") (pin "P$1") (pinfunction "TP_P$1") (pintype "input"))
      (node (ref "R39") (pin "2") (pinfunction "2_2") (pintype "passive"))
    )
    (net (code "105") (name "Net-(LTC1-S4)") (class "Default")
      (node (ref "LTC1") (pin "P$19") (pinfunction "S4_P$19") (pintype "bidirectional"))
      (node (ref "LTC1_S4") (pin "P$1") (pinfunction "TP_P$1") (pintype "input"))
      (node (ref "R35") (pin "2") (pinfunction "2_2") (pintype "passive"))
    )
    (net (code "106") (name "Net-(LTC1-S5)") (class "Default")
      (node (ref "LTC1") (pin "P$17") (pinfunction "S5_P$17") (pintype "bidirectional"))
      (node (ref "LTC1_S5") (pin "P$1") (pinfunction "TP_P$1") (pintype "input"))
      (node (ref "R31") (pin "2") (pinfunction "2_2") (pintype "passive"))
    )
    (net (code "107") (name "Net-(LTC1-S6)") (class "Default")
      (node (ref "LTC1") (pin "P$15") (pinfunction "S6_P$15") (pintype "bidirectional"))
      (node (ref "LTC1_S6") (pin "P$1") (pinfunction "TP_P$1") (pintype "input"))
      (node (ref "R27") (pin "2") (pinfunction "2_2") (pintype "passive"))
    )
    (net (code "108") (name "Net-(LTC1-S7)") (class "Default")
      (node (ref "LTC1") (pin "P$13") (pinfunction "S7_P$13") (pintype "bidirectional"))
      (node (ref "LTC1_S7") (pin "P$1") (pinfunction "TP_P$1") (pintype "input"))
      (node (ref "R23") (pin "2") (pinfunction "2_2") (pintype "passive"))
    )
    (net (code "109") (name "Net-(LTC1-S8)") (class "Default")
      (node (ref "LTC1") (pin "P$11") (pinfunction "S8_P$11") (pintype "bidirectional"))
      (node (ref "LTC1_S8") (pin "P$1") (pinfunction "TP_P$1") (pintype "input"))
      (node (ref "R19") (pin "2") (pinfunction "2_2") (pintype "passive"))
    )
    (net (code "110") (name "Net-(LTC1-S9)") (class "Default")
      (node (ref "LTC1") (pin "P$9") (pinfunction "S9_P$9") (pintype "bidirectional"))
      (node (ref "LTC1_S9") (pin "P$1") (pinfunction "TP_P$1") (pintype "input"))
      (node (ref "R15") (pin "2") (pinfunction "2_2") (pintype "passive"))
    )
    (net (code "111") (name "Net-(LTC1-S10)") (class "Default")
      (node (ref "LTC1") (pin "P$7") (pinfunction "S10_P$7") (pintype "bidirectional"))
      (node (ref "LTC1_S10") (pin "P$1") (pinfunction "TP_P$1") (pintype "input"))
      (node (ref "R11") (pin "2") (pinfunction "2_2") (pintype "passive"))
    )
    (net (code "112") (name "Net-(LTC1-TOS)") (class "Default")
      (node (ref "LTC1") (pin "P$33") (pinfunction "TOS_P$33") (pintype "bidirectional"))
      (node (ref "R5") (pin "1") (pinfunction "1_1") (pintype "passive"))
    )
    (net (code "113") (name "Net-(LTC1-V+)") (class "Default")
      (node (ref "C14") (pin "1") (pinfunction "1_1") (pintype "passive"))
      (node (ref "LTC1") (pin "P$1") (pinfunction "V+_P$1") (pintype "bidirectional"))
      (node (ref "R50") (pin "2") (pinfunction "2_2") (pintype "passive"))
      (node (ref "V+1") (pin "TP") (pinfunction "TP_TP") (pintype "input"))
    )
    (net (code "114") (name "Net-(LTC1-VREF)") (class "Default")
      (node (ref "C15") (pin "1") (pinfunction "1_1") (pintype "passive"))
      (node (ref "LTC1") (pin "P$31") (pinfunction "VREF_P$31") (pintype "bidirectional"))
    )
    (net (code "115") (name "Net-(LTC1-WDTB)") (class "Default")
      (node (ref "LTC1") (pin "P$34") (pinfunction "WDTB_P$34") (pintype "bidirectional"))
      (node (ref "U$8") (pin "2") (pinfunction "2_2") (pintype "passive"))
    )
    (net (code "116") (name "Net-(LTC2-A0)") (class "Default")
      (node (ref "LTC2") (pin "P$37") (pinfunction "A0_P$37") (pintype "bidirectional"))
      (node (ref "U$9") (pin "8") (pinfunction "2_8") (pintype "passive"))
    )
    (net (code "117") (name "Net-(LTC2-A1)") (class "Default")
      (node (ref "LTC2") (pin "P$38") (pinfunction "A1_P$38") (pintype "bidirectional"))
      (node (ref "U$9") (pin "11") (pinfunction "2_11") (pintype "passive"))
    )
    (net (code "118") (name "Net-(LTC2-A2)") (class "Default")
      (node (ref "LTC2") (pin "P$39") (pinfunction "A2_P$39") (pintype "bidirectional"))
      (node (ref "U$9") (pin "14") (pinfunction "2_14") (pintype "passive"))
    )
    (net (code "119") (name "Net-(LTC2-A3)") (class "Default")
      (node (ref "LTC2") (pin "P$40") (pinfunction "A3_P$40") (pintype "bidirectional"))
      (node (ref "U$9") (pin "17") (pinfunction "2_17") (pintype "passive"))
    )
    (net (code "120") (name "Net-(LTC2-C0)") (class "Default")
      (node (ref "D27") (pin "A") (pinfunction "A_A") (pintype "passive"))
      (node (ref "LTC2") (pin "P$26") (pinfunction "C0_P$26") (pintype "bidirectional"))
      (node (ref "LTC2_C0") (pin "P$1") (pinfunction "TP_P$1") (pintype "input"))
      (node (ref "R103") (pin "2") (pinfunction "2_2") (pintype "passive"))
    )
    (net (code "121") (name "Net-(LTC2-C1)") (class "Default")
      (node (ref "C29") (pin "1") (pinfunction "1_1") (pintype "passive"))
      (node (ref "D26") (pin "A") (pinfunction "A_A") (pintype "passive"))
      (node (ref "D27") (pin "C") (pinfunction "C_C") (pintype "passive"))
      (node (ref "LTC2") (pin "P$24") (pinfunction "C1_P$24") (pintype "bidirectional"))
      (node (ref "LTC2_C1") (pin "P$1") (pinfunction "TP_P$1") (pintype "input"))
      (node (ref "R98") (pin "2") (pinfunction "2_2") (pintype "passive"))
    )
    (net (code "122") (name "Net-(LTC2-C2)") (class "Default")
      (node (ref "C28") (pin "1") (pinfunction "1_1") (pintype "passive"))
      (node (ref "D25") (pin "A") (pinfunction "A_A") (pintype "passive"))
      (node (ref "D26") (pin "C") (pinfunction "C_C") (pintype "passive"))
      (node (ref "LTC2") (pin "P$22") (pinfunction "C2_P$22") (pintype "bidirectional"))
      (node (ref "LTC2_C2") (pin "P$1") (pinfunction "TP_P$1") (pintype "input"))
      (node (ref "R94") (pin "2") (pinfunction "2_2") (pintype "passive"))
    )
    (net (code "123") (name "Net-(LTC2-C3)") (class "Default")
      (node (ref "C27") (pin "1") (pinfunction "1_1") (pintype "passive"))
      (node (ref "D24") (pin "A") (pinfunction "A_A") (pintype "passive"))
      (node (ref "D25") (pin "C") (pinfunction "C_C") (pintype "passive"))
      (node (ref "LTC2") (pin "P$20") (pinfunction "C3_P$20") (pintype "bidirectional"))
      (node (ref "LTC2_C3") (pin "P$1") (pinfunction "TP_P$1") (pintype "input"))
      (node (ref "R90") (pin "2") (pinfunction "2_2") (pintype "passive"))
    )
    (net (code "124") (name "Net-(LTC2-C4)") (class "Default")
      (node (ref "C26") (pin "1") (pinfunction "1_1") (pintype "passive"))
      (node (ref "D23") (pin "A") (pinfunction "A_A") (pintype "passive"))
      (node (ref "D24") (pin "C") (pinfunction "C_C") (pintype "passive"))
      (node (ref "LTC2") (pin "P$18") (pinfunction "C4_P$18") (pintype "bidirectional"))
      (node (ref "LTC2_C4") (pin "P$1") (pinfunction "TP_P$1") (pintype "input"))
      (node (ref "R86") (pin "2") (pinfunction "2_2") (pintype "passive"))
    )
    (net (code "125") (name "Net-(LTC2-C5)") (class "Default")
      (node (ref "C25") (pin "1") (pinfunction "1_1") (pintype "passive"))
      (node (ref "D22") (pin "A") (pinfunction "A_A") (pintype "passive"))
      (node (ref "D23") (pin "C") (pinfunction "C_C") (pintype "passive"))
      (node (ref "LTC2") (pin "P$16") (pinfunction "C5_P$16") (pintype "bidirectional"))
      (node (ref "LTC2_C5") (pin "P$1") (pinfunction "TP_P$1") (pintype "input"))
      (node (ref "R82") (pin "2") (pinfunction "2_2") (pintype "passive"))
    )
    (net (code "126") (name "Net-(LTC2-C6)") (class "Default")
      (node (ref "C24") (pin "1") (pinfunction "1_1") (pintype "passive"))
      (node (ref "D21") (pin "A") (pinfunction "A_A") (pintype "passive"))
      (node (ref "D22") (pin "C") (pinfunction "C_C") (pintype "passive"))
      (node (ref "LTC2") (pin "P$14") (pinfunction "C6_P$14") (pintype "bidirectional"))
      (node (ref "LTC2_C6") (pin "P$1") (pinfunction "TP_P$1") (pintype "input"))
      (node (ref "R78") (pin "2") (pinfunction "2_2") (pintype "passive"))
    )
    (net (code "127") (name "Net-(LTC2-C7)") (class "Default")
      (node (ref "C23") (pin "1") (pinfunction "1_1") (pintype "passive"))
      (node (ref "D20") (pin "A") (pinfunction "A_A") (pintype "passive"))
      (node (ref "D21") (pin "C") (pinfunction "C_C") (pintype "passive"))
      (node (ref "LTC2") (pin "P$12") (pinfunction "C7_P$12") (pintype "bidirectional"))
      (node (ref "LTC2_C7") (pin "P$1") (pinfunction "TP_P$1") (pintype "input"))
      (node (ref "R74") (pin "2") (pinfunction "2_2") (pintype "passive"))
    )
    (net (code "128") (name "Net-(LTC2-C8)") (class "Default")
      (node (ref "C21") (pin "1") (pinfunction "1_1") (pintype "passive"))
      (node (ref "D19") (pin "A") (pinfunction "A_A") (pintype "passive"))
      (node (ref "D20") (pin "C") (pinfunction "C_C") (pintype "passive"))
      (node (ref "LTC2") (pin "P$10") (pinfunction "C8_P$10") (pintype "bidirectional"))
      (node (ref "LTC2_C8") (pin "P$1") (pinfunction "TP_P$1") (pintype "input"))
      (node (ref "R70") (pin "2") (pinfunction "2_2") (pintype "passive"))
    )
    (net (code "129") (name "Net-(LTC2-C9)") (class "Default")
      (node (ref "C20") (pin "1") (pinfunction "1_1") (pintype "passive"))
      (node (ref "D19") (pin "C") (pinfunction "C_C") (pintype "passive"))
      (node (ref "D4") (pin "A") (pinfunction "A_A") (pintype "passive"))
      (node (ref "LTC2") (pin "P$8") (pinfunction "C9_P$8") (pintype "bidirectional"))
      (node (ref "LTC2_C9") (pin "P$1") (pinfunction "TP_P$1") (pintype "input"))
      (node (ref "R66") (pin "2") (pinfunction "2_2") (pintype "passive"))
    )
    (net (code "130") (name "Net-(LTC2-C10)") (class "Default")
      (node (ref "C19") (pin "1") (pinfunction "1_1") (pintype "passive"))
      (node (ref "D4") (pin "C") (pinfunction "C_C") (pintype "passive"))
      (node (ref "LTC2") (pin "P$2") (pinfunction "C12_P$2") (pintype "bidirectional"))
      (node (ref "LTC2") (pin "P$4") (pinfunction "C11_P$4") (pintype "bidirectional"))
      (node (ref "LTC2") (pin "P$6") (pinfunction "C10_P$6") (pintype "bidirectional"))
      (node (ref "LTC2_C10") (pin "P$1") (pinfunction "TP_P$1") (pintype "input"))
      (node (ref "R62") (pin "2") (pinfunction "2_2") (pintype "passive"))
    )
    (net (code "131") (name "Net-(LTC2-S1)") (class "Default")
      (node (ref "LTC2") (pin "P$25") (pinfunction "S1_P$25") (pintype "bidirectional"))
      (node (ref "LTC2_S1") (pin "P$1") (pinfunction "TP_P$1") (pintype "input"))
      (node (ref "R99") (pin "2") (pinfunction "2_2") (pintype "passive"))
    )
    (net (code "132") (name "Net-(LTC2-S2)") (class "Default")
      (node (ref "LTC2") (pin "P$23") (pinfunction "S2_P$23") (pintype "bidirectional"))
      (node (ref "LTC2_S2") (pin "P$1") (pinfunction "TP_P$1") (pintype "input"))
      (node (ref "R95") (pin "2") (pinfunction "2_2") (pintype "passive"))
    )
    (net (code "133") (name "Net-(LTC2-S3)") (class "Default")
      (node (ref "LTC2") (pin "P$21") (pinfunction "S3_P$21") (pintype "bidirectional"))
      (node (ref "LTC2_S3") (pin "P$1") (pinfunction "TP_P$1") (pintype "input"))
      (node (ref "R91") (pin "2") (pinfunction "2_2") (pintype "passive"))
    )
    (net (code "134") (name "Net-(LTC2-S4)") (class "Default")
      (node (ref "LTC2") (pin "P$19") (pinfunction "S4_P$19") (pintype "bidirectional"))
      (node (ref "LTC2_S4") (pin "P$1") (pinfunction "TP_P$1") (pintype "input"))
      (node (ref "R87") (pin "2") (pinfunction "2_2") (pintype "passive"))
    )
    (net (code "135") (name "Net-(LTC2-S5)") (class "Default")
      (node (ref "LTC2") (pin "P$17") (pinfunction "S5_P$17") (pintype "bidirectional"))
      (node (ref "LTC2_S5") (pin "P$1") (pinfunction "TP_P$1") (pintype "input"))
      (node (ref "R83") (pin "2") (pinfunction "2_2") (pintype "passive"))
    )
    (net (code "136") (name "Net-(LTC2-S6)") (class "Default")
      (node (ref "LTC2") (pin "P$15") (pinfunction "S6_P$15") (pintype "bidirectional"))
      (node (ref "LTC2_S6") (pin "P$1") (pinfunction "TP_P$1") (pintype "input"))
      (node (ref "R79") (pin "2") (pinfunction "2_2") (pintype "passive"))
    )
    (net (code "137") (name "Net-(LTC2-S7)") (class "Default")
      (node (ref "LTC2") (pin "P$13") (pinfunction "S7_P$13") (pintype "bidirectional"))
      (node (ref "LTC2_S7") (pin "P$1") (pinfunction "TP_P$1") (pintype "input"))
      (node (ref "R75") (pin "2") (pinfunction "2_2") (pintype "passive"))
    )
    (net (code "138") (name "Net-(LTC2-S8)") (class "Default")
      (node (ref "LTC2") (pin "P$11") (pinfunction "S8_P$11") (pintype "bidirectional"))
      (node (ref "LTC2_S8") (pin "P$1") (pinfunction "TP_P$1") (pintype "input"))
      (node (ref "R71") (pin "2") (pinfunction "2_2") (pintype "passive"))
    )
    (net (code "139") (name "Net-(LTC2-S9)") (class "Default")
      (node (ref "LTC2") (pin "P$9") (pinfunction "S9_P$9") (pintype "bidirectional"))
      (node (ref "LTC2_S9") (pin "P$1") (pinfunction "TP_P$1") (pintype "input"))
      (node (ref "R67") (pin "2") (pinfunction "2_2") (pintype "passive"))
    )
    (net (code "140") (name "Net-(LTC2-S10)") (class "Default")
      (node (ref "LTC2") (pin "P$7") (pinfunction "S10_P$7") (pintype "bidirectional"))
      (node (ref "LTC2_S10") (pin "P$1") (pinfunction "TP_P$1") (pintype "input"))
      (node (ref "R63") (pin "2") (pinfunction "2_2") (pintype "passive"))
    )
    (net (code "141") (name "Net-(LTC2-TOS)") (class "Default")
      (node (ref "LTC2") (pin "P$33") (pinfunction "TOS_P$33") (pintype "bidirectional"))
      (node (ref "R104") (pin "1") (pinfunction "1_1") (pintype "passive"))
    )
    (net (code "142") (name "Net-(LTC2-V+)") (class "Default")
      (node (ref "C30") (pin "1") (pinfunction "1_1") (pintype "passive"))
      (node (ref "LTC2") (pin "P$1") (pinfunction "V+_P$1") (pintype "bidirectional"))
      (node (ref "R102") (pin "2") (pinfunction "2_2") (pintype "passive"))
      (node (ref "V+2") (pin "TP") (pinfunction "TP_TP") (pintype "input"))
    )
    (net (code "143") (name "Net-(LTC2-VREF)") (class "Default")
      (node (ref "C32") (pin "1") (pinfunction "1_1") (pintype "passive"))
      (node (ref "LTC2") (pin "P$31") (pinfunction "VREF_P$31") (pintype "bidirectional"))
    )
    (net (code "144") (name "Net-(LTC2-WDTB)") (class "Default")
      (node (ref "LTC2") (pin "P$34") (pinfunction "WDTB_P$34") (pintype "bidirectional"))
      (node (ref "U$9") (pin "2") (pinfunction "2_2") (pintype "passive"))
    )
    (net (code "145") (name "Net-(LTC3-A0)") (class "Default")
      (node (ref "LTC3") (pin "P$37") (pinfunction "A0_P$37") (pintype "bidirectional"))
      (node (ref "U$10") (pin "8") (pinfunction "2_8") (pintype "passive"))
    )
    (net (code "146") (name "Net-(LTC3-A1)") (class "Default")
      (node (ref "LTC3") (pin "P$38") (pinfunction "A1_P$38") (pintype "bidirectional"))
      (node (ref "U$10") (pin "11") (pinfunction "2_11") (pintype "passive"))
    )
    (net (code "147") (name "Net-(LTC3-A2)") (class "Default")
      (node (ref "LTC3") (pin "P$39") (pinfunction "A2_P$39") (pintype "bidirectional"))
      (node (ref "U$10") (pin "14") (pinfunction "2_14") (pintype "passive"))
    )
    (net (code "148") (name "Net-(LTC3-A3)") (class "Default")
      (node (ref "LTC3") (pin "P$40") (pinfunction "A3_P$40") (pintype "bidirectional"))
      (node (ref "U$10") (pin "17") (pinfunction "2_17") (pintype "passive"))
    )
    (net (code "149") (name "Net-(LTC3-C0)") (class "Default")
      (node (ref "D42") (pin "A") (pinfunction "A_A") (pintype "passive"))
      (node (ref "LTC3") (pin "P$26") (pinfunction "C0_P$26") (pintype "bidirectional"))
      (node (ref "LTC3_C0") (pin "P$1") (pinfunction "TP_P$1") (pintype "input"))
      (node (ref "R154") (pin "2") (pinfunction "2_2") (pintype "passive"))
    )
    (net (code "150") (name "Net-(LTC3-C1)") (class "Default")
      (node (ref "C44") (pin "1") (pinfunction "1_1") (pintype "passive"))
      (node (ref "D41") (pin "A") (pinfunction "A_A") (pintype "passive"))
      (node (ref "D42") (pin "C") (pinfunction "C_C") (pintype "passive"))
      (node (ref "LTC3") (pin "P$24") (pinfunction "C1_P$24") (pintype "bidirectional"))
      (node (ref "LTC3_C1") (pin "P$1") (pinfunction "TP_P$1") (pintype "input"))
      (node (ref "R149") (pin "2") (pinfunction "2_2") (pintype "passive"))
    )
    (net (code "151") (name "Net-(LTC3-C2)") (class "Default")
      (node (ref "C43") (pin "1") (pinfunction "1_1") (pintype "passive"))
      (node (ref "D40") (pin "A") (pinfunction "A_A") (pintype "passive"))
      (node (ref "D41") (pin "C") (pinfunction "C_C") (pintype "passive"))
      (node (ref "LTC3") (pin "P$22") (pinfunction "C2_P$22") (pintype "bidirectional"))
      (node (ref "LTC3_C2") (pin "P$1") (pinfunction "TP_P$1") (pintype "input"))
      (node (ref "R145") (pin "2") (pinfunction "2_2") (pintype "passive"))
    )
    (net (code "152") (name "Net-(LTC3-C3)") (class "Default")
      (node (ref "C42") (pin "1") (pinfunction "1_1") (pintype "passive"))
      (node (ref "D39") (pin "A") (pinfunction "A_A") (pintype "passive"))
      (node (ref "D40") (pin "C") (pinfunction "C_C") (pintype "passive"))
      (node (ref "LTC3") (pin "P$20") (pinfunction "C3_P$20") (pintype "bidirectional"))
      (node (ref "LTC3_C3") (pin "P$1") (pinfunction "TP_P$1") (pintype "input"))
      (node (ref "R141") (pin "2") (pinfunction "2_2") (pintype "passive"))
    )
    (net (code "153") (name "Net-(LTC3-C4)") (class "Default")
      (node (ref "C41") (pin "1") (pinfunction "1_1") (pintype "passive"))
      (node (ref "D38") (pin "A") (pinfunction "A_A") (pintype "passive"))
      (node (ref "D39") (pin "C") (pinfunction "C_C") (pintype "passive"))
      (node (ref "LTC3") (pin "P$18") (pinfunction "C4_P$18") (pintype "bidirectional"))
      (node (ref "LTC3_C4") (pin "P$1") (pinfunction "TP_P$1") (pintype "input"))
      (node (ref "R137") (pin "2") (pinfunction "2_2") (pintype "passive"))
    )
    (net (code "154") (name "Net-(LTC3-C5)") (class "Default")
      (node (ref "C40") (pin "1") (pinfunction "1_1") (pintype "passive"))
      (node (ref "D37") (pin "A") (pinfunction "A_A") (pintype "passive"))
      (node (ref "D38") (pin "C") (pinfunction "C_C") (pintype "passive"))
      (node (ref "LTC3") (pin "P$16") (pinfunction "C5_P$16") (pintype "bidirectional"))
      (node (ref "LTC3_C5") (pin "P$1") (pinfunction "TP_P$1") (pintype "input"))
      (node (ref "R133") (pin "2") (pinfunction "2_2") (pintype "passive"))
    )
    (net (code "155") (name "Net-(LTC3-C6)") (class "Default")
      (node (ref "C39") (pin "1") (pinfunction "1_1") (pintype "passive"))
      (node (ref "D36") (pin "A") (pinfunction "A_A") (pintype "passive"))
      (node (ref "D37") (pin "C") (pinfunction "C_C") (pintype "passive"))
      (node (ref "LTC3") (pin "P$14") (pinfunction "C6_P$14") (pintype "bidirectional"))
      (node (ref "LTC3_C6") (pin "P$1") (pinfunction "TP_P$1") (pintype "input"))
      (node (ref "R129") (pin "2") (pinfunction "2_2") (pintype "passive"))
    )
    (net (code "156") (name "Net-(LTC3-C7)") (class "Default")
      (node (ref "C38") (pin "1") (pinfunction "1_1") (pintype "passive"))
      (node (ref "D35") (pin "A") (pinfunction "A_A") (pintype "passive"))
      (node (ref "D36") (pin "C") (pinfunction "C_C") (pintype "passive"))
      (node (ref "LTC3") (pin "P$12") (pinfunction "C7_P$12") (pintype "bidirectional"))
      (node (ref "LTC3_C7") (pin "P$1") (pinfunction "TP_P$1") (pintype "input"))
      (node (ref "R125") (pin "2") (pinfunction "2_2") (pintype "passive"))
    )
    (net (code "157") (name "Net-(LTC3-C8)") (class "Default")
      (node (ref "C37") (pin "1") (pinfunction "1_1") (pintype "passive"))
      (node (ref "D34") (pin "A") (pinfunction "A_A") (pintype "passive"))
      (node (ref "D35") (pin "C") (pinfunction "C_C") (pintype "passive"))
      (node (ref "LTC3") (pin "P$10") (pinfunction "C8_P$10") (pintype "bidirectional"))
      (node (ref "LTC3_C8") (pin "P$1") (pinfunction "TP_P$1") (pintype "input"))
      (node (ref "R121") (pin "2") (pinfunction "2_2") (pintype "passive"))
    )
    (net (code "158") (name "Net-(LTC3-C9)") (class "Default")
      (node (ref "C36") (pin "1") (pinfunction "1_1") (pintype "passive"))
      (node (ref "D33") (pin "A") (pinfunction "A_A") (pintype "passive"))
      (node (ref "D34") (pin "C") (pinfunction "C_C") (pintype "passive"))
      (node (ref "LTC3") (pin "P$8") (pinfunction "C9_P$8") (pintype "bidirectional"))
      (node (ref "LTC3_C9") (pin "P$1") (pinfunction "TP_P$1") (pintype "input"))
      (node (ref "R117") (pin "2") (pinfunction "2_2") (pintype "passive"))
    )
    (net (code "159") (name "Net-(LTC3-C10)") (class "Default")
      (node (ref "C35") (pin "1") (pinfunction "1_1") (pintype "passive"))
      (node (ref "D33") (pin "C") (pinfunction "C_C") (pintype "passive"))
      (node (ref "LTC3") (pin "P$2") (pinfunction "C12_P$2") (pintype "bidirectional"))
      (node (ref "LTC3") (pin "P$4") (pinfunction "C11_P$4") (pintype "bidirectional"))
      (node (ref "LTC3") (pin "P$6") (pinfunction "C10_P$6") (pintype "bidirectional"))
      (node (ref "LTC3_C10") (pin "P$1") (pinfunction "TP_P$1") (pintype "input"))
      (node (ref "R113") (pin "2") (pinfunction "2_2") (pintype "passive"))
    )
    (net (code "160") (name "Net-(LTC3-S1)") (class "Default")
      (node (ref "LTC3") (pin "P$25") (pinfunction "S1_P$25") (pintype "bidirectional"))
      (node (ref "LTC3_S1") (pin "P$1") (pinfunction "TP_P$1") (pintype "input"))
      (node (ref "R150") (pin "2") (pinfunction "2_2") (pintype "passive"))
    )
    (net (code "161") (name "Net-(LTC3-S2)") (class "Default")
      (node (ref "LTC3") (pin "P$23") (pinfunction "S2_P$23") (pintype "bidirectional"))
      (node (ref "LTC3_S2") (pin "P$1") (pinfunction "TP_P$1") (pintype "input"))
      (node (ref "R146") (pin "2") (pinfunction "2_2") (pintype "passive"))
    )
    (net (code "162") (name "Net-(LTC3-S3)") (class "Default")
      (node (ref "LTC3") (pin "P$21") (pinfunction "S3_P$21") (pintype "bidirectional"))
      (node (ref "LTC3_S3") (pin "P$1") (pinfunction "TP_P$1") (pintype "input"))
      (node (ref "R142") (pin "2") (pinfunction "2_2") (pintype "passive"))
    )
    (net (code "163") (name "Net-(LTC3-S4)") (class "Default")
      (node (ref "LTC3") (pin "P$19") (pinfunction "S4_P$19") (pintype "bidirectional"))
      (node (ref "LTC3_S4") (pin "P$1") (pinfunction "TP_P$1") (pintype "input"))
      (node (ref "R138") (pin "2") (pinfunction "2_2") (pintype "passive"))
    )
    (net (code "164") (name "Net-(LTC3-S5)") (class "Default")
      (node (ref "LTC3") (pin "P$17") (pinfunction "S5_P$17") (pintype "bidirectional"))
      (node (ref "LTC3_S5") (pin "P$1") (pinfunction "TP_P$1") (pintype "input"))
      (node (ref "R134") (pin "2") (pinfunction "2_2") (pintype "passive"))
    )
    (net (code "165") (name "Net-(LTC3-S6)") (class "Default")
      (node (ref "LTC3") (pin "P$15") (pinfunction "S6_P$15") (pintype "bidirectional"))
      (node (ref "LTC3_S6") (pin "P$1") (pinfunction "TP_P$1") (pintype "input"))
      (node (ref "R130") (pin "2") (pinfunction "2_2") (pintype "passive"))
    )
    (net (code "166") (name "Net-(LTC3-S7)") (class "Default")
      (node (ref "LTC3") (pin "P$13") (pinfunction "S7_P$13") (pintype "bidirectional"))
      (node (ref "LTC3_S7") (pin "P$1") (pinfunction "TP_P$1") (pintype "input"))
      (node (ref "R126") (pin "2") (pinfunction "2_2") (pintype "passive"))
    )
    (net (code "167") (name "Net-(LTC3-S8)") (class "Default")
      (node (ref "LTC3") (pin "P$11") (pinfunction "S8_P$11") (pintype "bidirectional"))
      (node (ref "LTC3_S8") (pin "P$1") (pinfunction "TP_P$1") (pintype "input"))
      (node (ref "R122") (pin "2") (pinfunction "2_2") (pintype "passive"))
    )
    (net (code "168") (name "Net-(LTC3-S9)") (class "Default")
      (node (ref "LTC3") (pin "P$9") (pinfunction "S9_P$9") (pintype "bidirectional"))
      (node (ref "LTC3_S9") (pin "P$1") (pinfunction "TP_P$1") (pintype "input"))
      (node (ref "R118") (pin "2") (pinfunction "2_2") (pintype "passive"))
    )
    (net (code "169") (name "Net-(LTC3-S10)") (class "Default")
      (node (ref "LTC3") (pin "P$7") (pinfunction "S10_P$7") (pintype "bidirectional"))
      (node (ref "LTC3_S10") (pin "P$1") (pinfunction "TP_P$1") (pintype "input"))
      (node (ref "R114") (pin "2") (pinfunction "2_2") (pintype "passive"))
    )
    (net (code "170") (name "Net-(LTC3-TOS)") (class "Default")
      (node (ref "LTC3") (pin "P$33") (pinfunction "TOS_P$33") (pintype "bidirectional"))
      (node (ref "R155") (pin "1") (pinfunction "1_1") (pintype "passive"))
    )
    (net (code "171") (name "Net-(LTC3-V+)") (class "Default")
      (node (ref "C45") (pin "1") (pinfunction "1_1") (pintype "passive"))
      (node (ref "LTC3") (pin "P$1") (pinfunction "V+_P$1") (pintype "bidirectional"))
      (node (ref "R153") (pin "2") (pinfunction "2_2") (pintype "passive"))
      (node (ref "V+3") (pin "TP") (pinfunction "TP_TP") (pintype "input"))
    )
    (net (code "172") (name "Net-(LTC3-VREF)") (class "Default")
      (node (ref "C47") (pin "1") (pinfunction "1_1") (pintype "passive"))
      (node (ref "LTC3") (pin "P$31") (pinfunction "VREF_P$31") (pintype "bidirectional"))
    )
    (net (code "173") (name "Net-(LTC3-WDTB)") (class "Default")
      (node (ref "LTC3") (pin "P$34") (pinfunction "WDTB_P$34") (pintype "bidirectional"))
      (node (ref "U$10") (pin "2") (pinfunction "2_2") (pintype "passive"))
    )
    (net (code "174") (name "Net-(Q3-D)") (class "Default")
      (node (ref "Q3") (pin "3") (pinfunction "D_3") (pintype "passive"))
      (node (ref "R12") (pin "2") (pinfunction "2_2") (pintype "passive"))
    )
    (net (code "175") (name "Net-(Q3-G)") (class "Default")
      (node (ref "Q3") (pin "1") (pinfunction "G_1") (pintype "passive"))
      (node (ref "R11") (pin "1") (pinfunction "1_1") (pintype "passive"))
    )
    (net (code "176") (name "Net-(Q3-S)") (class "Default")
      (node (ref "L5") (pin "2") (pinfunction "2_2") (pintype "passive"))
      (node (ref "Q3") (pin "2") (pinfunction "S_2") (pintype "passive"))
      (node (ref "R10") (pin "1") (pinfunction "1_1") (pintype "passive"))
    )
    (net (code "177") (name "Net-(Q4-D)") (class "Default")
      (node (ref "Q4") (pin "3") (pinfunction "D_3") (pintype "passive"))
      (node (ref "R16") (pin "2") (pinfunction "2_2") (pintype "passive"))
    )
    (net (code "178") (name "Net-(Q4-G)") (class "Default")
      (node (ref "Q4") (pin "1") (pinfunction "G_1") (pintype "passive"))
      (node (ref "R15") (pin "1") (pinfunction "1_1") (pintype "passive"))
    )
    (net (code "179") (name "Net-(Q4-S)") (class "Default")
      (node (ref "L6") (pin "2") (pinfunction "2_2") (pintype "passive"))
      (node (ref "Q4") (pin "2") (pinfunction "S_2") (pintype "passive"))
      (node (ref "R12") (pin "1") (pinfunction "1_1") (pintype "passive"))
      (node (ref "R14") (pin "1") (pinfunction "1_1") (pintype "passive"))
    )
    (net (code "180") (name "Net-(Q5-D)") (class "Default")
      (node (ref "Q5") (pin "3") (pinfunction "D_3") (pintype "passive"))
      (node (ref "R20") (pin "2") (pinfunction "2_2") (pintype "passive"))
    )
    (net (code "181") (name "Net-(Q5-G)") (class "Default")
      (node (ref "Q5") (pin "1") (pinfunction "G_1") (pintype "passive"))
      (node (ref "R19") (pin "1") (pinfunction "1_1") (pintype "passive"))
    )
    (net (code "182") (name "Net-(Q5-S)") (class "Default")
      (node (ref "L7") (pin "2") (pinfunction "2_2") (pintype "passive"))
      (node (ref "Q5") (pin "2") (pinfunction "S_2") (pintype "passive"))
      (node (ref "R16") (pin "1") (pinfunction "1_1") (pintype "passive"))
      (node (ref "R18") (pin "1") (pinfunction "1_1") (pintype "passive"))
    )
    (net (code "183") (name "Net-(Q6-D)") (class "Default")
      (node (ref "Q6") (pin "3") (pinfunction "D_3") (pintype "passive"))
      (node (ref "R24") (pin "2") (pinfunction "2_2") (pintype "passive"))
    )
    (net (code "184") (name "Net-(Q6-G)") (class "Default")
      (node (ref "Q6") (pin "1") (pinfunction "G_1") (pintype "passive"))
      (node (ref "R23") (pin "1") (pinfunction "1_1") (pintype "passive"))
    )
    (net (code "185") (name "Net-(Q6-S)") (class "Default")
      (node (ref "L8") (pin "2") (pinfunction "2_2") (pintype "passive"))
      (node (ref "Q6") (pin "2") (pinfunction "S_2") (pintype "passive"))
      (node (ref "R20") (pin "1") (pinfunction "1_1") (pintype "passive"))
      (node (ref "R22") (pin "1") (pinfunction "1_1") (pintype "passive"))
    )
    (net (code "186") (name "Net-(Q7-D)") (class "Default")
      (node (ref "Q7") (pin "3") (pinfunction "D_3") (pintype "passive"))
      (node (ref "R28") (pin "2") (pinfunction "2_2") (pintype "passive"))
    )
    (net (code "187") (name "Net-(Q7-G)") (class "Default")
      (node (ref "Q7") (pin "1") (pinfunction "G_1") (pintype "passive"))
      (node (ref "R27") (pin "1") (pinfunction "1_1") (pintype "passive"))
    )
    (net (code "188") (name "Net-(Q7-S)") (class "Default")
      (node (ref "L9") (pin "2") (pinfunction "2_2") (pintype "passive"))
      (node (ref "Q7") (pin "2") (pinfunction "S_2") (pintype "passive"))
      (node (ref "R24") (pin "1") (pinfunction "1_1") (pintype "passive"))
      (node (ref "R26") (pin "1") (pinfunction "1_1") (pintype "passive"))
    )
    (net (code "189") (name "Net-(Q8-D)") (class "Default")
      (node (ref "Q8") (pin "3") (pinfunction "D_3") (pintype "passive"))
      (node (ref "R32") (pin "2") (pinfunction "2_2") (pintype "passive"))
    )
    (net (code "190") (name "Net-(Q8-G)") (class "Default")
      (node (ref "Q8") (pin "1") (pinfunction "G_1") (pintype "passive"))
      (node (ref "R31") (pin "1") (pinfunction "1_1") (pintype "passive"))
    )
    (net (code "191") (name "Net-(Q8-S)") (class "Default")
      (node (ref "L10") (pin "2") (pinfunction "2_2") (pintype "passive"))
      (node (ref "Q8") (pin "2") (pinfunction "S_2") (pintype "passive"))
      (node (ref "R28") (pin "1") (pinfunction "1_1") (pintype "passive"))
      (node (ref "R30") (pin "1") (pinfunction "1_1") (pintype "passive"))
    )
    (net (code "192") (name "Net-(Q9-D)") (class "Default")
      (node (ref "Q9") (pin "3") (pinfunction "D_3") (pintype "passive"))
      (node (ref "R36") (pin "2") (pinfunction "2_2") (pintype "passive"))
    )
    (net (code "193") (name "Net-(Q9-G)") (class "Default")
      (node (ref "Q9") (pin "1") (pinfunction "G_1") (pintype "passive"))
      (node (ref "R35") (pin "1") (pinfunction "1_1") (pintype "passive"))
    )
    (net (code "194") (name "Net-(Q9-S)") (class "Default")
      (node (ref "L11") (pin "2") (pinfunction "2_2") (pintype "passive"))
      (node (ref "Q9") (pin "2") (pinfunction "S_2") (pintype "passive"))
      (node (ref "R32") (pin "1") (pinfunction "1_1") (pintype "passive"))
      (node (ref "R34") (pin "1") (pinfunction "1_1") (pintype "passive"))
    )
    (net (code "195") (name "Net-(Q10-D)") (class "Default")
      (node (ref "Q10") (pin "3") (pinfunction "D_3") (pintype "passive"))
      (node (ref "R40") (pin "2") (pinfunction "2_2") (pintype "passive"))
    )
    (net (code "196") (name "Net-(Q10-G)") (class "Default")
      (node (ref "Q10") (pin "1") (pinfunction "G_1") (pintype "passive"))
      (node (ref "R39") (pin "1") (pinfunction "1_1") (pintype "passive"))
    )
    (net (code "197") (name "Net-(Q10-S)") (class "Default")
      (node (ref "L12") (pin "2") (pinfunction "2_2") (pintype "passive"))
      (node (ref "Q10") (pin "2") (pinfunction "S_2") (pintype "passive"))
      (node (ref "R36") (pin "1") (pinfunction "1_1") (pintype "passive"))
      (node (ref "R38") (pin "1") (pinfunction "1_1") (pintype "passive"))
    )
    (net (code "198") (name "Net-(Q11-D)") (class "Default")
      (node (ref "Q11") (pin "3") (pinfunction "D_3") (pintype "passive"))
      (node (ref "R44") (pin "2") (pinfunction "2_2") (pintype "passive"))
    )
    (net (code "199") (name "Net-(Q11-G)") (class "Default")
      (node (ref "Q11") (pin "1") (pinfunction "G_1") (pintype "passive"))
      (node (ref "R43") (pin "1") (pinfunction "1_1") (pintype "passive"))
    )
    (net (code "200") (name "Net-(Q11-S)") (class "Default")
      (node (ref "L13") (pin "2") (pinfunction "2_2") (pintype "passive"))
      (node (ref "Q11") (pin "2") (pinfunction "S_2") (pintype "passive"))
      (node (ref "R40") (pin "1") (pinfunction "1_1") (pintype "passive"))
      (node (ref "R42") (pin "1") (pinfunction "1_1") (pintype "passive"))
    )
    (net (code "201") (name "Net-(Q12-D)") (class "Default")
      (node (ref "Q12") (pin "3") (pinfunction "D_3") (pintype "passive"))
      (node (ref "R48") (pin "2") (pinfunction "2_2") (pintype "passive"))
    )
    (net (code "202") (name "Net-(Q12-G)") (class "Default")
      (node (ref "Q12") (pin "1") (pinfunction "G_1") (pintype "passive"))
      (node (ref "R47") (pin "1") (pinfunction "1_1") (pintype "passive"))
    )
    (net (code "203") (name "Net-(Q12-S)") (class "Default")
      (node (ref "L14") (pin "2") (pinfunction "2_2") (pintype "passive"))
      (node (ref "Q12") (pin "2") (pinfunction "S_2") (pintype "passive"))
      (node (ref "R44") (pin "1") (pinfunction "1_1") (pintype "passive"))
      (node (ref "R46") (pin "1") (pinfunction "1_1") (pintype "passive"))
    )
    (net (code "204") (name "Net-(Q15-D)") (class "Default")
      (node (ref "Q15") (pin "3") (pinfunction "D_3") (pintype "passive"))
      (node (ref "R64") (pin "2") (pinfunction "2_2") (pintype "passive"))
    )
    (net (code "205") (name "Net-(Q15-G)") (class "Default")
      (node (ref "Q15") (pin "1") (pinfunction "G_1") (pintype "passive"))
      (node (ref "R63") (pin "1") (pinfunction "1_1") (pintype "passive"))
    )
    (net (code "206") (name "Net-(Q15-S)") (class "Default")
      (node (ref "L18") (pin "2") (pinfunction "2_2") (pintype "passive"))
      (node (ref "Q15") (pin "2") (pinfunction "S_2") (pintype "passive"))
      (node (ref "R62") (pin "1") (pinfunction "1_1") (pintype "passive"))
    )
    (net (code "207") (name "Net-(Q16-D)") (class "Default")
      (node (ref "Q16") (pin "3") (pinfunction "D_3") (pintype "passive"))
      (node (ref "R68") (pin "2") (pinfunction "2_2") (pintype "passive"))
    )
    (net (code "208") (name "Net-(Q16-G)") (class "Default")
      (node (ref "Q16") (pin "1") (pinfunction "G_1") (pintype "passive"))
      (node (ref "R67") (pin "1") (pinfunction "1_1") (pintype "passive"))
    )
    (net (code "209") (name "Net-(Q16-S)") (class "Default")
      (node (ref "L19") (pin "2") (pinfunction "2_2") (pintype "passive"))
      (node (ref "Q16") (pin "2") (pinfunction "S_2") (pintype "passive"))
      (node (ref "R64") (pin "1") (pinfunction "1_1") (pintype "passive"))
      (node (ref "R66") (pin "1") (pinfunction "1_1") (pintype "passive"))
    )
    (net (code "210") (name "Net-(Q17-D)") (class "Default")
      (node (ref "Q17") (pin "3") (pinfunction "D_3") (pintype "passive"))
      (node (ref "R72") (pin "2") (pinfunction "2_2") (pintype "passive"))
    )
    (net (code "211") (name "Net-(Q17-G)") (class "Default")
      (node (ref "Q17") (pin "1") (pinfunction "G_1") (pintype "passive"))
      (node (ref "R71") (pin "1") (pinfunction "1_1") (pintype "passive"))
    )
    (net (code "212") (name "Net-(Q17-S)") (class "Default")
      (node (ref "L20") (pin "2") (pinfunction "2_2") (pintype "passive"))
      (node (ref "Q17") (pin "2") (pinfunction "S_2") (pintype "passive"))
      (node (ref "R68") (pin "1") (pinfunction "1_1") (pintype "passive"))
      (node (ref "R70") (pin "1") (pinfunction "1_1") (pintype "passive"))
    )
    (net (code "213") (name "Net-(Q18-D)") (class "Default")
      (node (ref "Q18") (pin "3") (pinfunction "D_3") (pintype "passive"))
      (node (ref "R76") (pin "2") (pinfunction "2_2") (pintype "passive"))
    )
    (net (code "214") (name "Net-(Q18-G)") (class "Default")
      (node (ref "Q18") (pin "1") (pinfunction "G_1") (pintype "passive"))
      (node (ref "R75") (pin "1") (pinfunction "1_1") (pintype "passive"))
    )
    (net (code "215") (name "Net-(Q18-S)") (class "Default")
      (node (ref "L21") (pin "2") (pinfunction "2_2") (pintype "passive"))
      (node (ref "Q18") (pin "2") (pinfunction "S_2") (pintype "passive"))
      (node (ref "R72") (pin "1") (pinfunction "1_1") (pintype "passive"))
      (node (ref "R74") (pin "1") (pinfunction "1_1") (pintype "passive"))
    )
    (net (code "216") (name "Net-(Q19-D)") (class "Default")
      (node (ref "Q19") (pin "3") (pinfunction "D_3") (pintype "passive"))
      (node (ref "R80") (pin "2") (pinfunction "2_2") (pintype "passive"))
    )
    (net (code "217") (name "Net-(Q19-G)") (class "Default")
      (node (ref "Q19") (pin "1") (pinfunction "G_1") (pintype "passive"))
      (node (ref "R79") (pin "1") (pinfunction "1_1") (pintype "passive"))
    )
    (net (code "218") (name "Net-(Q19-S)") (class "Default")
      (node (ref "L22") (pin "2") (pinfunction "2_2") (pintype "passive"))
      (node (ref "Q19") (pin "2") (pinfunction "S_2") (pintype "passive"))
      (node (ref "R76") (pin "1") (pinfunction "1_1") (pintype "passive"))
      (node (ref "R78") (pin "1") (pinfunction "1_1") (pintype "passive"))
    )
    (net (code "219") (name "Net-(Q20-D)") (class "Default")
      (node (ref "Q20") (pin "3") (pinfunction "D_3") (pintype "passive"))
      (node (ref "R84") (pin "2") (pinfunction "2_2") (pintype "passive"))
    )
    (net (code "220") (name "Net-(Q20-G)") (class "Default")
      (node (ref "Q20") (pin "1") (pinfunction "G_1") (pintype "passive"))
      (node (ref "R83") (pin "1") (pinfunction "1_1") (pintype "passive"))
    )
    (net (code "221") (name "Net-(Q20-S)") (class "Default")
      (node (ref "L23") (pin "2") (pinfunction "2_2") (pintype "passive"))
      (node (ref "Q20") (pin "2") (pinfunction "S_2") (pintype "passive"))
      (node (ref "R80") (pin "1") (pinfunction "1_1") (pintype "passive"))
      (node (ref "R82") (pin "1") (pinfunction "1_1") (pintype "passive"))
    )
    (net (code "222") (name "Net-(Q21-D)") (class "Default")
      (node (ref "Q21") (pin "3") (pinfunction "D_3") (pintype "passive"))
      (node (ref "R88") (pin "2") (pinfunction "2_2") (pintype "passive"))
    )
    (net (code "223") (name "Net-(Q21-G)") (class "Default")
      (node (ref "Q21") (pin "1") (pinfunction "G_1") (pintype "passive"))
      (node (ref "R87") (pin "1") (pinfunction "1_1") (pintype "passive"))
    )
    (net (code "224") (name "Net-(Q21-S)") (class "Default")
      (node (ref "L24") (pin "2") (pinfunction "2_2") (pintype "passive"))
      (node (ref "Q21") (pin "2") (pinfunction "S_2") (pintype "passive"))
      (node (ref "R84") (pin "1") (pinfunction "1_1") (pintype "passive"))
      (node (ref "R86") (pin "1") (pinfunction "1_1") (pintype "passive"))
    )
    (net (code "225") (name "Net-(Q22-D)") (class "Default")
      (node (ref "Q22") (pin "3") (pinfunction "D_3") (pintype "passive"))
      (node (ref "R92") (pin "2") (pinfunction "2_2") (pintype "passive"))
    )
    (net (code "226") (name "Net-(Q22-G)") (class "Default")
      (node (ref "Q22") (pin "1") (pinfunction "G_1") (pintype "passive"))
      (node (ref "R91") (pin "1") (pinfunction "1_1") (pintype "passive"))
    )
    (net (code "227") (name "Net-(Q22-S)") (class "Default")
      (node (ref "L25") (pin "2") (pinfunction "2_2") (pintype "passive"))
      (node (ref "Q22") (pin "2") (pinfunction "S_2") (pintype "passive"))
      (node (ref "R88") (pin "1") (pinfunction "1_1") (pintype "passive"))
      (node (ref "R90") (pin "1") (pinfunction "1_1") (pintype "passive"))
    )
    (net (code "228") (name "Net-(Q23-D)") (class "Default")
      (node (ref "Q23") (pin "3") (pinfunction "D_3") (pintype "passive"))
      (node (ref "R96") (pin "2") (pinfunction "2_2") (pintype "passive"))
    )
    (net (code "229") (name "Net-(Q23-G)") (class "Default")
      (node (ref "Q23") (pin "1") (pinfunction "G_1") (pintype "passive"))
      (node (ref "R95") (pin "1") (pinfunction "1_1") (pintype "passive"))
    )
    (net (code "230") (name "Net-(Q23-S)") (class "Default")
      (node (ref "L26") (pin "2") (pinfunction "2_2") (pintype "passive"))
      (node (ref "Q23") (pin "2") (pinfunction "S_2") (pintype "passive"))
      (node (ref "R92") (pin "1") (pinfunction "1_1") (pintype "passive"))
      (node (ref "R94") (pin "1") (pinfunction "1_1") (pintype "passive"))
    )
    (net (code "231") (name "Net-(Q24-D)") (class "Default")
      (node (ref "Q24") (pin "3") (pinfunction "D_3") (pintype "passive"))
      (node (ref "R100") (pin "2") (pinfunction "2_2") (pintype "passive"))
    )
    (net (code "232") (name "Net-(Q24-G)") (class "Default")
      (node (ref "Q24") (pin "1") (pinfunction "G_1") (pintype "passive"))
      (node (ref "R99") (pin "1") (pinfunction "1_1") (pintype "passive"))
    )
    (net (code "233") (name "Net-(Q24-S)") (class "Default")
      (node (ref "L27") (pin "2") (pinfunction "2_2") (pintype "passive"))
      (node (ref "Q24") (pin "2") (pinfunction "S_2") (pintype "passive"))
      (node (ref "R96") (pin "1") (pinfunction "1_1") (pintype "passive"))
      (node (ref "R98") (pin "1") (pinfunction "1_1") (pintype "passive"))
    )
    (net (code "234") (name "Net-(Q27-D)") (class "Default")
      (node (ref "Q27") (pin "3") (pinfunction "D_3") (pintype "passive"))
      (node (ref "R115") (pin "2") (pinfunction "2_2") (pintype "passive"))
    )
    (net (code "235") (name "Net-(Q27-G)") (class "Default")
      (node (ref "Q27") (pin "1") (pinfunction "G_1") (pintype "passive"))
      (node (ref "R114") (pin "1") (pinfunction "1_1") (pintype "passive"))
    )
    (net (code "236") (name "Net-(Q27-S)") (class "Default")
      (node (ref "L33") (pin "2") (pinfunction "2_2") (pintype "passive"))
      (node (ref "Q27") (pin "2") (pinfunction "S_2") (pintype "passive"))
      (node (ref "R113") (pin "1") (pinfunction "1_1") (pintype "passive"))
    )
    (net (code "237") (name "Net-(Q28-D)") (class "Default")
      (node (ref "Q28") (pin "3") (pinfunction "D_3") (pintype "passive"))
      (node (ref "R119") (pin "2") (pinfunction "2_2") (pintype "passive"))
    )
    (net (code "238") (name "Net-(Q28-G)") (class "Default")
      (node (ref "Q28") (pin "1") (pinfunction "G_1") (pintype "passive"))
      (node (ref "R118") (pin "1") (pinfunction "1_1") (pintype "passive"))
    )
    (net (code "239") (name "Net-(Q28-S)") (class "Default")
      (node (ref "L34") (pin "2") (pinfunction "2_2") (pintype "passive"))
      (node (ref "Q28") (pin "2") (pinfunction "S_2") (pintype "passive"))
      (node (ref "R115") (pin "1") (pinfunction "1_1") (pintype "passive"))
      (node (ref "R117") (pin "1") (pinfunction "1_1") (pintype "passive"))
    )
    (net (code "240") (name "Net-(Q29-D)") (class "Default")
      (node (ref "Q29") (pin "3") (pinfunction "D_3") (pintype "passive"))
      (node (ref "R123") (pin "2") (pinfunction "2_2") (pintype "passive"))
    )
    (net (code "241") (name "Net-(Q29-G)") (class "Default")
      (node (ref "Q29") (pin "1") (pinfunction "G_1") (pintype "passive"))
      (node (ref "R122") (pin "1") (pinfunction "1_1") (pintype "passive"))
    )
    (net (code "242") (name "Net-(Q29-S)") (class "Default")
      (node (ref "L35") (pin "2") (pinfunction "2_2") (pintype "passive"))
      (node (ref "Q29") (pin "2") (pinfunction "S_2") (pintype "passive"))
      (node (ref "R119") (pin "1") (pinfunction "1_1") (pintype "passive"))
      (node (ref "R121") (pin "1") (pinfunction "1_1") (pintype "passive"))
    )
    (net (code "243") (name "Net-(Q30-D)") (class "Default")
      (node (ref "Q30") (pin "3") (pinfunction "D_3") (pintype "passive"))
      (node (ref "R127") (pin "2") (pinfunction "2_2") (pintype "passive"))
    )
    (net (code "244") (name "Net-(Q30-G)") (class "Default")
      (node (ref "Q30") (pin "1") (pinfunction "G_1") (pintype "passive"))
      (node (ref "R126") (pin "1") (pinfunction "1_1") (pintype "passive"))
    )
    (net (code "245") (name "Net-(Q30-S)") (class "Default")
      (node (ref "L36") (pin "2") (pinfunction "2_2") (pintype "passive"))
      (node (ref "Q30") (pin "2") (pinfunction "S_2") (pintype "passive"))
      (node (ref "R123") (pin "1") (pinfunction "1_1") (pintype "passive"))
      (node (ref "R125") (pin "1") (pinfunction "1_1") (pintype "passive"))
    )
    (net (code "246") (name "Net-(Q31-D)") (class "Default")
      (node (ref "Q31") (pin "3") (pinfunction "D_3") (pintype "passive"))
      (node (ref "R131") (pin "2") (pinfunction "2_2") (pintype "passive"))
    )
    (net (code "247") (name "Net-(Q31-G)") (class "Default")
      (node (ref "Q31") (pin "1") (pinfunction "G_1") (pintype "passive"))
      (node (ref "R130") (pin "1") (pinfunction "1_1") (pintype "passive"))
    )
    (net (code "248") (name "Net-(Q31-S)") (class "Default")
      (node (ref "L37") (pin "2") (pinfunction "2_2") (pintype "passive"))
      (node (ref "Q31") (pin "2") (pinfunction "S_2") (pintype "passive"))
      (node (ref "R127") (pin "1") (pinfunction "1_1") (pintype "passive"))
      (node (ref "R129") (pin "1") (pinfunction "1_1") (pintype "passive"))
    )
    (net (code "249") (name "Net-(Q32-D)") (class "Default")
      (node (ref "Q32") (pin "3") (pinfunction "D_3") (pintype "passive"))
      (node (ref "R135") (pin "2") (pinfunction "2_2") (pintype "passive"))
    )
    (net (code "250") (name "Net-(Q32-G)") (class "Default")
      (node (ref "Q32") (pin "1") (pinfunction "G_1") (pintype "passive"))
      (node (ref "R134") (pin "1") (pinfunction "1_1") (pintype "passive"))
    )
    (net (code "251") (name "Net-(Q32-S)") (class "Default")
      (node (ref "L38") (pin "2") (pinfunction "2_2") (pintype "passive"))
      (node (ref "Q32") (pin "2") (pinfunction "S_2") (pintype "passive"))
      (node (ref "R131") (pin "1") (pinfunction "1_1") (pintype "passive"))
      (node (ref "R133") (pin "1") (pinfunction "1_1") (pintype "passive"))
    )
    (net (code "252") (name "Net-(Q33-D)") (class "Default")
      (node (ref "Q33") (pin "3") (pinfunction "D_3") (pintype "passive"))
      (node (ref "R139") (pin "2") (pinfunction "2_2") (pintype "passive"))
    )
    (net (code "253") (name "Net-(Q33-G)") (class "Default")
      (node (ref "Q33") (pin "1") (pinfunction "G_1") (pintype "passive"))
      (node (ref "R138") (pin "1") (pinfunction "1_1") (pintype "passive"))
    )
    (net (code "254") (name "Net-(Q33-S)") (class "Default")
      (node (ref "L39") (pin "2") (pinfunction "2_2") (pintype "passive"))
      (node (ref "Q33") (pin "2") (pinfunction "S_2") (pintype "passive"))
      (node (ref "R135") (pin "1") (pinfunction "1_1") (pintype "passive"))
      (node (ref "R137") (pin "1") (pinfunction "1_1") (pintype "passive"))
    )
    (net (code "255") (name "Net-(Q34-D)") (class "Default")
      (node (ref "Q34") (pin "3") (pinfunction "D_3") (pintype "passive"))
      (node (ref "R143") (pin "2") (pinfunction "2_2") (pintype "passive"))
    )
    (net (code "256") (name "Net-(Q34-G)") (class "Default")
      (node (ref "Q34") (pin "1") (pinfunction "G_1") (pintype "passive"))
      (node (ref "R142") (pin "1") (pinfunction "1_1") (pintype "passive"))
    )
    (net (code "257") (name "Net-(Q34-S)") (class "Default")
      (node (ref "L40") (pin "2") (pinfunction "2_2") (pintype "passive"))
      (node (ref "Q34") (pin "2") (pinfunction "S_2") (pintype "passive"))
      (node (ref "R139") (pin "1") (pinfunction "1_1") (pintype "passive"))
      (node (ref "R141") (pin "1") (pinfunction "1_1") (pintype "passive"))
    )
    (net (code "258") (name "Net-(Q35-D)") (class "Default")
      (node (ref "Q35") (pin "3") (pinfunction "D_3") (pintype "passive"))
      (node (ref "R147") (pin "2") (pinfunction "2_2") (pintype "passive"))
    )
    (net (code "259") (name "Net-(Q35-G)") (class "Default")
      (node (ref "Q35") (pin "1") (pinfunction "G_1") (pintype "passive"))
      (node (ref "R146") (pin "1") (pinfunction "1_1") (pintype "passive"))
    )
    (net (code "260") (name "Net-(Q35-S)") (class "Default")
      (node (ref "L41") (pin "2") (pinfunction "2_2") (pintype "passive"))
      (node (ref "Q35") (pin "2") (pinfunction "S_2") (pintype "passive"))
      (node (ref "R143") (pin "1") (pinfunction "1_1") (pintype "passive"))
      (node (ref "R145") (pin "1") (pinfunction "1_1") (pintype "passive"))
    )
    (net (code "261") (name "Net-(Q36-D)") (class "Default")
      (node (ref "Q36") (pin "3") (pinfunction "D_3") (pintype "passive"))
      (node (ref "R151") (pin "2") (pinfunction "2_2") (pintype "passive"))
    )
    (net (code "262") (name "Net-(Q36-G)") (class "Default")
      (node (ref "Q36") (pin "1") (pinfunction "G_1") (pintype "passive"))
      (node (ref "R150") (pin "1") (pinfunction "1_1") (pintype "passive"))
    )
    (net (code "263") (name "Net-(Q36-S)") (class "Default")
      (node (ref "L42") (pin "2") (pinfunction "2_2") (pintype "passive"))
      (node (ref "Q36") (pin "2") (pinfunction "S_2") (pintype "passive"))
      (node (ref "R147") (pin "1") (pinfunction "1_1") (pintype "passive"))
      (node (ref "R149") (pin "1") (pinfunction "1_1") (pintype "passive"))
    )
    (net (code "264") (name "Net-(R164-Pad1)") (class "Default")
      (node (ref "R164") (pin "1") (pinfunction "1_1") (pintype "passive"))
      (node (ref "U$10") (pin "3") (pinfunction "3_3") (pintype "passive"))
    )
    (net (code "265") (name "Net-(R166-Pad1)") (class "Default")
      (node (ref "R166") (pin "1") (pinfunction "1_1") (pintype "passive"))
      (node (ref "U$9") (pin "3") (pinfunction "3_3") (pintype "passive"))
    )
    (net (code "266") (name "Net-(R168-Pad1)") (class "Default")
      (node (ref "R168") (pin "1") (pinfunction "1_1") (pintype "passive"))
      (node (ref "U$8") (pin "3") (pinfunction "3_3") (pintype "passive"))
    )
    (net (code "267") (name "Net-(S2-P)") (class "Default")
      (node (ref "R1") (pin "1") (pinfunction "1_1") (pintype "passive"))
      (node (ref "S2") (pin "3") (pinfunction "P_3") (pintype "passive"))
      (node (ref "S2") (pin "4") (pinfunction "P1_4") (pintype "passive"))
      (node (ref "SV1") (pin "1") (pinfunction "1_1") (pintype "passive"))
    )
    (net (code "268") (name "Net-(T1-D)") (class "Default")
      (node (ref "K1") (pin "2") (pinfunction "2_2") (pintype "passive"))
      (node (ref "T1") (pin "3") (pinfunction "D_3") (pintype "passive"))
    )
    (net (code "269") (name "Net-(U$2-VCAP)") (class "Default")
      (node (ref "C22") (pin "1") (pinfunction "1_1") (pintype "passive"))
      (node (ref "U$2") (pin "20") (pinfunction "VCAP_20") (pintype "bidirectional"))
    )
    (net (code "270") (name "Net-(U$2-~{MCLR})") (class "Default")
      (node (ref "R53") (pin "2") (pinfunction "2_2") (pintype "passive"))
      (node (ref "U$2") (pin "1") (pinfunction "~{MCLR}_1") (pintype "bidirectional"))
    )
    (net (code "271") (name "Net-(U$8B-2)") (class "Default")
      (node (ref "R5") (pin "2") (pinfunction "2_2") (pintype "passive"))
      (node (ref "U$8") (pin "5") (pinfunction "2_5") (pintype "passive"))
    )
    (net (code "272") (name "Net-(U$9B-2)") (class "Default")
      (node (ref "R104") (pin "2") (pinfunction "2_2") (pintype "passive"))
      (node (ref "U$9") (pin "5") (pinfunction "2_5") (pintype "passive"))
    )
    (net (code "273") (name "Net-(U$10B-2)") (class "Default")
      (node (ref "R155") (pin "2") (pinfunction "2_2") (pintype "passive"))
      (node (ref "U$10") (pin "5") (pinfunction "2_5") (pintype "passive"))
    )
    (net (code "274") (name "OSC1") (class "Default")
      (node (ref "PROGRAM") (pin "1") (pinfunction "S_1") (pintype "passive"))
      (node (ref "U$2") (pin "9") (pinfunction "OSC1_9") (pintype "bidirectional"))
      (node (ref "U$3") (pin "3") (pinfunction "OUT_3") (pintype "output"))
    )
    (net (code "275") (name "PE") (class "Default")
      (node (ref "C35") (pin "2") (pinfunction "2_2") (pintype "passive"))
      (node (ref "C36") (pin "2") (pinfunction "2_2") (pintype "passive"))
      (node (ref "C37") (pin "2") (pinfunction "2_2") (pintype "passive"))
      (node (ref "C38") (pin "2") (pinfunction "2_2") (pintype "passive"))
      (node (ref "C39") (pin "2") (pinfunction "2_2") (pintype "passive"))
      (node (ref "C40") (pin "2") (pinfunction "2_2") (pintype "passive"))
      (node (ref "C41") (pin "2") (pinfunction "2_2") (pintype "passive"))
      (node (ref "C42") (pin "2") (pinfunction "2_2") (pintype "passive"))
      (node (ref "C43") (pin "2") (pinfunction "2_2") (pintype "passive"))
      (node (ref "C44") (pin "2") (pinfunction "2_2") (pintype "passive"))
      (node (ref "C45") (pin "2") (pinfunction "2_2") (pintype "passive"))
      (node (ref "C46") (pin "2") (pinfunction "2_2") (pintype "passive"))
      (node (ref "C47") (pin "2") (pinfunction "2_2") (pintype "passive"))
      (node (ref "D43") (pin "A") (pinfunction "A_A") (pintype "passive"))
      (node (ref "D44") (pin "A") (pinfunction "A_A") (pintype "passive"))
      (node (ref "D45") (pin "A") (pinfunction "A_A") (pintype "passive"))
      (node (ref "IC3_") (pin "15") (pinfunction "GND2_15") (pintype "power_in"))
      (node (ref "IC3_") (pin "9") (pinfunction "GND2_9") (pintype "power_in"))
      (node (ref "L44") (pin "2") (pinfunction "2_2") (pintype "passive"))
      (node (ref "LTC3") (pin "P$27") (pinfunction "V-_P$27") (pintype "bidirectional"))
      (node (ref "LTC3") (pin "P$28") (pinfunction "NC_P$28") (pintype "bidirectional"))
      (node (ref "LTC3") (pin "P$29") (pinfunction "V_TEMP1_P$29") (pintype "bidirectional"))
      (node (ref "LTC3") (pin "P$30") (pinfunction "V_TEMP2_P$30") (pintype "bidirectional"))
      (node (ref "LTC3") (pin "P$35") (pinfunction "GPIO1_P$35") (pintype "bidirectional"))
      (node (ref "LTC3") (pin "P$36") (pinfunction "GPIO2_P$36") (pintype "bidirectional"))
      (node (ref "U$10") (pin "1") (pinfunction "1_1") (pintype "passive"))
      (node (ref "U$10") (pin "10") (pinfunction "1_10") (pintype "passive"))
      (node (ref "U$10") (pin "13") (pinfunction "1_13") (pintype "passive"))
      (node (ref "U$10") (pin "16") (pinfunction "1_16") (pintype "passive"))
      (node (ref "U$10") (pin "4") (pinfunction "1_4") (pintype "passive"))
      (node (ref "U$10") (pin "7") (pinfunction "1_7") (pintype "passive"))
      (node (ref "V-3") (pin "TP") (pinfunction "TP_TP") (pintype "input"))
    )
    (net (code "276") (name "PGEC1") (class "Default")
      (node (ref "PROGRAM") (pin "2") (pinfunction "S_2") (pintype "passive"))
      (node (ref "U$17") (pin "P$1") (pinfunction "TP_P$1") (pintype "input"))
      (node (ref "U$2") (pin "5") (pinfunction "PGEC1/RB1_5") (pintype "bidirectional"))
    )
    (net (code "277") (name "PGED1") (class "Default")
      (node (ref "PROGRAM") (pin "3") (pinfunction "S_3") (pintype "passive"))
      (node (ref "U$16") (pin "P$1") (pinfunction "TP_P$1") (pintype "input"))
      (node (ref "U$2") (pin "4") (pinfunction "PGED1/RB0_4") (pintype "bidirectional"))
    )
    (net (code "278") (name "RELAY") (class "Default")
      (node (ref "R2") (pin "2") (pinfunction "2_2") (pintype "passive"))
      (node (ref "T1") (pin "1") (pinfunction "G_1") (pintype "passive"))
      (node (ref "U$2") (pin "11") (pinfunction "RB4_11") (pintype "bidirectional"))
      (node (ref "U$21") (pin "P$1") (pinfunction "TP_P$1") (pintype "input"))
    )
    (net (code "279") (name "RX") (class "Default")
      (node (ref "U$2") (pin "18") (pinfunction "RB9_18") (pintype "bidirectional"))
      (node (ref "U$27") (pin "P$1") (pinfunction "TP_P$1") (pintype "input"))
      (node (ref "U$5") (pin "5") (pinfunction "2_5") (pintype "passive"))
    )
    (net (code "280") (name "SCK") (class "Default")
      (node (ref "IC1") (pin "3") (pinfunction "VIA_3") (pintype "input"))
      (node (ref "IC2_\\") (pin "3") (pinfunction "VIA_3") (pintype "input"))
      (node (ref "IC3_") (pin "3") (pinfunction "VIA_3") (pintype "input"))
      (node (ref "SCK1_O") (pin "TP") (pinfunction "TP_TP") (pintype "input"))
      (node (ref "SCK2_O") (pin "TP") (pinfunction "TP_TP") (pintype "input"))
      (node (ref "SCK3_O") (pin "TP") (pinfunction "TP_TP") (pintype "input"))
      (node (ref "U$19") (pin "P$1") (pinfunction "TP_P$1") (pintype "input"))
      (node (ref "U$2") (pin "7") (pinfunction "RB3_7") (pintype "bidirectional"))
      (node (ref "U$6") (pin "13") (pinfunction "CLK_13") (pintype "bidirectional"))
    )
    (net (code "281") (name "SELECT1") (class "Default")
      (node (ref "U$4") (pin "1") (pinfunction "FAULT_1") (pintype "bidirectional"))
      (node (ref "U$5") (pin "3") (pinfunction "3_3") (pintype "passive"))
    )
    (net (code "282") (name "SELECT2") (class "Default")
      (node (ref "U$4") (pin "2") (pinfunction "RO_2") (pintype "bidirectional"))
      (node (ref "U$5") (pin "6") (pinfunction "3_6") (pintype "passive"))
    )
    (net (code "283") (name "SELECT3") (class "Default")
      (node (ref "U$4") (pin "3") (pinfunction "DE/RE_3") (pintype "bidirectional"))
      (node (ref "U$5") (pin "9") (pinfunction "3_9") (pintype "passive"))
    )
    (net (code "284") (name "SELECT4") (class "Default")
      (node (ref "U$4") (pin "4") (pinfunction "DI_4") (pintype "bidirectional"))
      (node (ref "U$5") (pin "12") (pinfunction "3_12") (pintype "passive"))
    )
    (net (code "285") (name "TX") (class "Default")
      (node (ref "U$2") (pin "21") (pinfunction "RB10_21") (pintype "bidirectional"))
      (node (ref "U$28") (pin "P$1") (pinfunction "TP_P$1") (pintype "input"))
      (node (ref "U$5") (pin "11") (pinfunction "2_11") (pintype "passive"))
    )
    (net (code "286") (name "V+") (class "Default")
      (node (ref "C2") (pin "1") (pinfunction "1_1") (pintype "passive"))
      (node (ref "IC1") (pin "10") (pinfunction "VE2_10") (pintype "passive"))
      (node (ref "IC1") (pin "16") (pinfunction "VDD2_16") (pintype "power_in"))
      (node (ref "LTC1") (pin "P$32") (pinfunction "VREG_P$32") (pintype "bidirectional"))
      (node (ref "R167") (pin "1") (pinfunction "1_1") (pintype "passive"))
      (node (ref "U$8") (pin "12") (pinfunction "3_12") (pintype "passive"))
      (node (ref "U$8") (pin "15") (pinfunction "3_15") (pintype "passive"))
      (node (ref "U$8") (pin "18") (pinfunction "3_18") (pintype "passive"))
      (node (ref "U$8") (pin "6") (pinfunction "3_6") (pintype "passive"))
      (node (ref "U$8") (pin "9") (pinfunction "3_9") (pintype "passive"))
      (node (ref "VREG1") (pin "P$1") (pinfunction "TP_P$1") (pintype "input"))
    )
    (net (code "287") (name "VCC") (class "Default")
      (node (ref "C31") (pin "1") (pinfunction "1_1") (pintype "passive"))
      (node (ref "IC2_\\") (pin "10") (pinfunction "VE2_10") (pintype "passive"))
      (node (ref "IC2_\\") (pin "16") (pinfunction "VDD2_16") (pintype "power_in"))
      (node (ref "LTC2") (pin "P$32") (pinfunction "VREG_P$32") (pintype "bidirectional"))
      (node (ref "R165") (pin "1") (pinfunction "1_1") (pintype "passive"))
      (node (ref "U$9") (pin "12") (pinfunction "3_12") (pintype "passive"))
      (node (ref "U$9") (pin "15") (pinfunction "3_15") (pintype "passive"))
      (node (ref "U$9") (pin "18") (pinfunction "3_18") (pintype "passive"))
      (node (ref "U$9") (pin "6") (pinfunction "3_6") (pintype "passive"))
      (node (ref "U$9") (pin "9") (pinfunction "3_9") (pintype "passive"))
      (node (ref "VREG2") (pin "P$1") (pinfunction "TP_P$1") (pintype "input"))
    )
    (net (code "288") (name "VCCIO") (class "Default")
      (node (ref "C49") (pin "1") (pinfunction "1_1") (pintype "passive"))
      (node (ref "U$11") (pin "P$1") (pinfunction "TP_P$1") (pintype "input"))
      (node (ref "U$6") (pin "15") (pinfunction "VREF_15") (pintype "bidirectional"))
      (node (ref "U$7") (pin "2") (pinfunction "OUT_2") (pintype "bidirectional"))
    )
    (net (code "289") (name "VCC{slash}2") (class "Default")
      (node (ref "C46") (pin "1") (pinfunction "1_1") (pintype "passive"))
      (node (ref "IC3_") (pin "10") (pinfunction "VE2_10") (pintype "passive"))
      (node (ref "IC3_") (pin "16") (pinfunction "VDD2_16") (pintype "power_in"))
      (node (ref "LTC3") (pin "P$32") (pinfunction "VREG_P$32") (pintype "bidirectional"))
      (node (ref "R163") (pin "1") (pinfunction "1_1") (pintype "passive"))
      (node (ref "U$10") (pin "12") (pinfunction "3_12") (pintype "passive"))
      (node (ref "U$10") (pin "15") (pinfunction "3_15") (pintype "passive"))
      (node (ref "U$10") (pin "18") (pinfunction "3_18") (pintype "passive"))
      (node (ref "U$10") (pin "6") (pinfunction "3_6") (pintype "passive"))
      (node (ref "U$10") (pin "9") (pinfunction "3_9") (pintype "passive"))
      (node (ref "VREG3") (pin "P$1") (pinfunction "TP_P$1") (pintype "input"))
    )
    (net (code "290") (name "WARN1") (class "Default")
      (node (ref "SV1") (pin "2") (pinfunction "2_2") (pintype "passive"))
      (node (ref "U$14") (pin "P$1") (pinfunction "TP_P$1") (pintype "input"))
      (node (ref "U$2") (pin "2") (pinfunction "RA0_2") (pintype "bidirectional"))
    )
    (net (code "291") (name "WARN2") (class "Default")
      (node (ref "R157") (pin "2") (pinfunction "2_2") (pintype "passive"))
      (node (ref "U$15") (pin "P$1") (pinfunction "TP_P$1") (pintype "input"))
      (node (ref "U$2") (pin "3") (pinfunction "RA1_3") (pintype "bidirectional"))
    )
    (net (code "292") (name "unconnected-(LTC1-S11-PadP$5)") (class "Default")
      (node (ref "LTC1") (pin "P$5") (pinfunction "S11_P$5") (pintype "bidirectional"))
    )
    (net (code "293") (name "unconnected-(LTC1-S12-PadP$3)") (class "Default")
      (node (ref "LTC1") (pin "P$3") (pinfunction "S12_P$3") (pintype "bidirectional"))
    )
    (net (code "294") (name "unconnected-(LTC2-S11-PadP$5)") (class "Default")
      (node (ref "LTC2") (pin "P$5") (pinfunction "S11_P$5") (pintype "bidirectional"))
    )
    (net (code "295") (name "unconnected-(LTC2-S12-PadP$3)") (class "Default")
      (node (ref "LTC2") (pin "P$3") (pinfunction "S12_P$3") (pintype "bidirectional"))
    )
    (net (code "296") (name "unconnected-(LTC3-S11-PadP$5)") (class "Default")
      (node (ref "LTC3") (pin "P$5") (pinfunction "S11_P$5") (pintype "bidirectional"))
    )
    (net (code "297") (name "unconnected-(LTC3-S12-PadP$3)") (class "Default")
      (node (ref "LTC3") (pin "P$3") (pinfunction "S12_P$3") (pintype "bidirectional"))
    )
    (net (code "298") (name "unconnected-(U$1-IN6-Pad6)") (class "Default")
      (node (ref "U$1") (pin "6") (pinfunction "IN6_6") (pintype "bidirectional"))
    )
    (net (code "299") (name "unconnected-(U$1-IN7-Pad7)") (class "Default")
      (node (ref "U$1") (pin "7") (pinfunction "IN7_7") (pintype "bidirectional"))
    )
    (net (code "300") (name "unconnected-(U$1-IN9-Pad9)") (class "Default")
      (node (ref "U$1") (pin "9") (pinfunction "IN9_9") (pintype "bidirectional"))
    )
    (net (code "301") (name "unconnected-(U$1-IN10-Pad10)") (class "Default")
      (node (ref "U$1") (pin "10") (pinfunction "IN10_10") (pintype "bidirectional"))
    )
    (net (code "302") (name "unconnected-(U$1-IN11-Pad11)") (class "Default")
      (node (ref "U$1") (pin "11") (pinfunction "IN11_11") (pintype "bidirectional"))
    )
    (net (code "303") (name "unconnected-(U$1-IN12-Pad12)") (class "Default")
      (node (ref "U$1") (pin "12") (pinfunction "IN12_12") (pintype "bidirectional"))
    )
    (net (code "304") (name "unconnected-(U$1-IN13-Pad13)") (class "Default")
      (node (ref "U$1") (pin "13") (pinfunction "IN13_13") (pintype "bidirectional"))
    )
    (net (code "305") (name "unconnected-(U$1-IN14-Pad14)") (class "Default")
      (node (ref "U$1") (pin "14") (pinfunction "IN14_14") (pintype "bidirectional"))
    )
    (net (code "306") (name "unconnected-(U$1-IN15-Pad15)") (class "Default")
      (node (ref "U$1") (pin "15") (pinfunction "IN15_15") (pintype "bidirectional"))
    )
    (net (code "307") (name "unconnected-(U$6-CH5-Pad6)") (class "Default")
      (node (ref "U$6") (pin "6") (pinfunction "CH5_6") (pintype "bidirectional"))
    )
    (net (code "308") (name "unconnected-(U$6-CH6-Pad7)") (class "Default")
      (node (ref "U$6") (pin "7") (pinfunction "CH6_7") (pintype "bidirectional"))
    )
    (net (code "309") (name "unconnected-(U$6-CH7-Pad8)") (class "Default")
      (node (ref "U$6") (pin "8") (pinfunction "CH7_8") (pintype "bidirectional"))
    )
  )
)
